# VCFA_v2.net
KiCad netlist of a schematic drawn in EAGLE
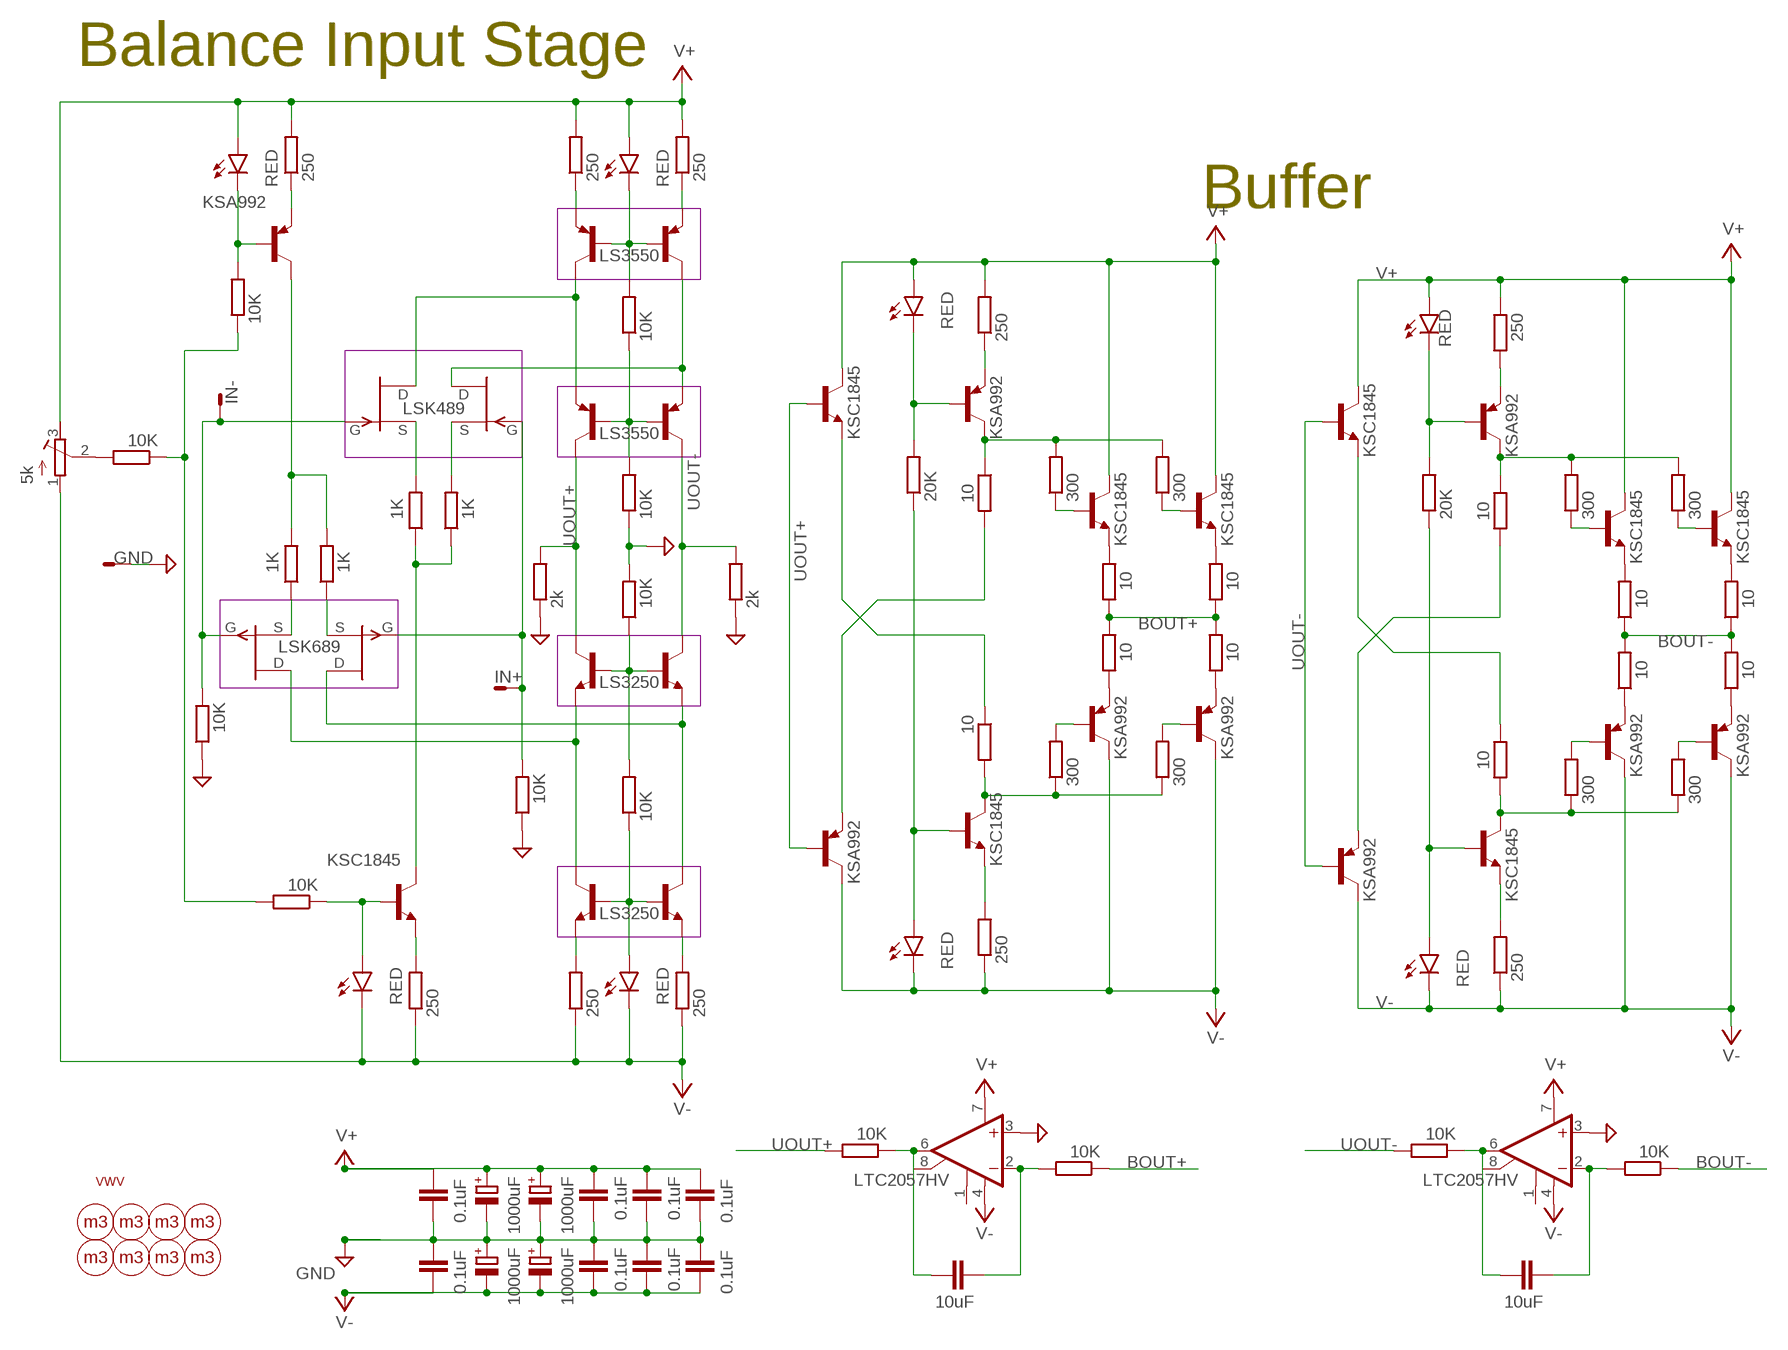
[diagram p0: schematic, sheet 1]
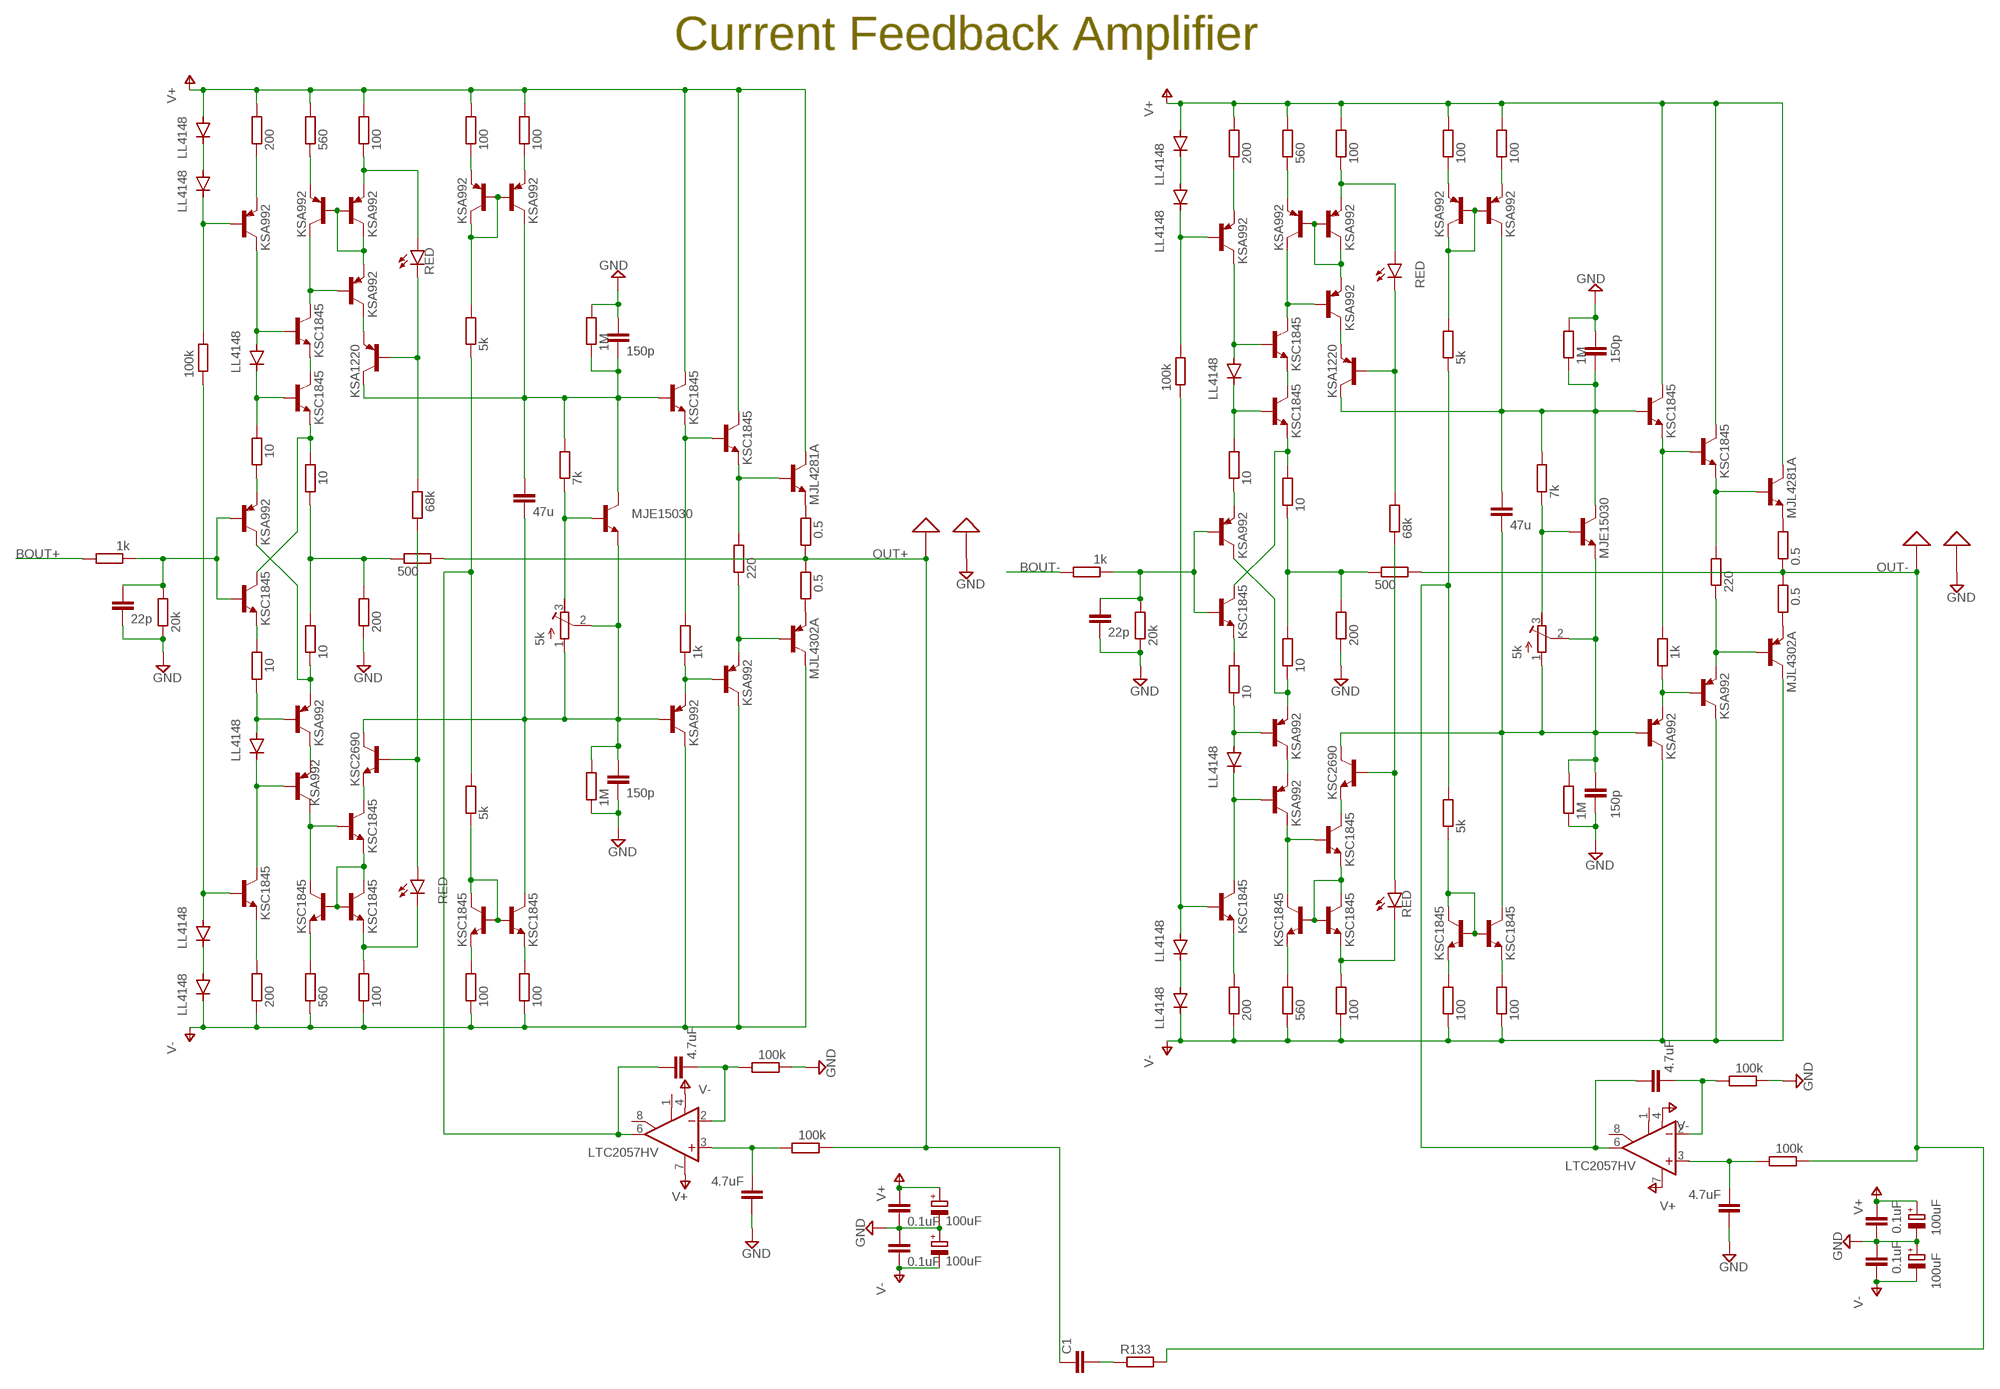
[diagram p1: schematic, sheet 2]
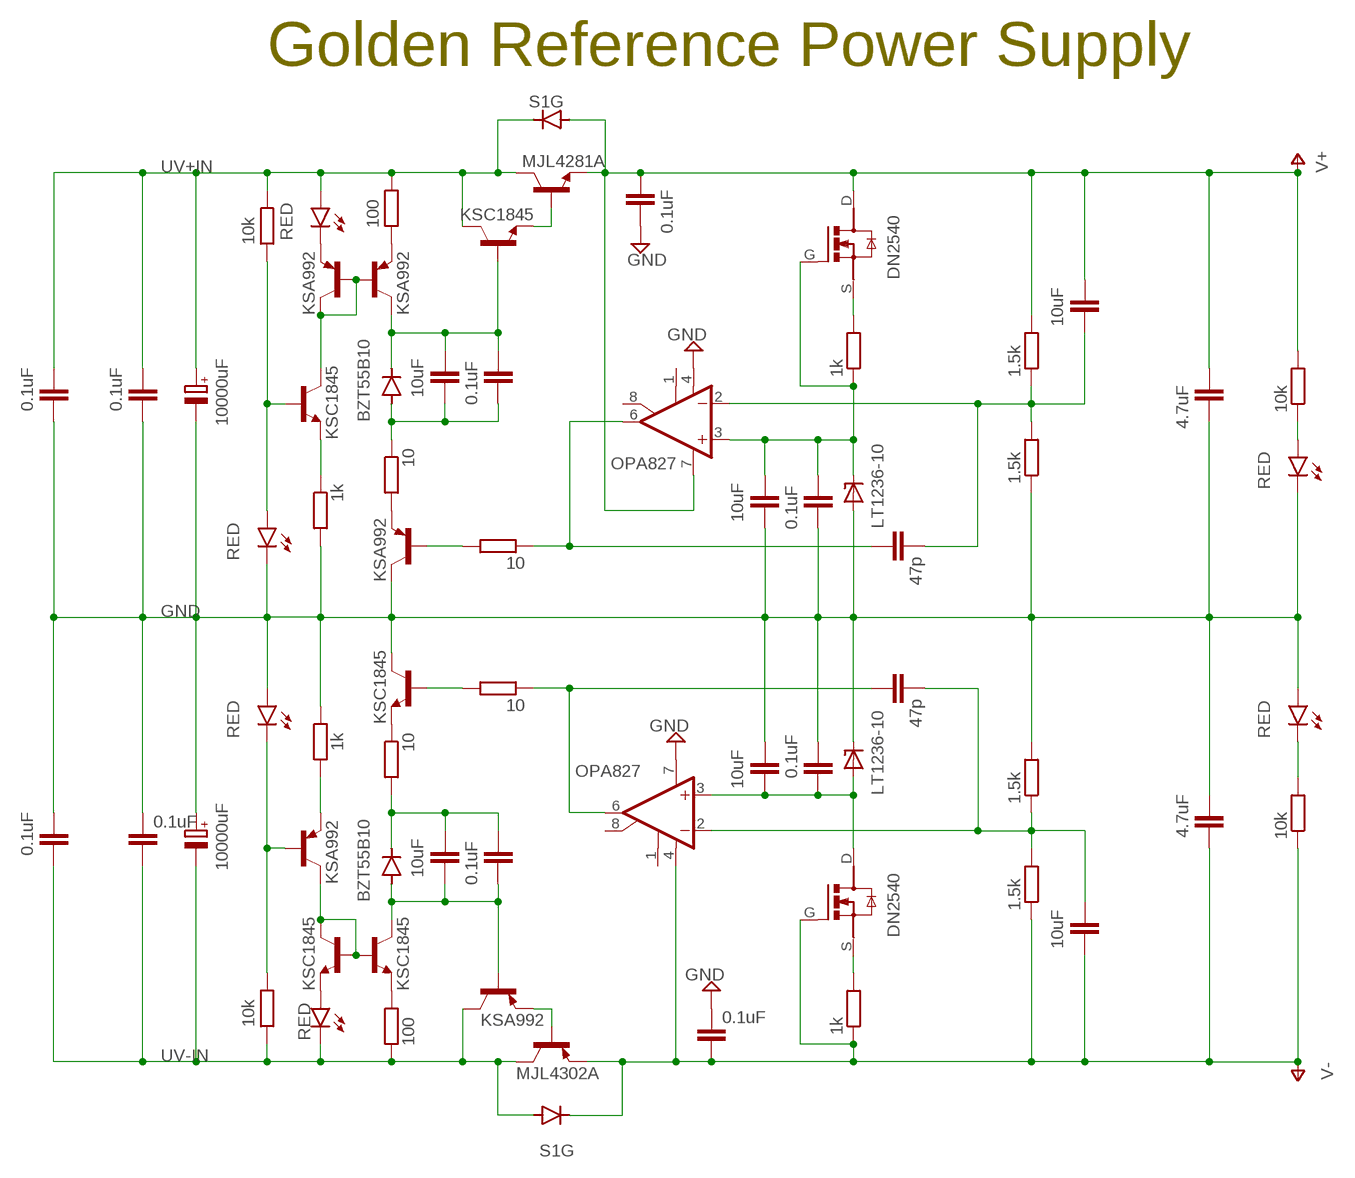
[diagram p2: schematic, sheet 3]
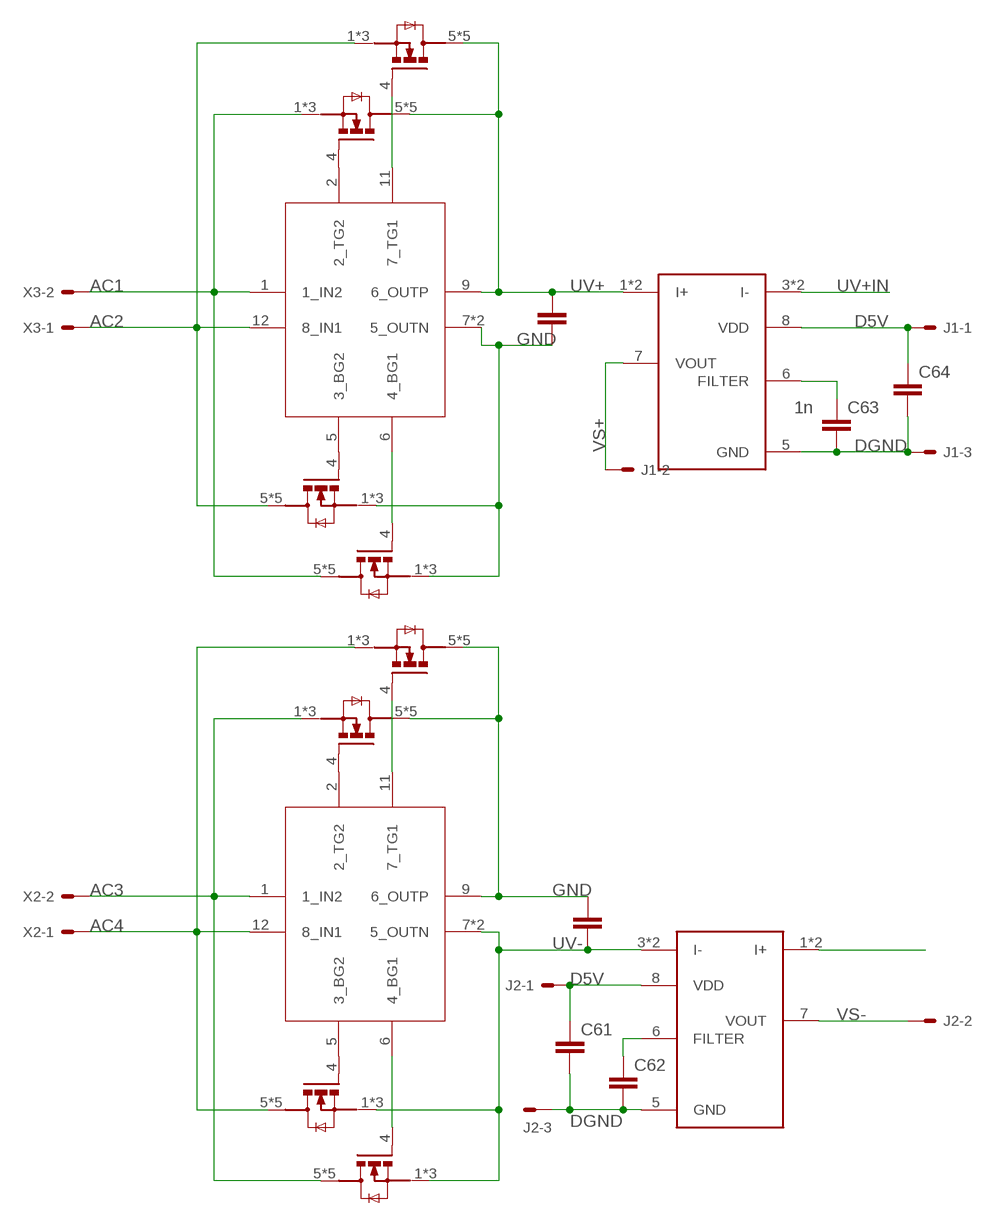
[diagram p3: schematic, sheet 4]

(export (version "E")
  (design (tool "Eeschema 10.0.6"))
  (components
    (comp (ref "C3")
      (value "0.1uF")
      (footprint "eagle-import:C0805")
      (libsource (lib "eagle-import") (part "C-EUC0805"))
    )
    (comp (ref "C4")
      (value "0.1uF")
      (footprint "eagle-import:C0805")
      (libsource (lib "eagle-import") (part "C-EUC0805"))
    )
    (comp (ref "C5")
      (value "1000uF")
      (footprint "eagle-import:E7,5-18")
      (libsource (lib "eagle-import") (part "CPOL-EUE7.5-18"))
    )
    (comp (ref "C6")
      (value "1000uF")
      (footprint "eagle-import:E7,5-18")
      (libsource (lib "eagle-import") (part "CPOL-EUE7.5-18"))
    )
    (comp (ref "C7")
      (value "1000uF")
      (footprint "eagle-import:E7,5-18")
      (libsource (lib "eagle-import") (part "CPOL-EUE7.5-18"))
    )
    (comp (ref "C8")
      (value "1000uF")
      (footprint "eagle-import:E7,5-18")
      (libsource (lib "eagle-import") (part "CPOL-EUE7.5-18"))
    )
    (comp (ref "C9")
      (value "0.1uF")
      (footprint "eagle-import:C050-045X075")
      (libsource (lib "eagle-import") (part "C-EU050-045X075"))
    )
    (comp (ref "C10")
      (value "0.1uF")
      (footprint "eagle-import:C050-045X075")
      (libsource (lib "eagle-import") (part "C-EU050-045X075"))
    )
    (comp (ref "C11")
      (value "0.1uF")
      (footprint "eagle-import:C050-045X075")
      (libsource (lib "eagle-import") (part "C-EU050-045X075"))
    )
    (comp (ref "C12")
      (value "0.1uF")
      (footprint "eagle-import:C050-045X075")
      (libsource (lib "eagle-import") (part "C-EU050-045X075"))
    )
    (comp (ref "C13")
      (value "10uF")
      (footprint "eagle-import:C1206")
      (libsource (lib "eagle-import") (part "C-EUC1206"))
    )
    (comp (ref "C14")
      (value "0.1uF")
      (footprint "eagle-import:C0805")
      (libsource (lib "eagle-import") (part "C-EUC0805"))
    )
    (comp (ref "C15")
      (value "0.1uF")
      (footprint "eagle-import:C0805")
      (libsource (lib "eagle-import") (part "C-EUC0805"))
    )
    (comp (ref "C16")
      (value "10uF")
      (footprint "eagle-import:C1206")
      (libsource (lib "eagle-import") (part "C-EUC1206"))
    )
    (comp (ref "H1")
      (value "HOLE")
      (footprint "eagle-import:M3_HOLE")
      (libsource (lib "eagle-import") (part "HOLE"))
    )
    (comp (ref "H2")
      (value "HOLE")
      (footprint "eagle-import:M3_HOLE")
      (libsource (lib "eagle-import") (part "HOLE"))
    )
    (comp (ref "H3")
      (value "HOLE")
      (footprint "eagle-import:M3_HOLE")
      (libsource (lib "eagle-import") (part "HOLE"))
    )
    (comp (ref "H4")
      (value "HOLE")
      (footprint "eagle-import:M3_HOLE")
      (libsource (lib "eagle-import") (part "HOLE"))
    )
    (comp (ref "H5")
      (value "HOLE")
      (footprint "eagle-import:M3_HOLE")
      (libsource (lib "eagle-import") (part "HOLE"))
    )
    (comp (ref "H6")
      (value "HOLE")
      (footprint "eagle-import:M3_HOLE")
      (libsource (lib "eagle-import") (part "HOLE"))
    )
    (comp (ref "H7")
      (value "HOLE")
      (footprint "eagle-import:M3_HOLE")
      (libsource (lib "eagle-import") (part "HOLE"))
    )
    (comp (ref "H8")
      (value "HOLE")
      (footprint "eagle-import:M3_HOLE")
      (libsource (lib "eagle-import") (part "HOLE"))
    )
    (comp (ref "IC1")
      (value "LTC2057HV")
      (footprint "eagle-import:SOIC8")
      (libsource (lib "eagle-import") (part "LT10S807C"))
    )
    (comp (ref "IC2")
      (value "LTC2057HV")
      (footprint "eagle-import:SOIC8")
      (libsource (lib "eagle-import") (part "LT10S807C"))
    )
    (comp (ref "LED1")
      (value "RED")
      (footprint "eagle-import:LED_SML1206")
      (libsource (lib "eagle-import") (part "LEDVWV1206"))
    )
    (comp (ref "LED2")
      (value "RED")
      (footprint "eagle-import:LED_SML1206")
      (fields (field (name "SPICEPREFIX") "D"))
      (libsource (lib "eagle-import") (part "LEDVWV1206"))
    )
    (comp (ref "LED3")
      (value "RED")
      (footprint "eagle-import:LED_SML1206")
      (libsource (lib "eagle-import") (part "LEDVWV1206"))
    )
    (comp (ref "LED4")
      (value "RED")
      (footprint "eagle-import:LED_SML1206")
      (libsource (lib "eagle-import") (part "LEDVWV1206"))
    )
    (comp (ref "LED5")
      (value "RED")
      (footprint "eagle-import:LED_SML1206")
      (libsource (lib "eagle-import") (part "LEDVWV1206"))
    )
    (comp (ref "LED6")
      (value "RED")
      (footprint "eagle-import:LED_SML1206")
      (libsource (lib "eagle-import") (part "LEDVWV1206"))
    )
    (comp (ref "LED7")
      (value "RED")
      (footprint "eagle-import:LED_SML1206")
      (libsource (lib "eagle-import") (part "LEDVWV1206"))
    )
    (comp (ref "LED8")
      (value "RED")
      (footprint "eagle-import:LED_SML1206")
      (libsource (lib "eagle-import") (part "LEDVWV1206"))
    )
    (comp (ref "Q1")
      (value "LSK689")
      (footprint "eagle-import:SOT-23-6")
      (libsource (lib "eagle-import") (part "LSK689"))
    )
    (comp (ref "Q2")
      (value "KSA992")
      (footprint "eagle-import:TRANSISTOR_TO92-ECB_P")
      (libsource (lib "eagle-import") (part "BJT_PNPKSA992"))
    )
    (comp (ref "Q3")
      (value "KSC1845")
      (footprint "eagle-import:TRANSISTOR_TO92-ECB_N")
      (libsource (lib "eagle-import") (part "BJT_NPNKSC1845"))
    )
    (comp (ref "Q4")
      (value "LSK489")
      (footprint "eagle-import:SOT-23-6")
      (libsource (lib "eagle-import") (part "LSK489SOP-6"))
    )
    (comp (ref "Q5")
      (value "LS3550")
      (footprint "eagle-import:SOT-23-6")
      (libsource (lib "eagle-import") (part "LS3550"))
    )
    (comp (ref "Q6")
      (value "LS3250")
      (footprint "eagle-import:SOT-23-6")
      (libsource (lib "eagle-import") (part "LS3250"))
    )
    (comp (ref "Q7")
      (value "LS3250")
      (footprint "eagle-import:SOT-23-6")
      (libsource (lib "eagle-import") (part "LS3250"))
    )
    (comp (ref "Q8")
      (value "LS3550")
      (footprint "eagle-import:SOT-23-6")
      (libsource (lib "eagle-import") (part "LS3550"))
    )
    (comp (ref "Q9")
      (value "KSC1845")
      (footprint "eagle-import:TRANSISTOR_TO92-ECB_N")
      (libsource (lib "eagle-import") (part "BJT_NPNKSC1845"))
    )
    (comp (ref "Q10")
      (value "KSA992")
      (footprint "eagle-import:TRANSISTOR_TO92-ECB_P")
      (libsource (lib "eagle-import") (part "BJT_PNPKSA992"))
    )
    (comp (ref "Q11")
      (value "KSA992")
      (footprint "eagle-import:TRANSISTOR_TO92-ECB_P")
      (libsource (lib "eagle-import") (part "BJT_PNPKSA992"))
    )
    (comp (ref "Q12")
      (value "KSC1845")
      (footprint "eagle-import:TRANSISTOR_TO92-ECB_N")
      (libsource (lib "eagle-import") (part "BJT_NPNKSC1845"))
    )
    (comp (ref "Q13")
      (value "KSC1845")
      (footprint "eagle-import:TRANSISTOR_TO92-ECB_N")
      (libsource (lib "eagle-import") (part "BJT_NPNKSC1845"))
    )
    (comp (ref "Q14")
      (value "KSA992")
      (footprint "eagle-import:TRANSISTOR_TO92-ECB_P")
      (libsource (lib "eagle-import") (part "BJT_PNPKSA992"))
    )
    (comp (ref "Q15")
      (value "KSC1845")
      (footprint "eagle-import:TRANSISTOR_TO92-ECB_N")
      (libsource (lib "eagle-import") (part "BJT_NPNKSC1845"))
    )
    (comp (ref "Q16")
      (value "KSA992")
      (footprint "eagle-import:TRANSISTOR_TO92-ECB_P")
      (libsource (lib "eagle-import") (part "BJT_PNPKSA992"))
    )
    (comp (ref "Q17")
      (value "KSC1845")
      (footprint "eagle-import:TRANSISTOR_TO92-ECB_N")
      (libsource (lib "eagle-import") (part "BJT_NPNKSC1845"))
    )
    (comp (ref "Q18")
      (value "KSA992")
      (footprint "eagle-import:TRANSISTOR_TO92-ECB_P")
      (libsource (lib "eagle-import") (part "BJT_PNPKSA992"))
    )
    (comp (ref "Q19")
      (value "KSA992")
      (footprint "eagle-import:TRANSISTOR_TO92-ECB_P")
      (libsource (lib "eagle-import") (part "BJT_PNPKSA992"))
    )
    (comp (ref "Q20")
      (value "KSC1845")
      (footprint "eagle-import:TRANSISTOR_TO92-ECB_N")
      (libsource (lib "eagle-import") (part "BJT_NPNKSC1845"))
    )
    (comp (ref "Q21")
      (value "KSC1845")
      (footprint "eagle-import:TRANSISTOR_TO92-ECB_N")
      (libsource (lib "eagle-import") (part "BJT_NPNKSC1845"))
    )
    (comp (ref "Q22")
      (value "KSA992")
      (footprint "eagle-import:TRANSISTOR_TO92-ECB_P")
      (libsource (lib "eagle-import") (part "BJT_PNPKSA992"))
    )
    (comp (ref "Q23")
      (value "KSC1845")
      (footprint "eagle-import:TRANSISTOR_TO92-ECB_N")
      (libsource (lib "eagle-import") (part "BJT_NPNKSC1845"))
    )
    (comp (ref "Q24")
      (value "KSA992")
      (footprint "eagle-import:TRANSISTOR_TO92-ECB_P")
      (libsource (lib "eagle-import") (part "BJT_PNPKSA992"))
    )
    (comp (ref "R1")
      (value "5k")
      (footprint "eagle-import:RTRIM3296W")
      (fields (field (name "SPICEPREFIX") "Z"))
      (libsource (lib "eagle-import") (part "R-TRIMM3296W"))
    )
    (comp (ref "R2")
      (value "10K")
      (footprint "eagle-import:MINI_MELF-0204W")
      (libsource (lib "eagle-import") (part "R-EU_MELF0204W"))
    )
    (comp (ref "R3")
      (value "10K")
      (footprint "eagle-import:MINI_MELF-0204W")
      (libsource (lib "eagle-import") (part "R-EU_MELF0204W"))
    )
    (comp (ref "R4")
      (value "10K")
      (footprint "eagle-import:MINI_MELF-0204W")
      (libsource (lib "eagle-import") (part "R-EU_MELF0204W"))
    )
    (comp (ref "R5")
      (value "250")
      (footprint "eagle-import:MINI_MELF-0204W")
      (libsource (lib "eagle-import") (part "R-EU_MELF0204W"))
    )
    (comp (ref "R6")
      (value "1K")
      (footprint "eagle-import:MINI_MELF-0204W")
      (libsource (lib "eagle-import") (part "R-EU_MELF0204W"))
    )
    (comp (ref "R7")
      (value "250")
      (footprint "eagle-import:MINI_MELF-0204W")
      (fields (field (name "SPICEPREFIX") "R"))
      (libsource (lib "eagle-import") (part "R-EU_MELF0204W"))
    )
    (comp (ref "R8")
      (value "1K")
      (footprint "eagle-import:MINI_MELF-0204W")
      (libsource (lib "eagle-import") (part "R-EU_MELF0204W"))
    )
    (comp (ref "R9")
      (value "1K")
      (footprint "eagle-import:MINI_MELF-0204W")
      (libsource (lib "eagle-import") (part "R-EU_MELF0204W"))
    )
    (comp (ref "R10")
      (value "1K")
      (footprint "eagle-import:MINI_MELF-0204W")
      (libsource (lib "eagle-import") (part "R-EU_MELF0204W"))
    )
    (comp (ref "R11")
      (value "2k")
      (footprint "eagle-import:MINI_MELF-0204W")
      (libsource (lib "eagle-import") (part "R-EU_MELF0204W"))
    )
    (comp (ref "R12")
      (value "250")
      (footprint "eagle-import:MINI_MELF-0204W")
      (libsource (lib "eagle-import") (part "R-EU_MELF0204W"))
    )
    (comp (ref "R13")
      (value "250")
      (footprint "eagle-import:MINI_MELF-0204W")
      (libsource (lib "eagle-import") (part "R-EU_MELF0204W"))
    )
    (comp (ref "R14")
      (value "10K")
      (footprint "eagle-import:MINI_MELF-0204W")
      (libsource (lib "eagle-import") (part "R-EU_MELF0204W"))
    )
    (comp (ref "R15")
      (value "10K")
      (footprint "eagle-import:MINI_MELF-0204W")
      (libsource (lib "eagle-import") (part "R-EU_MELF0204W"))
    )
    (comp (ref "R16")
      (value "10K")
      (footprint "eagle-import:MINI_MELF-0204W")
      (libsource (lib "eagle-import") (part "R-EU_MELF0204W"))
    )
    (comp (ref "R17")
      (value "10K")
      (footprint "eagle-import:MINI_MELF-0204W")
      (libsource (lib "eagle-import") (part "R-EU_MELF0204W"))
    )
    (comp (ref "R18")
      (value "250")
      (footprint "eagle-import:MINI_MELF-0204W")
      (libsource (lib "eagle-import") (part "R-EU_MELF0204W"))
    )
    (comp (ref "R19")
      (value "250")
      (footprint "eagle-import:MINI_MELF-0204W")
      (libsource (lib "eagle-import") (part "R-EU_MELF0204W"))
    )
    (comp (ref "R20")
      (value "2k")
      (footprint "eagle-import:MINI_MELF-0204W")
      (libsource (lib "eagle-import") (part "R-EU_MELF0204W"))
    )
    (comp (ref "R21")
      (value "10K")
      (footprint "eagle-import:MINI_MELF-0204W")
      (libsource (lib "eagle-import") (part "R-EU_MELF0204W"))
    )
    (comp (ref "R22")
      (value "20K")
      (footprint "eagle-import:MINI_MELF-0204W")
      (libsource (lib "eagle-import") (part "R-EU_MELF0204W"))
    )
    (comp (ref "R23")
      (value "250")
      (footprint "eagle-import:MINI_MELF-0204W")
      (libsource (lib "eagle-import") (part "R-EU_MELF0204W"))
    )
    (comp (ref "R24")
      (value "10")
      (footprint "eagle-import:MINI_MELF-0204W")
      (libsource (lib "eagle-import") (part "R-EU_MELF0204W"))
    )
    (comp (ref "R25")
      (value "10")
      (footprint "eagle-import:MINI_MELF-0204W")
      (libsource (lib "eagle-import") (part "R-EU_MELF0204W"))
    )
    (comp (ref "R26")
      (value "250")
      (footprint "eagle-import:MINI_MELF-0204W")
      (libsource (lib "eagle-import") (part "R-EU_MELF0204W"))
    )
    (comp (ref "R27")
      (value "300")
      (footprint "eagle-import:MINI_MELF-0204W")
      (libsource (lib "eagle-import") (part "R-EU_MELF0204W"))
    )
    (comp (ref "R28")
      (value "300")
      (footprint "eagle-import:MINI_MELF-0204W")
      (libsource (lib "eagle-import") (part "R-EU_MELF0204W"))
    )
    (comp (ref "R29")
      (value "10K")
      (footprint "eagle-import:MINI_MELF-0204W")
      (libsource (lib "eagle-import") (part "R-EU_MELF0204W"))
    )
    (comp (ref "R30")
      (value "10")
      (footprint "eagle-import:MINI_MELF-0204W")
      (libsource (lib "eagle-import") (part "R-EU_MELF0204W"))
    )
    (comp (ref "R31")
      (value "10")
      (footprint "eagle-import:MINI_MELF-0204W")
      (libsource (lib "eagle-import") (part "R-EU_MELF0204W"))
    )
    (comp (ref "R32")
      (value "300")
      (footprint "eagle-import:MINI_MELF-0204W")
      (libsource (lib "eagle-import") (part "R-EU_MELF0204W"))
    )
    (comp (ref "R33")
      (value "300")
      (footprint "eagle-import:MINI_MELF-0204W")
      (libsource (lib "eagle-import") (part "R-EU_MELF0204W"))
    )
    (comp (ref "R34")
      (value "10")
      (footprint "eagle-import:MINI_MELF-0204W")
      (libsource (lib "eagle-import") (part "R-EU_MELF0204W"))
    )
    (comp (ref "R35")
      (value "10")
      (footprint "eagle-import:MINI_MELF-0204W")
      (libsource (lib "eagle-import") (part "R-EU_MELF0204W"))
    )
    (comp (ref "R36")
      (value "10K")
      (footprint "eagle-import:MINI_MELF-0204W")
      (libsource (lib "eagle-import") (part "R-EU_MELF0204W"))
    )
    (comp (ref "R37")
      (value "20K")
      (footprint "eagle-import:MINI_MELF-0204W")
      (libsource (lib "eagle-import") (part "R-EU_MELF0204W"))
    )
    (comp (ref "R38")
      (value "250")
      (footprint "eagle-import:MINI_MELF-0204W")
      (libsource (lib "eagle-import") (part "R-EU_MELF0204W"))
    )
    (comp (ref "R39")
      (value "10")
      (footprint "eagle-import:MINI_MELF-0204W")
      (libsource (lib "eagle-import") (part "R-EU_MELF0204W"))
    )
    (comp (ref "R40")
      (value "10")
      (footprint "eagle-import:MINI_MELF-0204W")
      (libsource (lib "eagle-import") (part "R-EU_MELF0204W"))
    )
    (comp (ref "R41")
      (value "250")
      (footprint "eagle-import:MINI_MELF-0204W")
      (libsource (lib "eagle-import") (part "R-EU_MELF0204W"))
    )
    (comp (ref "R42")
      (value "300")
      (footprint "eagle-import:MINI_MELF-0204W")
      (libsource (lib "eagle-import") (part "R-EU_MELF0204W"))
    )
    (comp (ref "R43")
      (value "300")
      (footprint "eagle-import:MINI_MELF-0204W")
      (libsource (lib "eagle-import") (part "R-EU_MELF0204W"))
    )
    (comp (ref "R44")
      (value "10K")
      (footprint "eagle-import:MINI_MELF-0204W")
      (libsource (lib "eagle-import") (part "R-EU_MELF0204W"))
    )
    (comp (ref "R45")
      (value "10")
      (footprint "eagle-import:MINI_MELF-0204W")
      (libsource (lib "eagle-import") (part "R-EU_MELF0204W"))
    )
    (comp (ref "R46")
      (value "10")
      (footprint "eagle-import:MINI_MELF-0204W")
      (libsource (lib "eagle-import") (part "R-EU_MELF0204W"))
    )
    (comp (ref "R47")
      (value "300")
      (footprint "eagle-import:MINI_MELF-0204W")
      (libsource (lib "eagle-import") (part "R-EU_MELF0204W"))
    )
    (comp (ref "R48")
      (value "300")
      (footprint "eagle-import:MINI_MELF-0204W")
      (libsource (lib "eagle-import") (part "R-EU_MELF0204W"))
    )
    (comp (ref "R49")
      (value "10")
      (footprint "eagle-import:MINI_MELF-0204W")
      (libsource (lib "eagle-import") (part "R-EU_MELF0204W"))
    )
    (comp (ref "R50")
      (value "10")
      (footprint "eagle-import:MINI_MELF-0204W")
      (libsource (lib "eagle-import") (part "R-EU_MELF0204W"))
    )
    (comp (ref "R134")
      (value "10K")
      (footprint "eagle-import:MINI_MELF-0204W")
      (libsource (lib "eagle-import") (part "R-EU_MELF0204W"))
    )
    (comp (ref "R135")
      (value "10K")
      (footprint "eagle-import:MINI_MELF-0204W")
      (libsource (lib "eagle-import") (part "R-EU_MELF0204W"))
    )
    (comp (ref "S1")
      (value "VWV")
      (footprint "eagle-import:VWV")
      (libsource (lib "eagle-import") (part "VWV"))
    )
    (comp (ref "X1")
      (value "KK-156-3")
      (footprint "eagle-import:KK-156-3")
      (fields (field (name "MF") "MOLEX"))
      (libsource (lib "eagle-import") (part "KK-156-3"))
    )
    (comp (ref "C57")
      (value "47uF")
      (footprint "eagle-import:C1206")
      (libsource (lib "eagle-import") (part "C-EUC1206"))
    )
    (comp (ref "C59")
      (value "47uF")
      (footprint "eagle-import:C1206")
      (libsource (lib "eagle-import") (part "C-EUC1206"))
    )
    (comp (ref "C61")
      (value "C-EUC0805")
      (footprint "eagle-import:C0805")
      (libsource (lib "eagle-import") (part "C-EUC0805"))
    )
    (comp (ref "C62")
      (value "C-EUC0805")
      (footprint "eagle-import:C0805")
      (libsource (lib "eagle-import") (part "C-EUC0805"))
    )
    (comp (ref "C63")
      (value "1n")
      (footprint "eagle-import:C0805")
      (libsource (lib "eagle-import") (part "C-EUC0805"))
    )
    (comp (ref "C64")
      (value "C-EUC0805")
      (footprint "eagle-import:C0805")
      (libsource (lib "eagle-import") (part "C-EUC0805"))
    )
    (comp (ref "J1")
      (value "22-27-2031-03")
      (footprint "eagle-import:6410-03")
      (fields (field (name "MF") "MOLEX"))
      (libsource (lib "eagle-import") (part "22-?-0327-2031"))
    )
    (comp (ref "J2")
      (value "22-27-2031-03")
      (footprint "eagle-import:6410-03")
      (fields (field (name "MF") "MOLEX"))
      (libsource (lib "eagle-import") (part "22-?-0327-2031"))
    )
    (comp (ref "Q97")
      (value "MOS_SMDTDSON-8")
      (footprint "eagle-import:PG-TDSON-8")
      (libsource (lib "eagle-import") (part "MOS_SMDTDSON-8"))
    )
    (comp (ref "Q98")
      (value "MOS_SMDTDSON-8")
      (footprint "eagle-import:PG-TDSON-8")
      (libsource (lib "eagle-import") (part "MOS_SMDTDSON-8"))
    )
    (comp (ref "Q99")
      (value "MOS_SMDTDSON-8")
      (footprint "eagle-import:PG-TDSON-8")
      (libsource (lib "eagle-import") (part "MOS_SMDTDSON-8"))
    )
    (comp (ref "Q100")
      (value "MOS_SMDTDSON-8")
      (footprint "eagle-import:PG-TDSON-8")
      (libsource (lib "eagle-import") (part "MOS_SMDTDSON-8"))
    )
    (comp (ref "Q105")
      (value "MOS_SMDTDSON-8")
      (footprint "eagle-import:PG-TDSON-8")
      (libsource (lib "eagle-import") (part "MOS_SMDTDSON-8"))
    )
    (comp (ref "Q106")
      (value "MOS_SMDTDSON-8")
      (footprint "eagle-import:PG-TDSON-8")
      (libsource (lib "eagle-import") (part "MOS_SMDTDSON-8"))
    )
    (comp (ref "Q107")
      (value "MOS_SMDTDSON-8")
      (footprint "eagle-import:PG-TDSON-8")
      (libsource (lib "eagle-import") (part "MOS_SMDTDSON-8"))
    )
    (comp (ref "Q108")
      (value "MOS_SMDTDSON-8")
      (footprint "eagle-import:PG-TDSON-8")
      (libsource (lib "eagle-import") (part "MOS_SMDTDSON-8"))
    )
    (comp (ref "U$1")
      (value "ACHS-712X")
      (footprint "eagle-import:SO8")
      (libsource (lib "eagle-import") (part "ACHS-712X"))
    )
    (comp (ref "U$2")
      (value "LT4320MSOP")
      (footprint "eagle-import:LT4320_MSOP")
      (libsource (lib "eagle-import") (part "LT4320MSOP"))
    )
    (comp (ref "U$3")
      (value "ACHS-712X")
      (footprint "eagle-import:SO8")
      (libsource (lib "eagle-import") (part "ACHS-712X"))
    )
    (comp (ref "U$4")
      (value "LT4320MSOP")
      (footprint "eagle-import:LT4320_MSOP")
      (libsource (lib "eagle-import") (part "LT4320MSOP"))
    )
    (comp (ref "X2")
      (value "KK-156-2")
      (footprint "eagle-import:KK-156-2")
      (fields (field (name "MF") "MOLEX"))
      (libsource (lib "eagle-import") (part "KK-156-2"))
    )
    (comp (ref "X3")
      (value "KK-156-2")
      (footprint "eagle-import:KK-156-2")
      (fields (field (name "MF") "MOLEX"))
      (libsource (lib "eagle-import") (part "KK-156-2"))
    )
    (comp (ref "C1")
      (value "C-EUECWU-V")
      (footprint "eagle-import:ECHU-Y")
      (libsource (lib "eagle-import") (part "C-EUECWU-V"))
    )
    (comp (ref "C17")
      (value "22p")
      (footprint "eagle-import:C0805")
      (fields (field (name "SPICEPREFIX") "C"))
      (libsource (lib "eagle-import") (part "C-EUC0805"))
    )
    (comp (ref "C18")
      (value "47u")
      (footprint "eagle-import:C1210")
      (fields (field (name "SPICEPREFIX") "C"))
      (libsource (lib "eagle-import") (part "C-EUC1210"))
    )
    (comp (ref "C19")
      (value "150p")
      (footprint "eagle-import:C0805")
      (fields (field (name "SPICEPREFIX") "C"))
      (libsource (lib "eagle-import") (part "C-EUC0805"))
    )
    (comp (ref "C20")
      (value "150p")
      (footprint "eagle-import:C0805")
      (fields (field (name "SPICEPREFIX") "C"))
      (libsource (lib "eagle-import") (part "C-EUC0805"))
    )
    (comp (ref "C21")
      (value "4.7uF")
      (footprint "eagle-import:C1210")
      (fields (field (name "SPICEPREFIX") "C"))
      (libsource (lib "eagle-import") (part "C-EUC1210"))
    )
    (comp (ref "C22")
      (value "4.7uF")
      (footprint "eagle-import:C1210")
      (fields (field (name "SPICEPREFIX") "C"))
      (libsource (lib "eagle-import") (part "C-EUC1210"))
    )
    (comp (ref "C23")
      (value "0.1uF")
      (footprint "eagle-import:C0603K")
      (libsource (lib "eagle-import") (part "C-EUC0603K"))
    )
    (comp (ref "C24")
      (value "0.1uF")
      (footprint "eagle-import:C0603K")
      (libsource (lib "eagle-import") (part "C-EUC0603K"))
    )
    (comp (ref "C25")
      (value "100uF")
      (footprint "eagle-import:E3,5-8")
      (libsource (lib "eagle-import") (part "CPOL-EUE3.5-8"))
    )
    (comp (ref "C26")
      (value "100uF")
      (footprint "eagle-import:E3,5-8")
      (libsource (lib "eagle-import") (part "CPOL-EUE3.5-8"))
    )
    (comp (ref "C27")
      (value "22p")
      (footprint "eagle-import:C0805")
      (fields (field (name "SPICEPREFIX") "C"))
      (libsource (lib "eagle-import") (part "C-EUC0805"))
    )
    (comp (ref "C28")
      (value "47u")
      (footprint "eagle-import:C1210")
      (fields (field (name "SPICEPREFIX") "C"))
      (libsource (lib "eagle-import") (part "C-EUC1210"))
    )
    (comp (ref "C29")
      (value "150p")
      (footprint "eagle-import:C0805")
      (fields (field (name "SPICEPREFIX") "C"))
      (libsource (lib "eagle-import") (part "C-EUC0805"))
    )
    (comp (ref "C30")
      (value "150p")
      (footprint "eagle-import:C0805")
      (fields (field (name "SPICEPREFIX") "C"))
      (libsource (lib "eagle-import") (part "C-EUC0805"))
    )
    (comp (ref "C31")
      (value "4.7uF")
      (footprint "eagle-import:C1210")
      (fields (field (name "SPICEPREFIX") "C"))
      (libsource (lib "eagle-import") (part "C-EUC1210"))
    )
    (comp (ref "C32")
      (value "4.7uF")
      (footprint "eagle-import:C1210")
      (fields (field (name "SPICEPREFIX") "C"))
      (libsource (lib "eagle-import") (part "C-EUC1210"))
    )
    (comp (ref "C33")
      (value "0.1uF")
      (footprint "eagle-import:C0603K")
      (libsource (lib "eagle-import") (part "C-EUC0603K"))
    )
    (comp (ref "C34")
      (value "0.1uF")
      (footprint "eagle-import:C0603K")
      (libsource (lib "eagle-import") (part "C-EUC0603K"))
    )
    (comp (ref "C35")
      (value "100uF")
      (footprint "eagle-import:E3,5-8")
      (libsource (lib "eagle-import") (part "CPOL-EUE3.5-8"))
    )
    (comp (ref "C36")
      (value "100uF")
      (footprint "eagle-import:E3,5-8")
      (libsource (lib "eagle-import") (part "CPOL-EUE3.5-8"))
    )
    (comp (ref "D1")
      (value "LL4148")
      (footprint "eagle-import:SOD80C")
      (fields (field (name "SPICEPREFIX") "D"))
      (libsource (lib "eagle-import") (part "DIODE-SOD80C"))
    )
    (comp (ref "D2")
      (value "LL4148")
      (footprint "eagle-import:SOD80C")
      (fields (field (name "SPICEPREFIX") "D"))
      (libsource (lib "eagle-import") (part "DIODE-SOD80C"))
    )
    (comp (ref "D3")
      (value "LL4148")
      (footprint "eagle-import:SOD80C")
      (fields (field (name "SPICEPREFIX") "D"))
      (libsource (lib "eagle-import") (part "DIODE-SOD80C"))
    )
    (comp (ref "D4")
      (value "LL4148")
      (footprint "eagle-import:SOD80C")
      (fields (field (name "SPICEPREFIX") "D"))
      (libsource (lib "eagle-import") (part "DIODE-SOD80C"))
    )
    (comp (ref "D5")
      (value "LL4148")
      (footprint "eagle-import:SOD80C")
      (fields (field (name "SPICEPREFIX") "D"))
      (libsource (lib "eagle-import") (part "DIODE-SOD80C"))
    )
    (comp (ref "D6")
      (value "LL4148")
      (footprint "eagle-import:SOD80C")
      (fields (field (name "SPICEPREFIX") "D"))
      (libsource (lib "eagle-import") (part "DIODE-SOD80C"))
    )
    (comp (ref "D7")
      (value "LL4148")
      (footprint "eagle-import:SOD80C")
      (fields (field (name "SPICEPREFIX") "D"))
      (libsource (lib "eagle-import") (part "DIODE-SOD80C"))
    )
    (comp (ref "D8")
      (value "LL4148")
      (footprint "eagle-import:SOD80C")
      (fields (field (name "SPICEPREFIX") "D"))
      (libsource (lib "eagle-import") (part "DIODE-SOD80C"))
    )
    (comp (ref "D9")
      (value "LL4148")
      (footprint "eagle-import:SOD80C")
      (fields (field (name "SPICEPREFIX") "D"))
      (libsource (lib "eagle-import") (part "DIODE-SOD80C"))
    )
    (comp (ref "D10")
      (value "LL4148")
      (footprint "eagle-import:SOD80C")
      (fields (field (name "SPICEPREFIX") "D"))
      (libsource (lib "eagle-import") (part "DIODE-SOD80C"))
    )
    (comp (ref "D11")
      (value "LL4148")
      (footprint "eagle-import:SOD80C")
      (fields (field (name "SPICEPREFIX") "D"))
      (libsource (lib "eagle-import") (part "DIODE-SOD80C"))
    )
    (comp (ref "D12")
      (value "LL4148")
      (footprint "eagle-import:SOD80C")
      (fields (field (name "SPICEPREFIX") "D"))
      (libsource (lib "eagle-import") (part "DIODE-SOD80C"))
    )
    (comp (ref "IC3")
      (value "LTC2057HV")
      (footprint "eagle-import:SOIC8")
      (libsource (lib "eagle-import") (part "LT10S837I"))
    )
    (comp (ref "IC4")
      (value "LTC2057HV")
      (footprint "eagle-import:SOIC8")
      (libsource (lib "eagle-import") (part "LT10S837I"))
    )
    (comp (ref "LED9")
      (value "RED")
      (footprint "eagle-import:LED_SML1206")
      (fields (field (name "SPICEPREFIX") "D"))
      (libsource (lib "eagle-import") (part "LEDVWV1206"))
    )
    (comp (ref "LED10")
      (value "RED")
      (footprint "eagle-import:LED_SML1206")
      (fields (field (name "SPICEPREFIX") "D"))
      (libsource (lib "eagle-import") (part "LEDVWV1206"))
    )
    (comp (ref "LED11")
      (value "RED")
      (footprint "eagle-import:LED_SML1206")
      (fields (field (name "SPICEPREFIX") "D"))
      (libsource (lib "eagle-import") (part "LEDVWV1206"))
    )
    (comp (ref "LED12")
      (value "RED")
      (footprint "eagle-import:LED_SML1206")
      (fields (field (name "SPICEPREFIX") "D"))
      (libsource (lib "eagle-import") (part "LEDVWV1206"))
    )
    (comp (ref "PAD1")
      (value "PAD")
      (footprint "eagle-import:PAD-16")
      (libsource (lib "eagle-import") (part "PAD"))
    )
    (comp (ref "PAD2")
      (value "PAD")
      (footprint "eagle-import:PAD-16")
      (libsource (lib "eagle-import") (part "PAD"))
    )
    (comp (ref "PAD3")
      (value "PAD")
      (footprint "eagle-import:PAD-16")
      (libsource (lib "eagle-import") (part "PAD"))
    )
    (comp (ref "PAD4")
      (value "PAD")
      (footprint "eagle-import:PAD-16")
      (libsource (lib "eagle-import") (part "PAD"))
    )
    (comp (ref "Q25")
      (value "KSA992")
      (footprint "eagle-import:TRANSISTOR_TO92-ECB_P")
      (fields (field (name "SPICEPREFIX") "Q"))
      (libsource (lib "eagle-import") (part "BJT_PNPKSA992"))
    )
    (comp (ref "Q26")
      (value "KSA992")
      (footprint "eagle-import:TRANSISTOR_TO92-ECB_P")
      (fields (field (name "SPICEPREFIX") "Q"))
      (libsource (lib "eagle-import") (part "BJT_PNPKSA992"))
    )
    (comp (ref "Q27")
      (value "KSC1845")
      (footprint "eagle-import:TRANSISTOR_TO92-ECB_N")
      (fields (field (name "SPICEPREFIX") "Q"))
      (libsource (lib "eagle-import") (part "BJT_NPNKSC1845"))
    )
    (comp (ref "Q28")
      (value "KSC1845")
      (footprint "eagle-import:TRANSISTOR_TO92-ECB_N")
      (fields (field (name "SPICEPREFIX") "Q"))
      (libsource (lib "eagle-import") (part "BJT_NPNKSC1845"))
    )
    (comp (ref "Q29")
      (value "KSC1845")
      (footprint "eagle-import:TRANSISTOR_TO92-ECB_N")
      (fields (field (name "SPICEPREFIX") "Q"))
      (libsource (lib "eagle-import") (part "BJT_NPNKSC1845"))
    )
    (comp (ref "Q30")
      (value "KSC1845")
      (footprint "eagle-import:TRANSISTOR_TO92-ECB_N")
      (fields (field (name "SPICEPREFIX") "Q"))
      (libsource (lib "eagle-import") (part "BJT_NPNKSC1845"))
    )
    (comp (ref "Q31")
      (value "KSA992")
      (footprint "eagle-import:TRANSISTOR_TO92-ECB_P")
      (fields (field (name "SPICEPREFIX") "Q"))
      (libsource (lib "eagle-import") (part "BJT_PNPKSA992"))
    )
    (comp (ref "Q32")
      (value "KSA992")
      (footprint "eagle-import:TRANSISTOR_TO92-ECB_P")
      (fields (field (name "SPICEPREFIX") "Q"))
      (libsource (lib "eagle-import") (part "BJT_PNPKSA992"))
    )
    (comp (ref "Q33")
      (value "KSA992")
      (footprint "eagle-import:TRANSISTOR_TO92-ECB_P")
      (fields (field (name "SPICEPREFIX") "Q"))
      (libsource (lib "eagle-import") (part "BJT_PNPKSA992"))
    )
    (comp (ref "Q34")
      (value "KSC1845")
      (footprint "eagle-import:TRANSISTOR_TO92-ECB_N")
      (fields (field (name "SPICEPREFIX") "Q"))
      (libsource (lib "eagle-import") (part "BJT_NPNKSC1845"))
    )
    (comp (ref "Q35")
      (value "KSA992")
      (footprint "eagle-import:TRANSISTOR_TO92-ECB_P")
      (fields (field (name "SPICEPREFIX") "Q"))
      (libsource (lib "eagle-import") (part "BJT_PNPKSA992"))
    )
    (comp (ref "Q36")
      (value "KSA992")
      (footprint "eagle-import:TRANSISTOR_TO92-ECB_P")
      (fields (field (name "SPICEPREFIX") "Q"))
      (libsource (lib "eagle-import") (part "BJT_PNPKSA992"))
    )
    (comp (ref "Q37")
      (value "KSC1845")
      (footprint "eagle-import:TRANSISTOR_TO92-ECB_N")
      (fields (field (name "SPICEPREFIX") "Q"))
      (libsource (lib "eagle-import") (part "BJT_NPNKSC1845"))
    )
    (comp (ref "Q38")
      (value "KSC1845")
      (footprint "eagle-import:TRANSISTOR_TO92-ECB_N")
      (fields (field (name "SPICEPREFIX") "Q"))
      (libsource (lib "eagle-import") (part "BJT_NPNKSC1845"))
    )
    (comp (ref "Q39")
      (value "KSA1220")
      (footprint "eagle-import:TRANSISTOR_TO126_P")
      (fields (field (name "SPICEPREFIX") "Q"))
      (libsource (lib "eagle-import") (part "BJT_PNPKSA1220"))
    )
    (comp (ref "Q40")
      (value "KSC2690")
      (footprint "eagle-import:TRANSISTOR_TO126_N")
      (fields (field (name "SPICEPREFIX") "Q"))
      (libsource (lib "eagle-import") (part "BJT_NPNKSC2690"))
    )
    (comp (ref "Q41")
      (value "KSA992")
      (footprint "eagle-import:TRANSISTOR_TO92-ECB_P")
      (fields (field (name "SPICEPREFIX") "Q"))
      (libsource (lib "eagle-import") (part "BJT_PNPKSA992"))
    )
    (comp (ref "Q42")
      (value "KSC1845")
      (footprint "eagle-import:TRANSISTOR_TO92-ECB_N")
      (fields (field (name "SPICEPREFIX") "Q"))
      (libsource (lib "eagle-import") (part "BJT_NPNKSC1845"))
    )
    (comp (ref "Q43")
      (value "KSA992")
      (footprint "eagle-import:TRANSISTOR_TO92-ECB_P")
      (fields (field (name "SPICEPREFIX") "Q"))
      (libsource (lib "eagle-import") (part "BJT_PNPKSA992"))
    )
    (comp (ref "Q44")
      (value "KSC1845")
      (footprint "eagle-import:TRANSISTOR_TO92-ECB_N")
      (fields (field (name "SPICEPREFIX") "Q"))
      (libsource (lib "eagle-import") (part "BJT_NPNKSC1845"))
    )
    (comp (ref "Q45")
      (value "MJE15030")
      (footprint "eagle-import:TRANSISTOR_TO220_BCE_N")
      (fields (field (name "SPICEPREFIX") "Q"))
      (libsource (lib "eagle-import") (part "BJT_NPNMJE15030"))
    )
    (comp (ref "Q46")
      (value "KSC1845")
      (footprint "eagle-import:TRANSISTOR_TO92-ECB_N")
      (fields (field (name "SPICEPREFIX") "Q"))
      (libsource (lib "eagle-import") (part "BJT_NPNKSC1845"))
    )
    (comp (ref "Q47")
      (value "KSA992")
      (footprint "eagle-import:TRANSISTOR_TO92-ECB_P")
      (fields (field (name "SPICEPREFIX") "Q"))
      (libsource (lib "eagle-import") (part "BJT_PNPKSA992"))
    )
    (comp (ref "Q48")
      (value "KSC1845")
      (footprint "eagle-import:TRANSISTOR_TO92-ECB_N")
      (fields (field (name "SPICEPREFIX") "Q"))
      (libsource (lib "eagle-import") (part "BJT_NPNKSC1845"))
    )
    (comp (ref "Q49")
      (value "KSA992")
      (footprint "eagle-import:TRANSISTOR_TO92-ECB_P")
      (fields (field (name "SPICEPREFIX") "Q"))
      (libsource (lib "eagle-import") (part "BJT_PNPKSA992"))
    )
    (comp (ref "Q50")
      (value "MJL4281A")
      (footprint "eagle-import:TRANSISTOR_TO247_BCE_N")
      (fields (field (name "SPICEPREFIX") "Q"))
      (libsource (lib "eagle-import") (part "BJT_NPNMJL4281"))
    )
    (comp (ref "Q51")
      (value "MJL4302A")
      (footprint "eagle-import:TRANSISTOR_TO247_BCE_P")
      (fields (field (name "SPICEPREFIX") "Q"))
      (libsource (lib "eagle-import") (part "BJT_PNPMJL4302"))
    )
    (comp (ref "Q52")
      (value "KSA992")
      (footprint "eagle-import:TRANSISTOR_TO92-ECB_P")
      (fields (field (name "SPICEPREFIX") "Q"))
      (libsource (lib "eagle-import") (part "BJT_PNPKSA992"))
    )
    (comp (ref "Q53")
      (value "KSA992")
      (footprint "eagle-import:TRANSISTOR_TO92-ECB_P")
      (fields (field (name "SPICEPREFIX") "Q"))
      (libsource (lib "eagle-import") (part "BJT_PNPKSA992"))
    )
    (comp (ref "Q54")
      (value "KSC1845")
      (footprint "eagle-import:TRANSISTOR_TO92-ECB_N")
      (fields (field (name "SPICEPREFIX") "Q"))
      (libsource (lib "eagle-import") (part "BJT_NPNKSC1845"))
    )
    (comp (ref "Q55")
      (value "KSC1845")
      (footprint "eagle-import:TRANSISTOR_TO92-ECB_N")
      (fields (field (name "SPICEPREFIX") "Q"))
      (libsource (lib "eagle-import") (part "BJT_NPNKSC1845"))
    )
    (comp (ref "Q56")
      (value "KSC1845")
      (footprint "eagle-import:TRANSISTOR_TO92-ECB_N")
      (fields (field (name "SPICEPREFIX") "Q"))
      (libsource (lib "eagle-import") (part "BJT_NPNKSC1845"))
    )
    (comp (ref "Q57")
      (value "KSC1845")
      (footprint "eagle-import:TRANSISTOR_TO92-ECB_N")
      (fields (field (name "SPICEPREFIX") "Q"))
      (libsource (lib "eagle-import") (part "BJT_NPNKSC1845"))
    )
    (comp (ref "Q58")
      (value "KSA992")
      (footprint "eagle-import:TRANSISTOR_TO92-ECB_P")
      (fields (field (name "SPICEPREFIX") "Q"))
      (libsource (lib "eagle-import") (part "BJT_PNPKSA992"))
    )
    (comp (ref "Q59")
      (value "KSA992")
      (footprint "eagle-import:TRANSISTOR_TO92-ECB_P")
      (fields (field (name "SPICEPREFIX") "Q"))
      (libsource (lib "eagle-import") (part "BJT_PNPKSA992"))
    )
    (comp (ref "Q60")
      (value "KSA992")
      (footprint "eagle-import:TRANSISTOR_TO92-ECB_P")
      (fields (field (name "SPICEPREFIX") "Q"))
      (libsource (lib "eagle-import") (part "BJT_PNPKSA992"))
    )
    (comp (ref "Q61")
      (value "KSC1845")
      (footprint "eagle-import:TRANSISTOR_TO92-ECB_N")
      (fields (field (name "SPICEPREFIX") "Q"))
      (libsource (lib "eagle-import") (part "BJT_NPNKSC1845"))
    )
    (comp (ref "Q62")
      (value "KSA992")
      (footprint "eagle-import:TRANSISTOR_TO92-ECB_P")
      (fields (field (name "SPICEPREFIX") "Q"))
      (libsource (lib "eagle-import") (part "BJT_PNPKSA992"))
    )
    (comp (ref "Q63")
      (value "KSA992")
      (footprint "eagle-import:TRANSISTOR_TO92-ECB_P")
      (fields (field (name "SPICEPREFIX") "Q"))
      (libsource (lib "eagle-import") (part "BJT_PNPKSA992"))
    )
    (comp (ref "Q64")
      (value "KSC1845")
      (footprint "eagle-import:TRANSISTOR_TO92-ECB_N")
      (fields (field (name "SPICEPREFIX") "Q"))
      (libsource (lib "eagle-import") (part "BJT_NPNKSC1845"))
    )
    (comp (ref "Q65")
      (value "KSC1845")
      (footprint "eagle-import:TRANSISTOR_TO92-ECB_N")
      (fields (field (name "SPICEPREFIX") "Q"))
      (libsource (lib "eagle-import") (part "BJT_NPNKSC1845"))
    )
    (comp (ref "Q66")
      (value "KSA1220")
      (footprint "eagle-import:TRANSISTOR_TO126_P")
      (fields (field (name "SPICEPREFIX") "Q"))
      (libsource (lib "eagle-import") (part "BJT_PNPKSA1220"))
    )
    (comp (ref "Q67")
      (value "KSC2690")
      (footprint "eagle-import:TRANSISTOR_TO126_N")
      (fields (field (name "SPICEPREFIX") "Q"))
      (libsource (lib "eagle-import") (part "BJT_NPNKSC2690"))
    )
    (comp (ref "Q68")
      (value "KSA992")
      (footprint "eagle-import:TRANSISTOR_TO92-ECB_P")
      (fields (field (name "SPICEPREFIX") "Q"))
      (libsource (lib "eagle-import") (part "BJT_PNPKSA992"))
    )
    (comp (ref "Q69")
      (value "KSC1845")
      (footprint "eagle-import:TRANSISTOR_TO92-ECB_N")
      (fields (field (name "SPICEPREFIX") "Q"))
      (libsource (lib "eagle-import") (part "BJT_NPNKSC1845"))
    )
    (comp (ref "Q70")
      (value "KSA992")
      (footprint "eagle-import:TRANSISTOR_TO92-ECB_P")
      (fields (field (name "SPICEPREFIX") "Q"))
      (libsource (lib "eagle-import") (part "BJT_PNPKSA992"))
    )
    (comp (ref "Q71")
      (value "KSC1845")
      (footprint "eagle-import:TRANSISTOR_TO92-ECB_N")
      (fields (field (name "SPICEPREFIX") "Q"))
      (libsource (lib "eagle-import") (part "BJT_NPNKSC1845"))
    )
    (comp (ref "Q72")
      (value "MJE15030")
      (footprint "eagle-import:TRANSISTOR_TO220_BCE_N")
      (fields (field (name "SPICEPREFIX") "Q"))
      (libsource (lib "eagle-import") (part "BJT_NPNMJE15030"))
    )
    (comp (ref "Q73")
      (value "KSC1845")
      (footprint "eagle-import:TRANSISTOR_TO92-ECB_N")
      (fields (field (name "SPICEPREFIX") "Q"))
      (libsource (lib "eagle-import") (part "BJT_NPNKSC1845"))
    )
    (comp (ref "Q74")
      (value "KSA992")
      (footprint "eagle-import:TRANSISTOR_TO92-ECB_P")
      (fields (field (name "SPICEPREFIX") "Q"))
      (libsource (lib "eagle-import") (part "BJT_PNPKSA992"))
    )
    (comp (ref "Q75")
      (value "KSC1845")
      (footprint "eagle-import:TRANSISTOR_TO92-ECB_N")
      (fields (field (name "SPICEPREFIX") "Q"))
      (libsource (lib "eagle-import") (part "BJT_NPNKSC1845"))
    )
    (comp (ref "Q76")
      (value "KSA992")
      (footprint "eagle-import:TRANSISTOR_TO92-ECB_P")
      (fields (field (name "SPICEPREFIX") "Q"))
      (libsource (lib "eagle-import") (part "BJT_PNPKSA992"))
    )
    (comp (ref "Q77")
      (value "MJL4281A")
      (footprint "eagle-import:TRANSISTOR_TO247_BCE_N")
      (fields (field (name "SPICEPREFIX") "Q"))
      (libsource (lib "eagle-import") (part "BJT_NPNMJL4281"))
    )
    (comp (ref "Q78")
      (value "MJL4302A")
      (footprint "eagle-import:TRANSISTOR_TO247_BCE_P")
      (fields (field (name "SPICEPREFIX") "Q"))
      (libsource (lib "eagle-import") (part "BJT_PNPMJL4302"))
    )
    (comp (ref "R51")
      (value "1k")
      (footprint "eagle-import:MINI_MELF-0204W")
      (fields (field (name "SPICEPREFIX") "R"))
      (libsource (lib "eagle-import") (part "R-EU_MELF0204W"))
    )
    (comp (ref "R52")
      (value "20k")
      (footprint "eagle-import:MINI_MELF-0204W")
      (fields (field (name "SPICEPREFIX") "R"))
      (libsource (lib "eagle-import") (part "R-EU_MELF0204W"))
    )
    (comp (ref "R53")
      (value "100k")
      (footprint "eagle-import:MINI_MELF-0204W")
      (fields (field (name "SPICEPREFIX") "R"))
      (libsource (lib "eagle-import") (part "R-EU_MELF0204W"))
    )
    (comp (ref "R54")
      (value "200")
      (footprint "eagle-import:MINI_MELF-0204W")
      (fields (field (name "SPICEPREFIX") "R"))
      (libsource (lib "eagle-import") (part "R-EU_MELF0204W"))
    )
    (comp (ref "R55")
      (value "10")
      (footprint "eagle-import:MINI_MELF-0204W")
      (fields (field (name "SPICEPREFIX") "R"))
      (libsource (lib "eagle-import") (part "R-EU_MELF0204W"))
    )
    (comp (ref "R56")
      (value "10")
      (footprint "eagle-import:MINI_MELF-0204W")
      (fields (field (name "SPICEPREFIX") "R"))
      (libsource (lib "eagle-import") (part "R-EU_MELF0204W"))
    )
    (comp (ref "R57")
      (value "200")
      (footprint "eagle-import:MINI_MELF-0204W")
      (fields (field (name "SPICEPREFIX") "R"))
      (libsource (lib "eagle-import") (part "R-EU_MELF0204W"))
    )
    (comp (ref "R58")
      (value "560")
      (footprint "eagle-import:MINI_MELF-0204W")
      (fields (field (name "SPICEPREFIX") "R"))
      (libsource (lib "eagle-import") (part "R-EU_MELF0204W"))
    )
    (comp (ref "R59")
      (value "10")
      (footprint "eagle-import:MINI_MELF-0204W")
      (fields (field (name "SPICEPREFIX") "R"))
      (libsource (lib "eagle-import") (part "R-EU_MELF0204W"))
    )
    (comp (ref "R60")
      (value "10")
      (footprint "eagle-import:MINI_MELF-0204W")
      (fields (field (name "SPICEPREFIX") "R"))
      (libsource (lib "eagle-import") (part "R-EU_MELF0204W"))
    )
    (comp (ref "R61")
      (value "560")
      (footprint "eagle-import:MINI_MELF-0204W")
      (fields (field (name "SPICEPREFIX") "R"))
      (libsource (lib "eagle-import") (part "R-EU_MELF0204W"))
    )
    (comp (ref "R62")
      (value "100")
      (footprint "eagle-import:MINI_MELF-0204W")
      (fields (field (name "SPICEPREFIX") "R"))
      (libsource (lib "eagle-import") (part "R-EU_MELF0204W"))
    )
    (comp (ref "R63")
      (value "200")
      (footprint "eagle-import:MINI_MELF-0204W")
      (fields (field (name "SPICEPREFIX") "R"))
      (libsource (lib "eagle-import") (part "R-EU_MELF0204W"))
    )
    (comp (ref "R64")
      (value "100")
      (footprint "eagle-import:MINI_MELF-0204W")
      (fields (field (name "SPICEPREFIX") "R"))
      (libsource (lib "eagle-import") (part "R-EU_MELF0204W"))
    )
    (comp (ref "R65")
      (value "68k")
      (footprint "eagle-import:MINI_MELF-0204W")
      (fields (field (name "SPICEPREFIX") "R"))
      (libsource (lib "eagle-import") (part "R-EU_MELF0204W"))
    )
    (comp (ref "R66")
      (value "500")
      (footprint "eagle-import:MINI_MELF-0204W")
      (fields (field (name "SPICEPREFIX") "R"))
      (libsource (lib "eagle-import") (part "R-EU_MELF0204W"))
    )
    (comp (ref "R67")
      (value "100")
      (footprint "eagle-import:MINI_MELF-0204W")
      (fields (field (name "SPICEPREFIX") "R"))
      (libsource (lib "eagle-import") (part "R-EU_MELF0204W"))
    )
    (comp (ref "R68")
      (value "5k")
      (footprint "eagle-import:MINI_MELF-0204W")
      (fields (field (name "SPICEPREFIX") "R"))
      (libsource (lib "eagle-import") (part "R-EU_MELF0204W"))
    )
    (comp (ref "R69")
      (value "5k")
      (footprint "eagle-import:MINI_MELF-0204W")
      (fields (field (name "SPICEPREFIX") "R"))
      (libsource (lib "eagle-import") (part "R-EU_MELF0204W"))
    )
    (comp (ref "R70")
      (value "100")
      (footprint "eagle-import:MINI_MELF-0204W")
      (fields (field (name "SPICEPREFIX") "R"))
      (libsource (lib "eagle-import") (part "R-EU_MELF0204W"))
    )
    (comp (ref "R71")
      (value "100")
      (footprint "eagle-import:MINI_MELF-0204W")
      (fields (field (name "SPICEPREFIX") "R"))
      (libsource (lib "eagle-import") (part "R-EU_MELF0204W"))
    )
    (comp (ref "R72")
      (value "100")
      (footprint "eagle-import:MINI_MELF-0204W")
      (fields (field (name "SPICEPREFIX") "R"))
      (libsource (lib "eagle-import") (part "R-EU_MELF0204W"))
    )
    (comp (ref "R73")
      (value "7k")
      (footprint "eagle-import:MINI_MELF-0204W")
      (fields (field (name "SPICEPREFIX") "R"))
      (libsource (lib "eagle-import") (part "R-EU_MELF0204W"))
    )
    (comp (ref "R74")
      (value "5k")
      (footprint "eagle-import:RTRIM3296W")
      (fields (field (name "SPICEPREFIX") "Z"))
      (libsource (lib "eagle-import") (part "R-TRIMM3296W"))
    )
    (comp (ref "R75")
      (value "1M")
      (footprint "eagle-import:MINI_MELF-0204W")
      (fields (field (name "SPICEPREFIX") "R"))
      (libsource (lib "eagle-import") (part "R-EU_MELF0204W"))
    )
    (comp (ref "R76")
      (value "1M")
      (footprint "eagle-import:MINI_MELF-0204W")
      (fields (field (name "SPICEPREFIX") "R"))
      (libsource (lib "eagle-import") (part "R-EU_MELF0204W"))
    )
    (comp (ref "R77")
      (value "1k")
      (footprint "eagle-import:MINI_MELF-0204W")
      (fields (field (name "SPICEPREFIX") "R"))
      (libsource (lib "eagle-import") (part "R-EU_MELF0204W"))
    )
    (comp (ref "R78")
      (value "220")
      (footprint "eagle-import:MINI_MELF-0204W")
      (fields (field (name "SPICEPREFIX") "R"))
      (libsource (lib "eagle-import") (part "R-EU_MELF0204W"))
    )
    (comp (ref "R79")
      (value "100k")
      (footprint "eagle-import:MINI_MELF-0204W")
      (fields (field (name "SPICEPREFIX") "R"))
      (libsource (lib "eagle-import") (part "R-EU_MELF0204W"))
    )
    (comp (ref "R80")
      (value "0.5")
      (footprint "eagle-import:R2512")
      (fields (field (name "SPICEPREFIX") "R"))
      (libsource (lib "eagle-import") (part "R-EU_R2512"))
    )
    (comp (ref "R81")
      (value "0.5")
      (footprint "eagle-import:R2512")
      (fields (field (name "SPICEPREFIX") "R"))
      (libsource (lib "eagle-import") (part "R-EU_R2512"))
    )
    (comp (ref "R82")
      (value "100k")
      (footprint "eagle-import:MINI_MELF-0204W")
      (fields (field (name "SPICEPREFIX") "R"))
      (libsource (lib "eagle-import") (part "R-EU_MELF0204W"))
    )
    (comp (ref "R83")
      (value "1k")
      (footprint "eagle-import:MINI_MELF-0204W")
      (fields (field (name "SPICEPREFIX") "R"))
      (libsource (lib "eagle-import") (part "R-EU_MELF0204W"))
    )
    (comp (ref "R84")
      (value "20k")
      (footprint "eagle-import:MINI_MELF-0204W")
      (fields (field (name "SPICEPREFIX") "R"))
      (libsource (lib "eagle-import") (part "R-EU_MELF0204W"))
    )
    (comp (ref "R85")
      (value "100k")
      (footprint "eagle-import:MINI_MELF-0204W")
      (fields (field (name "SPICEPREFIX") "R"))
      (libsource (lib "eagle-import") (part "R-EU_MELF0204W"))
    )
    (comp (ref "R86")
      (value "200")
      (footprint "eagle-import:MINI_MELF-0204W")
      (fields (field (name "SPICEPREFIX") "R"))
      (libsource (lib "eagle-import") (part "R-EU_MELF0204W"))
    )
    (comp (ref "R87")
      (value "10")
      (footprint "eagle-import:MINI_MELF-0204W")
      (fields (field (name "SPICEPREFIX") "R"))
      (libsource (lib "eagle-import") (part "R-EU_MELF0204W"))
    )
    (comp (ref "R88")
      (value "10")
      (footprint "eagle-import:MINI_MELF-0204W")
      (fields (field (name "SPICEPREFIX") "R"))
      (libsource (lib "eagle-import") (part "R-EU_MELF0204W"))
    )
    (comp (ref "R89")
      (value "200")
      (footprint "eagle-import:MINI_MELF-0204W")
      (fields (field (name "SPICEPREFIX") "R"))
      (libsource (lib "eagle-import") (part "R-EU_MELF0204W"))
    )
    (comp (ref "R90")
      (value "560")
      (footprint "eagle-import:MINI_MELF-0204W")
      (fields (field (name "SPICEPREFIX") "R"))
      (libsource (lib "eagle-import") (part "R-EU_MELF0204W"))
    )
    (comp (ref "R91")
      (value "10")
      (footprint "eagle-import:MINI_MELF-0204W")
      (fields (field (name "SPICEPREFIX") "R"))
      (libsource (lib "eagle-import") (part "R-EU_MELF0204W"))
    )
    (comp (ref "R92")
      (value "10")
      (footprint "eagle-import:MINI_MELF-0204W")
      (fields (field (name "SPICEPREFIX") "R"))
      (libsource (lib "eagle-import") (part "R-EU_MELF0204W"))
    )
    (comp (ref "R93")
      (value "560")
      (footprint "eagle-import:MINI_MELF-0204W")
      (fields (field (name "SPICEPREFIX") "R"))
      (libsource (lib "eagle-import") (part "R-EU_MELF0204W"))
    )
    (comp (ref "R94")
      (value "100")
      (footprint "eagle-import:MINI_MELF-0204W")
      (fields (field (name "SPICEPREFIX") "R"))
      (libsource (lib "eagle-import") (part "R-EU_MELF0204W"))
    )
    (comp (ref "R95")
      (value "200")
      (footprint "eagle-import:MINI_MELF-0204W")
      (fields (field (name "SPICEPREFIX") "R"))
      (libsource (lib "eagle-import") (part "R-EU_MELF0204W"))
    )
    (comp (ref "R96")
      (value "100")
      (footprint "eagle-import:MINI_MELF-0204W")
      (fields (field (name "SPICEPREFIX") "R"))
      (libsource (lib "eagle-import") (part "R-EU_MELF0204W"))
    )
    (comp (ref "R97")
      (value "68k")
      (footprint "eagle-import:MINI_MELF-0204W")
      (fields (field (name "SPICEPREFIX") "R"))
      (libsource (lib "eagle-import") (part "R-EU_MELF0204W"))
    )
    (comp (ref "R98")
      (value "500")
      (footprint "eagle-import:MINI_MELF-0204W")
      (fields (field (name "SPICEPREFIX") "R"))
      (libsource (lib "eagle-import") (part "R-EU_MELF0204W"))
    )
    (comp (ref "R99")
      (value "100")
      (footprint "eagle-import:MINI_MELF-0204W")
      (fields (field (name "SPICEPREFIX") "R"))
      (libsource (lib "eagle-import") (part "R-EU_MELF0204W"))
    )
    (comp (ref "R100")
      (value "5k")
      (footprint "eagle-import:MINI_MELF-0204W")
      (fields (field (name "SPICEPREFIX") "R"))
      (libsource (lib "eagle-import") (part "R-EU_MELF0204W"))
    )
    (comp (ref "R101")
      (value "5k")
      (footprint "eagle-import:MINI_MELF-0204W")
      (fields (field (name "SPICEPREFIX") "R"))
      (libsource (lib "eagle-import") (part "R-EU_MELF0204W"))
    )
    (comp (ref "R102")
      (value "100")
      (footprint "eagle-import:MINI_MELF-0204W")
      (fields (field (name "SPICEPREFIX") "R"))
      (libsource (lib "eagle-import") (part "R-EU_MELF0204W"))
    )
    (comp (ref "R103")
      (value "100")
      (footprint "eagle-import:MINI_MELF-0204W")
      (fields (field (name "SPICEPREFIX") "R"))
      (libsource (lib "eagle-import") (part "R-EU_MELF0204W"))
    )
    (comp (ref "R104")
      (value "100")
      (footprint "eagle-import:MINI_MELF-0204W")
      (fields (field (name "SPICEPREFIX") "R"))
      (libsource (lib "eagle-import") (part "R-EU_MELF0204W"))
    )
    (comp (ref "R105")
      (value "7k")
      (footprint "eagle-import:MINI_MELF-0204W")
      (fields (field (name "SPICEPREFIX") "R"))
      (libsource (lib "eagle-import") (part "R-EU_MELF0204W"))
    )
    (comp (ref "R106")
      (value "5k")
      (footprint "eagle-import:RTRIM3296W")
      (fields (field (name "SPICEPREFIX") "Z"))
      (libsource (lib "eagle-import") (part "R-TRIMM3296W"))
    )
    (comp (ref "R107")
      (value "1M")
      (footprint "eagle-import:MINI_MELF-0204W")
      (fields (field (name "SPICEPREFIX") "R"))
      (libsource (lib "eagle-import") (part "R-EU_MELF0204W"))
    )
    (comp (ref "R108")
      (value "1M")
      (footprint "eagle-import:MINI_MELF-0204W")
      (fields (field (name "SPICEPREFIX") "R"))
      (libsource (lib "eagle-import") (part "R-EU_MELF0204W"))
    )
    (comp (ref "R109")
      (value "1k")
      (footprint "eagle-import:MINI_MELF-0204W")
      (fields (field (name "SPICEPREFIX") "R"))
      (libsource (lib "eagle-import") (part "R-EU_MELF0204W"))
    )
    (comp (ref "R110")
      (value "220")
      (footprint "eagle-import:MINI_MELF-0204W")
      (fields (field (name "SPICEPREFIX") "R"))
      (libsource (lib "eagle-import") (part "R-EU_MELF0204W"))
    )
    (comp (ref "R111")
      (value "100k")
      (footprint "eagle-import:MINI_MELF-0204W")
      (fields (field (name "SPICEPREFIX") "R"))
      (libsource (lib "eagle-import") (part "R-EU_MELF0204W"))
    )
    (comp (ref "R112")
      (value "0.5")
      (footprint "eagle-import:R2512")
      (fields (field (name "SPICEPREFIX") "R"))
      (libsource (lib "eagle-import") (part "R-EU_R2512"))
    )
    (comp (ref "R113")
      (value "0.5")
      (footprint "eagle-import:R2512")
      (fields (field (name "SPICEPREFIX") "R"))
      (libsource (lib "eagle-import") (part "R-EU_R2512"))
    )
    (comp (ref "R114")
      (value "100k")
      (footprint "eagle-import:MINI_MELF-0204W")
      (fields (field (name "SPICEPREFIX") "R"))
      (libsource (lib "eagle-import") (part "R-EU_MELF0204W"))
    )
    (comp (ref "R133")
      (value "R-EU_R2512")
      (footprint "eagle-import:R2512")
      (libsource (lib "eagle-import") (part "R-EU_R2512"))
    )
    (comp (ref "C37")
      (value "10000uF")
      (footprint "eagle-import:EB35D-8.5")
      (libsource (lib "eagle-import") (part "CPOL-EU"))
    )
    (comp (ref "C38")
      (value "10000uF")
      (footprint "eagle-import:EB35D-8.5")
      (libsource (lib "eagle-import") (part "CPOL-EU"))
    )
    (comp (ref "C39")
      (value "0.1uF")
      (footprint "eagle-import:C050-045X075")
      (libsource (lib "eagle-import") (part "C-EU050-045X075"))
    )
    (comp (ref "C40")
      (value "10uF")
      (footprint "eagle-import:C1206")
      (libsource (lib "eagle-import") (part "C-EUC1206"))
    )
    (comp (ref "C41")
      (value "10uF")
      (footprint "eagle-import:C1206")
      (libsource (lib "eagle-import") (part "C-EUC1206"))
    )
    (comp (ref "C42")
      (value "0.1uF")
      (footprint "eagle-import:C050-045X075")
      (libsource (lib "eagle-import") (part "C-EU050-045X075"))
    )
    (comp (ref "C43")
      (value "0.1uF")
      (footprint "eagle-import:C0805")
      (libsource (lib "eagle-import") (part "C-EUC0805"))
    )
    (comp (ref "C44")
      (value "0.1uF")
      (footprint "eagle-import:C0805")
      (libsource (lib "eagle-import") (part "C-EUC0805"))
    )
    (comp (ref "C45")
      (value "0.1uF")
      (footprint "eagle-import:C0805")
      (libsource (lib "eagle-import") (part "C-EUC0805"))
    )
    (comp (ref "C46")
      (value "0.1uF")
      (footprint "eagle-import:C0805")
      (libsource (lib "eagle-import") (part "C-EUC0805"))
    )
    (comp (ref "C47")
      (value "10uF")
      (footprint "eagle-import:C1206")
      (libsource (lib "eagle-import") (part "C-EUC1206"))
    )
    (comp (ref "C48")
      (value "10uF")
      (footprint "eagle-import:C1206")
      (libsource (lib "eagle-import") (part "C-EUC1206"))
    )
    (comp (ref "C49")
      (value "0.1uF")
      (footprint "eagle-import:C0805")
      (libsource (lib "eagle-import") (part "C-EUC0805"))
    )
    (comp (ref "C50")
      (value "0.1uF")
      (footprint "eagle-import:C0805")
      (libsource (lib "eagle-import") (part "C-EUC0805"))
    )
    (comp (ref "C51")
      (value "47p")
      (footprint "eagle-import:C0805")
      (libsource (lib "eagle-import") (part "C-EUC0805"))
    )
    (comp (ref "C52")
      (value "47p")
      (footprint "eagle-import:C0805")
      (libsource (lib "eagle-import") (part "C-EUC0805"))
    )
    (comp (ref "C53")
      (value "10uF")
      (footprint "eagle-import:C1206")
      (libsource (lib "eagle-import") (part "C-EUC1206"))
    )
    (comp (ref "C54")
      (value "10uF")
      (footprint "eagle-import:C1206")
      (libsource (lib "eagle-import") (part "C-EUC1206"))
    )
    (comp (ref "C55")
      (value "4.7uF")
      (footprint "eagle-import:C050-075X075")
      (libsource (lib "eagle-import") (part "C-EU050-075X075"))
    )
    (comp (ref "C56")
      (value "4.7uF")
      (footprint "eagle-import:C050-075X075")
      (libsource (lib "eagle-import") (part "C-EU050-075X075"))
    )
    (comp (ref "C58")
      (value "0.1uF")
      (footprint "eagle-import:C050-045X075")
      (libsource (lib "eagle-import") (part "C-EU050-045X075"))
    )
    (comp (ref "C60")
      (value "0.1uF")
      (footprint "eagle-import:C050-045X075")
      (libsource (lib "eagle-import") (part "C-EU050-045X075"))
    )
    (comp (ref "D13")
      (value "BZT55B10")
      (footprint "eagle-import:SOD80C")
      (libsource (lib "eagle-import") (part "DIODE-SOD80C"))
    )
    (comp (ref "D14")
      (value "BZT55B10")
      (footprint "eagle-import:SOD80C")
      (libsource (lib "eagle-import") (part "DIODE-SOD80C"))
    )
    (comp (ref "D15")
      (value "S1G")
      (footprint "eagle-import:DO214AA")
      (libsource (lib "eagle-import") (part "DIODE-DO214AA"))
    )
    (comp (ref "D16")
      (value "S1G")
      (footprint "eagle-import:DO214AA")
      (libsource (lib "eagle-import") (part "DIODE-DO214AA"))
    )
    (comp (ref "D17")
      (value "LT1236-10")
      (footprint "eagle-import:SO8")
      (libsource (lib "eagle-import") (part "LINEAR-TECHNOLOGY_LT1021-VSO-8"))
    )
    (comp (ref "D18")
      (value "LT1236-10")
      (footprint "eagle-import:SO8")
      (libsource (lib "eagle-import") (part "LINEAR-TECHNOLOGY_LT1021-VSO-8"))
    )
    (comp (ref "IC5")
      (value "OPA827")
      (footprint "eagle-import:SOIC8")
      (libsource (lib "eagle-import") (part "LT10S837C"))
    )
    (comp (ref "IC6")
      (value "OPA827")
      (footprint "eagle-import:SOIC8")
      (libsource (lib "eagle-import") (part "LT10S837C"))
    )
    (comp (ref "LED13")
      (value "RED")
      (footprint "eagle-import:LED_SML1206")
      (libsource (lib "eagle-import") (part "LEDVWV1206"))
    )
    (comp (ref "LED14")
      (value "RED")
      (footprint "eagle-import:LED_SML1206")
      (libsource (lib "eagle-import") (part "LEDVWV1206"))
    )
    (comp (ref "LED15")
      (value "RED")
      (footprint "eagle-import:LED_SML1206")
      (libsource (lib "eagle-import") (part "LEDVWV1206"))
    )
    (comp (ref "LED16")
      (value "RED")
      (footprint "eagle-import:LED_SML1206")
      (libsource (lib "eagle-import") (part "LEDVWV1206"))
    )
    (comp (ref "LED17")
      (value "RED")
      (footprint "eagle-import:LED_SML1206")
      (libsource (lib "eagle-import") (part "LEDVWV1206"))
    )
    (comp (ref "LED18")
      (value "RED")
      (footprint "eagle-import:LED_SML1206")
      (libsource (lib "eagle-import") (part "LEDVWV1206"))
    )
    (comp (ref "Q79")
      (value "KSC1845")
      (footprint "eagle-import:TRANSISTOR_TO92-ECB_N")
      (libsource (lib "eagle-import") (part "BJT_NPNKSC1845"))
    )
    (comp (ref "Q80")
      (value "KSA992")
      (footprint "eagle-import:TRANSISTOR_TO92-ECB_P")
      (libsource (lib "eagle-import") (part "BJT_PNPKSA992"))
    )
    (comp (ref "Q81")
      (value "KSA992")
      (footprint "eagle-import:TRANSISTOR_TO92-ECB_P")
      (libsource (lib "eagle-import") (part "BJT_PNPKSA992"))
    )
    (comp (ref "Q82")
      (value "KSC1845")
      (footprint "eagle-import:TRANSISTOR_TO92-ECB_N")
      (libsource (lib "eagle-import") (part "BJT_NPNKSC1845"))
    )
    (comp (ref "Q83")
      (value "KSA992")
      (footprint "eagle-import:TRANSISTOR_TO92-ECB_P")
      (libsource (lib "eagle-import") (part "BJT_PNPKSA992"))
    )
    (comp (ref "Q84")
      (value "KSC1845")
      (footprint "eagle-import:TRANSISTOR_TO92-ECB_N")
      (libsource (lib "eagle-import") (part "BJT_NPNKSC1845"))
    )
    (comp (ref "Q85")
      (value "KSA992")
      (footprint "eagle-import:TRANSISTOR_TO92-ECB_P")
      (libsource (lib "eagle-import") (part "BJT_PNPKSA992"))
    )
    (comp (ref "Q86")
      (value "KSC1845")
      (footprint "eagle-import:TRANSISTOR_TO92-ECB_N")
      (libsource (lib "eagle-import") (part "BJT_NPNKSC1845"))
    )
    (comp (ref "Q87")
      (value "KSC1845")
      (footprint "eagle-import:TRANSISTOR_TO92-ECB_N")
      (libsource (lib "eagle-import") (part "BJT_NPNKSC1845"))
    )
    (comp (ref "Q88")
      (value "KSA992")
      (footprint "eagle-import:TRANSISTOR_TO92-ECB_P")
      (libsource (lib "eagle-import") (part "BJT_PNPKSA992"))
    )
    (comp (ref "Q89")
      (value "MJL4281A")
      (footprint "eagle-import:TRANSISTOR_TO247_BCE_N")
      (libsource (lib "eagle-import") (part "BJT_NPNMJL4281"))
    )
    (comp (ref "Q90")
      (value "MJL4302A")
      (footprint "eagle-import:TRANSISTOR_TO247_BCE_P")
      (libsource (lib "eagle-import") (part "BJT_PNPMJL4302"))
    )
    (comp (ref "Q91")
      (value "DN2540")
      (footprint "eagle-import:TRANSISTOR_TO92-SGD_N")
      (libsource (lib "eagle-import") (part "DN2540"))
    )
    (comp (ref "Q92")
      (value "DN2540")
      (footprint "eagle-import:TRANSISTOR_TO92-SGD_N")
      (libsource (lib "eagle-import") (part "DN2540"))
    )
    (comp (ref "R115")
      (value "10k")
      (footprint "eagle-import:MINI_MELF-0204W")
      (libsource (lib "eagle-import") (part "R-EU_MELF0204W"))
    )
    (comp (ref "R116")
      (value "10k")
      (footprint "eagle-import:MINI_MELF-0204W")
      (libsource (lib "eagle-import") (part "R-EU_MELF0204W"))
    )
    (comp (ref "R117")
      (value "1k")
      (footprint "eagle-import:MINI_MELF-0204W")
      (libsource (lib "eagle-import") (part "R-EU_MELF0204W"))
    )
    (comp (ref "R118")
      (value "1k")
      (footprint "eagle-import:MINI_MELF-0204W")
      (libsource (lib "eagle-import") (part "R-EU_MELF0204W"))
    )
    (comp (ref "R119")
      (value "100")
      (footprint "eagle-import:MINI_MELF-0204W")
      (libsource (lib "eagle-import") (part "R-EU_MELF0204W"))
    )
    (comp (ref "R120")
      (value "10")
      (footprint "eagle-import:MINI_MELF-0204W")
      (libsource (lib "eagle-import") (part "R-EU_MELF0204W"))
    )
    (comp (ref "R121")
      (value "10")
      (footprint "eagle-import:MINI_MELF-0204W")
      (libsource (lib "eagle-import") (part "R-EU_MELF0204W"))
    )
    (comp (ref "R122")
      (value "100")
      (footprint "eagle-import:MINI_MELF-0204W")
      (libsource (lib "eagle-import") (part "R-EU_MELF0204W"))
    )
    (comp (ref "R123")
      (value "10")
      (footprint "eagle-import:MINI_MELF-0204W")
      (libsource (lib "eagle-import") (part "R-EU_MELF0204W"))
    )
    (comp (ref "R124")
      (value "10")
      (footprint "eagle-import:MINI_MELF-0204W")
      (libsource (lib "eagle-import") (part "R-EU_MELF0204W"))
    )
    (comp (ref "R125")
      (value "1k")
      (footprint "eagle-import:MINI_MELF-0204W")
      (libsource (lib "eagle-import") (part "R-EU_MELF0204W"))
    )
    (comp (ref "R126")
      (value "1k")
      (footprint "eagle-import:MINI_MELF-0204W")
      (libsource (lib "eagle-import") (part "R-EU_MELF0204W"))
    )
    (comp (ref "R127")
      (value "1.5k")
      (footprint "eagle-import:MINI_MELF-0204W")
      (libsource (lib "eagle-import") (part "R-EU_MELF0204W"))
    )
    (comp (ref "R128")
      (value "1.5k")
      (footprint "eagle-import:MINI_MELF-0204W")
      (libsource (lib "eagle-import") (part "R-EU_MELF0204W"))
    )
    (comp (ref "R129")
      (value "1.5k")
      (footprint "eagle-import:MINI_MELF-0204W")
      (libsource (lib "eagle-import") (part "R-EU_MELF0204W"))
    )
    (comp (ref "R130")
      (value "1.5k")
      (footprint "eagle-import:MINI_MELF-0204W")
      (libsource (lib "eagle-import") (part "R-EU_MELF0204W"))
    )
    (comp (ref "R131")
      (value "10k")
      (footprint "eagle-import:MINI_MELF-0204W")
      (libsource (lib "eagle-import") (part "R-EU_MELF0204W"))
    )
    (comp (ref "R132")
      (value "10k")
      (footprint "eagle-import:MINI_MELF-0204W")
      (libsource (lib "eagle-import") (part "R-EU_MELF0204W"))
    )
  )
  (nets
    (net (code "1") (name "AC1") (class "Default")
      (node (ref "Q100") (pin "5") (pinfunction "D_5") (pintype "passive"))
      (node (ref "Q100") (pin "6") (pinfunction "D_6") (pintype "passive"))
      (node (ref "Q100") (pin "7") (pinfunction "D_7") (pintype "passive"))
      (node (ref "Q100") (pin "8") (pinfunction "D_8") (pintype "passive"))
      (node (ref "Q100") (pin "TH") (pinfunction "D_TH") (pintype "passive"))
      (node (ref "Q97") (pin "1") (pinfunction "S_1") (pintype "passive"))
      (node (ref "Q97") (pin "2") (pinfunction "S_2") (pintype "passive"))
      (node (ref "Q97") (pin "3") (pinfunction "S_3") (pintype "passive"))
      (node (ref "U$2") (pin "1") (pinfunction "1_IN2_1") (pintype "bidirectional"))
      (node (ref "X3") (pin "2") (pinfunction "S_2") (pintype "passive"))
    )
    (net (code "2") (name "AC2") (class "Default")
      (node (ref "Q98") (pin "1") (pinfunction "S_1") (pintype "passive"))
      (node (ref "Q98") (pin "2") (pinfunction "S_2") (pintype "passive"))
      (node (ref "Q98") (pin "3") (pinfunction "S_3") (pintype "passive"))
      (node (ref "Q99") (pin "5") (pinfunction "D_5") (pintype "passive"))
      (node (ref "Q99") (pin "6") (pinfunction "D_6") (pintype "passive"))
      (node (ref "Q99") (pin "7") (pinfunction "D_7") (pintype "passive"))
      (node (ref "Q99") (pin "8") (pinfunction "D_8") (pintype "passive"))
      (node (ref "Q99") (pin "TH") (pinfunction "D_TH") (pintype "passive"))
      (node (ref "U$2") (pin "12") (pinfunction "8_IN1_12") (pintype "bidirectional"))
      (node (ref "X3") (pin "1") (pinfunction "S_1") (pintype "passive"))
    )
    (net (code "3") (name "AC3") (class "Default")
      (node (ref "Q105") (pin "1") (pinfunction "S_1") (pintype "passive"))
      (node (ref "Q105") (pin "2") (pinfunction "S_2") (pintype "passive"))
      (node (ref "Q105") (pin "3") (pinfunction "S_3") (pintype "passive"))
      (node (ref "Q108") (pin "5") (pinfunction "D_5") (pintype "passive"))
      (node (ref "Q108") (pin "6") (pinfunction "D_6") (pintype "passive"))
      (node (ref "Q108") (pin "7") (pinfunction "D_7") (pintype "passive"))
      (node (ref "Q108") (pin "8") (pinfunction "D_8") (pintype "passive"))
      (node (ref "Q108") (pin "TH") (pinfunction "D_TH") (pintype "passive"))
      (node (ref "U$4") (pin "1") (pinfunction "1_IN2_1") (pintype "bidirectional"))
      (node (ref "X2") (pin "2") (pinfunction "S_2") (pintype "passive"))
    )
    (net (code "4") (name "AC4") (class "Default")
      (node (ref "Q106") (pin "1") (pinfunction "S_1") (pintype "passive"))
      (node (ref "Q106") (pin "2") (pinfunction "S_2") (pintype "passive"))
      (node (ref "Q106") (pin "3") (pinfunction "S_3") (pintype "passive"))
      (node (ref "Q107") (pin "5") (pinfunction "D_5") (pintype "passive"))
      (node (ref "Q107") (pin "6") (pinfunction "D_6") (pintype "passive"))
      (node (ref "Q107") (pin "7") (pinfunction "D_7") (pintype "passive"))
      (node (ref "Q107") (pin "8") (pinfunction "D_8") (pintype "passive"))
      (node (ref "Q107") (pin "TH") (pinfunction "D_TH") (pintype "passive"))
      (node (ref "U$4") (pin "12") (pinfunction "8_IN1_12") (pintype "bidirectional"))
      (node (ref "X2") (pin "1") (pinfunction "S_1") (pintype "passive"))
    )
    (net (code "5") (name "BOUT+") (class "Default")
      (node (ref "R29") (pin "1") (pinfunction "1_1") (pintype "passive"))
      (node (ref "R30") (pin "1") (pinfunction "1_1") (pintype "passive"))
      (node (ref "R31") (pin "2") (pinfunction "2_2") (pintype "passive"))
      (node (ref "R34") (pin "1") (pinfunction "1_1") (pintype "passive"))
      (node (ref "R35") (pin "2") (pinfunction "2_2") (pintype "passive"))
      (node (ref "R51") (pin "2") (pinfunction "2_2") (pintype "passive"))
    )
    (net (code "6") (name "BOUT-") (class "Default")
      (node (ref "R44") (pin "1") (pinfunction "1_1") (pintype "passive"))
      (node (ref "R45") (pin "1") (pinfunction "1_1") (pintype "passive"))
      (node (ref "R46") (pin "2") (pinfunction "2_2") (pintype "passive"))
      (node (ref "R49") (pin "1") (pinfunction "1_1") (pintype "passive"))
      (node (ref "R50") (pin "2") (pinfunction "2_2") (pintype "passive"))
      (node (ref "R83") (pin "2") (pinfunction "2_2") (pintype "passive"))
    )
    (net (code "7") (name "D5V") (class "Default")
      (node (ref "C61") (pin "1") (pinfunction "1_1") (pintype "passive"))
      (node (ref "C64") (pin "1") (pinfunction "1_1") (pintype "passive"))
      (node (ref "J1") (pin "1") (pinfunction "S_1") (pintype "passive"))
      (node (ref "J2") (pin "1") (pinfunction "S_1") (pintype "passive"))
      (node (ref "U$1") (pin "8") (pinfunction "VDD_8") (pintype "bidirectional"))
      (node (ref "U$3") (pin "8") (pinfunction "VDD_8") (pintype "bidirectional"))
    )
    (net (code "8") (name "DGND") (class "Default")
      (node (ref "C61") (pin "2") (pinfunction "2_2") (pintype "passive"))
      (node (ref "C62") (pin "2") (pinfunction "2_2") (pintype "passive"))
      (node (ref "C63") (pin "2") (pinfunction "2_2") (pintype "passive"))
      (node (ref "C64") (pin "2") (pinfunction "2_2") (pintype "passive"))
      (node (ref "J1") (pin "3") (pinfunction "S_3") (pintype "passive"))
      (node (ref "J2") (pin "3") (pinfunction "S_3") (pintype "passive"))
      (node (ref "U$1") (pin "5") (pinfunction "GND_5") (pintype "bidirectional"))
      (node (ref "U$3") (pin "5") (pinfunction "GND_5") (pintype "bidirectional"))
    )
    (net (code "9") (name "GND") (class "Default")
      (node (ref "C10") (pin "1") (pinfunction "1_1") (pintype "passive"))
      (node (ref "C11") (pin "2") (pinfunction "2_2") (pintype "passive"))
      (node (ref "C12") (pin "1") (pinfunction "1_1") (pintype "passive"))
      (node (ref "C14") (pin "1") (pinfunction "1_1") (pintype "passive"))
      (node (ref "C15") (pin "2") (pinfunction "2_2") (pintype "passive"))
      (node (ref "C17") (pin "2") (pinfunction "2_2") (pintype "passive"))
      (node (ref "C19") (pin "1") (pinfunction "1_1") (pintype "passive"))
      (node (ref "C20") (pin "2") (pinfunction "2_2") (pintype "passive"))
      (node (ref "C22") (pin "1") (pinfunction "1_1") (pintype "passive"))
      (node (ref "C23") (pin "2") (pinfunction "2_2") (pintype "passive"))
      (node (ref "C24") (pin "1") (pinfunction "1_1") (pintype "passive"))
      (node (ref "C25") (pin "-") (pinfunction "-_-") (pintype "passive"))
      (node (ref "C26") (pin "+") (pinfunction "+_+") (pintype "passive"))
      (node (ref "C27") (pin "2") (pinfunction "2_2") (pintype "passive"))
      (node (ref "C29") (pin "1") (pinfunction "1_1") (pintype "passive"))
      (node (ref "C3") (pin "1") (pinfunction "1_1") (pintype "passive"))
      (node (ref "C30") (pin "2") (pinfunction "2_2") (pintype "passive"))
      (node (ref "C32") (pin "1") (pinfunction "1_1") (pintype "passive"))
      (node (ref "C33") (pin "2") (pinfunction "2_2") (pintype "passive"))
      (node (ref "C34") (pin "1") (pinfunction "1_1") (pintype "passive"))
      (node (ref "C35") (pin "-") (pinfunction "-_-") (pintype "passive"))
      (node (ref "C36") (pin "+") (pinfunction "+_+") (pintype "passive"))
      (node (ref "C37") (pin "-") (pinfunction "-_-") (pintype "passive"))
      (node (ref "C38") (pin "+") (pinfunction "+_+") (pintype "passive"))
      (node (ref "C39") (pin "2") (pinfunction "2_2") (pintype "passive"))
      (node (ref "C4") (pin "2") (pinfunction "2_2") (pintype "passive"))
      (node (ref "C42") (pin "1") (pinfunction "1_1") (pintype "passive"))
      (node (ref "C45") (pin "1") (pinfunction "1_1") (pintype "passive"))
      (node (ref "C46") (pin "2") (pinfunction "2_2") (pintype "passive"))
      (node (ref "C47") (pin "2") (pinfunction "2_2") (pintype "passive"))
      (node (ref "C48") (pin "1") (pinfunction "1_1") (pintype "passive"))
      (node (ref "C49") (pin "2") (pinfunction "2_2") (pintype "passive"))
      (node (ref "C5") (pin "-") (pinfunction "-_-") (pintype "passive"))
      (node (ref "C50") (pin "1") (pinfunction "1_1") (pintype "passive"))
      (node (ref "C55") (pin "1") (pinfunction "1_1") (pintype "passive"))
      (node (ref "C56") (pin "2") (pinfunction "2_2") (pintype "passive"))
      (node (ref "C57") (pin "2") (pinfunction "2_2") (pintype "passive"))
      (node (ref "C58") (pin "1") (pinfunction "1_1") (pintype "passive"))
      (node (ref "C59") (pin "1") (pinfunction "1_1") (pintype "passive"))
      (node (ref "C6") (pin "+") (pinfunction "+_+") (pintype "passive"))
      (node (ref "C60") (pin "2") (pinfunction "2_2") (pintype "passive"))
      (node (ref "C7") (pin "-") (pinfunction "-_-") (pintype "passive"))
      (node (ref "C8") (pin "+") (pinfunction "+_+") (pintype "passive"))
      (node (ref "C9") (pin "2") (pinfunction "2_2") (pintype "passive"))
      (node (ref "D17") (pin "4") (pinfunction "GND_4") (pintype "passive"))
      (node (ref "D18") (pin "6") (pinfunction "OUT_6") (pintype "passive"))
      (node (ref "IC1") (pin "3") (pinfunction "+IN_3") (pintype "input"))
      (node (ref "IC2") (pin "3") (pinfunction "+IN_3") (pintype "input"))
      (node (ref "IC5") (pin "7") (pinfunction "V+_7") (pintype "power_in"))
      (node (ref "IC6") (pin "4") (pinfunction "V-_4") (pintype "power_in"))
      (node (ref "LED13") (pin "C") (pinfunction "C_C") (pintype "passive"))
      (node (ref "LED14") (pin "A") (pinfunction "A_A") (pintype "passive"))
      (node (ref "LED17") (pin "C") (pinfunction "C_C") (pintype "passive"))
      (node (ref "LED18") (pin "A") (pinfunction "A_A") (pintype "passive"))
      (node (ref "PAD3") (pin "P$1") (pinfunction "P$1_P$1") (pintype "bidirectional"))
      (node (ref "PAD4") (pin "P$1") (pinfunction "P$1_P$1") (pintype "bidirectional"))
      (node (ref "Q100") (pin "1") (pinfunction "S_1") (pintype "passive"))
      (node (ref "Q100") (pin "2") (pinfunction "S_2") (pintype "passive"))
      (node (ref "Q100") (pin "3") (pinfunction "S_3") (pintype "passive"))
      (node (ref "Q105") (pin "5") (pinfunction "D_5") (pintype "passive"))
      (node (ref "Q105") (pin "6") (pinfunction "D_6") (pintype "passive"))
      (node (ref "Q105") (pin "7") (pinfunction "D_7") (pintype "passive"))
      (node (ref "Q105") (pin "8") (pinfunction "D_8") (pintype "passive"))
      (node (ref "Q105") (pin "TH") (pinfunction "D_TH") (pintype "passive"))
      (node (ref "Q106") (pin "5") (pinfunction "D_5") (pintype "passive"))
      (node (ref "Q106") (pin "6") (pinfunction "D_6") (pintype "passive"))
      (node (ref "Q106") (pin "7") (pinfunction "D_7") (pintype "passive"))
      (node (ref "Q106") (pin "8") (pinfunction "D_8") (pintype "passive"))
      (node (ref "Q106") (pin "TH") (pinfunction "D_TH") (pintype "passive"))
      (node (ref "Q85") (pin "C") (pinfunction "C_C") (pintype "passive"))
      (node (ref "Q86") (pin "C") (pinfunction "C_C") (pintype "passive"))
      (node (ref "Q99") (pin "1") (pinfunction "S_1") (pintype "passive"))
      (node (ref "Q99") (pin "2") (pinfunction "S_2") (pintype "passive"))
      (node (ref "Q99") (pin "3") (pinfunction "S_3") (pintype "passive"))
      (node (ref "R107") (pin "2") (pinfunction "2_2") (pintype "passive"))
      (node (ref "R108") (pin "1") (pinfunction "1_1") (pintype "passive"))
      (node (ref "R11") (pin "1") (pinfunction "1_1") (pintype "passive"))
      (node (ref "R111") (pin "1") (pinfunction "1_1") (pintype "passive"))
      (node (ref "R117") (pin "2") (pinfunction "2_2") (pintype "passive"))
      (node (ref "R118") (pin "1") (pinfunction "1_1") (pintype "passive"))
      (node (ref "R128") (pin "1") (pinfunction "1_1") (pintype "passive"))
      (node (ref "R129") (pin "2") (pinfunction "2_2") (pintype "passive"))
      (node (ref "R134") (pin "1") (pinfunction "1_1") (pintype "passive"))
      (node (ref "R135") (pin "1") (pinfunction "1_1") (pintype "passive"))
      (node (ref "R15") (pin "1") (pinfunction "1_1") (pintype "passive"))
      (node (ref "R16") (pin "2") (pinfunction "2_2") (pintype "passive"))
      (node (ref "R20") (pin "1") (pinfunction "1_1") (pintype "passive"))
      (node (ref "R52") (pin "1") (pinfunction "1_1") (pintype "passive"))
      (node (ref "R63") (pin "1") (pinfunction "1_1") (pintype "passive"))
      (node (ref "R75") (pin "2") (pinfunction "2_2") (pintype "passive"))
      (node (ref "R76") (pin "1") (pinfunction "1_1") (pintype "passive"))
      (node (ref "R79") (pin "1") (pinfunction "1_1") (pintype "passive"))
      (node (ref "R84") (pin "1") (pinfunction "1_1") (pintype "passive"))
      (node (ref "R95") (pin "1") (pinfunction "1_1") (pintype "passive"))
      (node (ref "U$2") (pin "7") (pinfunction "5_OUTN_7") (pintype "bidirectional"))
      (node (ref "U$2") (pin "EXP") (pinfunction "5_OUTN_EXP") (pintype "bidirectional"))
      (node (ref "U$4") (pin "9") (pinfunction "6_OUTP_9") (pintype "bidirectional"))
      (node (ref "X1") (pin "2") (pinfunction "S_2") (pintype "passive"))
    )
    (net (code "10") (name "IN+") (class "Default")
      (node (ref "Q1") (pin "4") (pinfunction "G_4") (pintype "passive"))
      (node (ref "Q4") (pin "4") (pinfunction "G_4") (pintype "passive"))
      (node (ref "R134") (pin "2") (pinfunction "2_2") (pintype "passive"))
      (node (ref "X1") (pin "3") (pinfunction "S_3") (pintype "passive"))
    )
    (net (code "11") (name "IN-") (class "Default")
      (node (ref "Q1") (pin "1") (pinfunction "G_1") (pintype "passive"))
      (node (ref "Q4") (pin "1") (pinfunction "G_1") (pintype "passive"))
      (node (ref "R135") (pin "2") (pinfunction "2_2") (pintype "passive"))
      (node (ref "X1") (pin "1") (pinfunction "S_1") (pintype "passive"))
    )
    (net (code "12") (name "Net-(C1-Pad2)") (class "Default")
      (node (ref "C1") (pin "2") (pinfunction "2_2") (pintype "passive"))
      (node (ref "R133") (pin "1") (pinfunction "1_1") (pintype "passive"))
    )
    (net (code "13") (name "Net-(C17-Pad1)") (class "Default")
      (node (ref "C17") (pin "1") (pinfunction "1_1") (pintype "passive"))
      (node (ref "Q26") (pin "B") (pinfunction "B_B") (pintype "passive"))
      (node (ref "Q27") (pin "B") (pinfunction "B_B") (pintype "passive"))
      (node (ref "R51") (pin "1") (pinfunction "1_1") (pintype "passive"))
      (node (ref "R52") (pin "2") (pinfunction "2_2") (pintype "passive"))
    )
    (net (code "14") (name "Net-(C18-Pad1)") (class "Default")
      (node (ref "C18") (pin "1") (pinfunction "1_1") (pintype "passive"))
      (node (ref "C19") (pin "2") (pinfunction "2_2") (pintype "passive"))
      (node (ref "Q39") (pin "C") (pinfunction "C_C") (pintype "passive"))
      (node (ref "Q43") (pin "C") (pinfunction "C_C") (pintype "passive"))
      (node (ref "Q45") (pin "C") (pinfunction "C_C") (pintype "passive"))
      (node (ref "Q46") (pin "B") (pinfunction "B_B") (pintype "passive"))
      (node (ref "R73") (pin "2") (pinfunction "2_2") (pintype "passive"))
      (node (ref "R75") (pin "1") (pinfunction "1_1") (pintype "passive"))
    )
    (net (code "15") (name "Net-(C27-Pad1)") (class "Default")
      (node (ref "C27") (pin "1") (pinfunction "1_1") (pintype "passive"))
      (node (ref "Q53") (pin "B") (pinfunction "B_B") (pintype "passive"))
      (node (ref "Q54") (pin "B") (pinfunction "B_B") (pintype "passive"))
      (node (ref "R83") (pin "1") (pinfunction "1_1") (pintype "passive"))
      (node (ref "R84") (pin "2") (pinfunction "2_2") (pintype "passive"))
    )
    (net (code "16") (name "Net-(C28-Pad1)") (class "Default")
      (node (ref "C28") (pin "1") (pinfunction "1_1") (pintype "passive"))
      (node (ref "C29") (pin "2") (pinfunction "2_2") (pintype "passive"))
      (node (ref "Q66") (pin "C") (pinfunction "C_C") (pintype "passive"))
      (node (ref "Q70") (pin "C") (pinfunction "C_C") (pintype "passive"))
      (node (ref "Q72") (pin "C") (pinfunction "C_C") (pintype "passive"))
      (node (ref "Q73") (pin "B") (pinfunction "B_B") (pintype "passive"))
      (node (ref "R105") (pin "2") (pinfunction "2_2") (pintype "passive"))
      (node (ref "R107") (pin "1") (pinfunction "1_1") (pintype "passive"))
    )
    (net (code "17") (name "Net-(C40-Pad1)") (class "Default")
      (node (ref "C40") (pin "1") (pinfunction "1_1") (pintype "passive"))
      (node (ref "C43") (pin "1") (pinfunction "1_1") (pintype "passive"))
      (node (ref "D13") (pin "C") (pinfunction "C_C") (pintype "passive"))
      (node (ref "Q83") (pin "C") (pinfunction "C_C") (pintype "passive"))
      (node (ref "Q87") (pin "B") (pinfunction "B_B") (pintype "passive"))
    )
    (net (code "18") (name "Net-(C40-Pad2)") (class "Default")
      (node (ref "C40") (pin "2") (pinfunction "2_2") (pintype "passive"))
      (node (ref "C43") (pin "2") (pinfunction "2_2") (pintype "passive"))
      (node (ref "D13") (pin "A") (pinfunction "A_A") (pintype "passive"))
      (node (ref "R120") (pin "1") (pinfunction "1_1") (pintype "passive"))
    )
    (net (code "19") (name "Net-(C41-Pad1)") (class "Default")
      (node (ref "C41") (pin "1") (pinfunction "1_1") (pintype "passive"))
      (node (ref "C44") (pin "1") (pinfunction "1_1") (pintype "passive"))
      (node (ref "D14") (pin "C") (pinfunction "C_C") (pintype "passive"))
      (node (ref "R121") (pin "2") (pinfunction "2_2") (pintype "passive"))
    )
    (net (code "20") (name "Net-(C41-Pad2)") (class "Default")
      (node (ref "C41") (pin "2") (pinfunction "2_2") (pintype "passive"))
      (node (ref "C44") (pin "2") (pinfunction "2_2") (pintype "passive"))
      (node (ref "D14") (pin "A") (pinfunction "A_A") (pintype "passive"))
      (node (ref "Q84") (pin "C") (pinfunction "C_C") (pintype "passive"))
      (node (ref "Q88") (pin "B") (pinfunction "B_B") (pintype "passive"))
    )
    (net (code "21") (name "Net-(D1-PadC)") (class "Default")
      (node (ref "D1") (pin "C") (pinfunction "C_C") (pintype "passive"))
      (node (ref "D2") (pin "A") (pinfunction "A_A") (pintype "passive"))
    )
    (net (code "22") (name "Net-(D2-PadC)") (class "Default")
      (node (ref "D2") (pin "C") (pinfunction "C_C") (pintype "passive"))
      (node (ref "Q25") (pin "B") (pinfunction "B_B") (pintype "passive"))
      (node (ref "R53") (pin "2") (pinfunction "2_2") (pintype "passive"))
    )
    (net (code "23") (name "Net-(D3-PadA)") (class "Default")
      (node (ref "D3") (pin "A") (pinfunction "A_A") (pintype "passive"))
      (node (ref "Q28") (pin "B") (pinfunction "B_B") (pintype "passive"))
      (node (ref "R53") (pin "1") (pinfunction "1_1") (pintype "passive"))
    )
    (net (code "24") (name "Net-(D3-PadC)") (class "Default")
      (node (ref "D3") (pin "C") (pinfunction "C_C") (pintype "passive"))
      (node (ref "D4") (pin "A") (pinfunction "A_A") (pintype "passive"))
    )
    (net (code "25") (name "Net-(D5-PadA)") (class "Default")
      (node (ref "D5") (pin "A") (pinfunction "A_A") (pintype "passive"))
      (node (ref "Q25") (pin "C") (pinfunction "C_C") (pintype "passive"))
      (node (ref "Q29") (pin "B") (pinfunction "B_B") (pintype "passive"))
    )
    (net (code "26") (name "Net-(D5-PadC)") (class "Default")
      (node (ref "D5") (pin "C") (pinfunction "C_C") (pintype "passive"))
      (node (ref "Q30") (pin "B") (pinfunction "B_B") (pintype "passive"))
      (node (ref "R55") (pin "2") (pinfunction "2_2") (pintype "passive"))
    )
    (net (code "27") (name "Net-(D6-PadA)") (class "Default")
      (node (ref "D6") (pin "A") (pinfunction "A_A") (pintype "passive"))
      (node (ref "Q31") (pin "B") (pinfunction "B_B") (pintype "passive"))
      (node (ref "R56") (pin "1") (pinfunction "1_1") (pintype "passive"))
    )
    (net (code "28") (name "Net-(D6-PadC)") (class "Default")
      (node (ref "D6") (pin "C") (pinfunction "C_C") (pintype "passive"))
      (node (ref "Q28") (pin "C") (pinfunction "C_C") (pintype "passive"))
      (node (ref "Q32") (pin "B") (pinfunction "B_B") (pintype "passive"))
    )
    (net (code "29") (name "Net-(D7-PadC)") (class "Default")
      (node (ref "D7") (pin "C") (pinfunction "C_C") (pintype "passive"))
      (node (ref "D8") (pin "A") (pinfunction "A_A") (pintype "passive"))
    )
    (net (code "30") (name "Net-(D8-PadC)") (class "Default")
      (node (ref "D8") (pin "C") (pinfunction "C_C") (pintype "passive"))
      (node (ref "Q52") (pin "B") (pinfunction "B_B") (pintype "passive"))
      (node (ref "R85") (pin "2") (pinfunction "2_2") (pintype "passive"))
    )
    (net (code "31") (name "Net-(D9-PadA)") (class "Default")
      (node (ref "D9") (pin "A") (pinfunction "A_A") (pintype "passive"))
      (node (ref "Q55") (pin "B") (pinfunction "B_B") (pintype "passive"))
      (node (ref "R85") (pin "1") (pinfunction "1_1") (pintype "passive"))
    )
    (net (code "32") (name "Net-(D10-PadA)") (class "Default")
      (node (ref "D10") (pin "A") (pinfunction "A_A") (pintype "passive"))
      (node (ref "D9") (pin "C") (pinfunction "C_C") (pintype "passive"))
    )
    (net (code "33") (name "Net-(D11-PadA)") (class "Default")
      (node (ref "D11") (pin "A") (pinfunction "A_A") (pintype "passive"))
      (node (ref "Q52") (pin "C") (pinfunction "C_C") (pintype "passive"))
      (node (ref "Q56") (pin "B") (pinfunction "B_B") (pintype "passive"))
    )
    (net (code "34") (name "Net-(D11-PadC)") (class "Default")
      (node (ref "D11") (pin "C") (pinfunction "C_C") (pintype "passive"))
      (node (ref "Q57") (pin "B") (pinfunction "B_B") (pintype "passive"))
      (node (ref "R87") (pin "2") (pinfunction "2_2") (pintype "passive"))
    )
    (net (code "35") (name "Net-(D12-PadA)") (class "Default")
      (node (ref "D12") (pin "A") (pinfunction "A_A") (pintype "passive"))
      (node (ref "Q58") (pin "B") (pinfunction "B_B") (pintype "passive"))
      (node (ref "R88") (pin "1") (pinfunction "1_1") (pintype "passive"))
    )
    (net (code "36") (name "Net-(D12-PadC)") (class "Default")
      (node (ref "D12") (pin "C") (pinfunction "C_C") (pintype "passive"))
      (node (ref "Q55") (pin "C") (pinfunction "C_C") (pintype "passive"))
      (node (ref "Q59") (pin "B") (pinfunction "B_B") (pintype "passive"))
    )
    (net (code "37") (name "Net-(D17-OUT)") (class "Default")
      (node (ref "C47") (pin "1") (pinfunction "1_1") (pintype "passive"))
      (node (ref "C49") (pin "1") (pinfunction "1_1") (pintype "passive"))
      (node (ref "D17") (pin "6") (pinfunction "OUT_6") (pintype "passive"))
      (node (ref "IC6") (pin "3") (pinfunction "+IN_3") (pintype "input"))
      (node (ref "Q91") (pin "G") (pinfunction "G_G") (pintype "passive"))
      (node (ref "R125") (pin "1") (pinfunction "1_1") (pintype "passive"))
    )
    (net (code "38") (name "Net-(D18-GND)") (class "Default")
      (node (ref "C48") (pin "2") (pinfunction "2_2") (pintype "passive"))
      (node (ref "C50") (pin "2") (pinfunction "2_2") (pintype "passive"))
      (node (ref "D18") (pin "4") (pinfunction "GND_4") (pintype "passive"))
      (node (ref "IC5") (pin "3") (pinfunction "+IN_3") (pintype "input"))
      (node (ref "Q92") (pin "D") (pinfunction "D_D") (pintype "passive"))
    )
    (net (code "39") (name "Net-(IC1--IN)") (class "Default")
      (node (ref "C13") (pin "2") (pinfunction "2_2") (pintype "passive"))
      (node (ref "IC1") (pin "2") (pinfunction "-IN_2") (pintype "input"))
      (node (ref "R29") (pin "2") (pinfunction "2_2") (pintype "passive"))
    )
    (net (code "40") (name "Net-(IC1-OUT)") (class "Default")
      (node (ref "C13") (pin "1") (pinfunction "1_1") (pintype "passive"))
      (node (ref "IC1") (pin "6") (pinfunction "OUT_6") (pintype "output"))
      (node (ref "R21") (pin "1") (pinfunction "1_1") (pintype "passive"))
    )
    (net (code "41") (name "Net-(IC2--IN)") (class "Default")
      (node (ref "C16") (pin "2") (pinfunction "2_2") (pintype "passive"))
      (node (ref "IC2") (pin "2") (pinfunction "-IN_2") (pintype "input"))
      (node (ref "R44") (pin "2") (pinfunction "2_2") (pintype "passive"))
    )
    (net (code "42") (name "Net-(IC2-OUT)") (class "Default")
      (node (ref "C16") (pin "1") (pinfunction "1_1") (pintype "passive"))
      (node (ref "IC2") (pin "6") (pinfunction "OUT_6") (pintype "output"))
      (node (ref "R36") (pin "1") (pinfunction "1_1") (pintype "passive"))
    )
    (net (code "43") (name "Net-(IC3-+IN)") (class "Default")
      (node (ref "C22") (pin "2") (pinfunction "2_2") (pintype "passive"))
      (node (ref "IC3") (pin "3") (pinfunction "+IN_3") (pintype "input"))
      (node (ref "R82") (pin "2") (pinfunction "2_2") (pintype "passive"))
    )
    (net (code "44") (name "Net-(IC3--IN)") (class "Default")
      (node (ref "C21") (pin "2") (pinfunction "2_2") (pintype "passive"))
      (node (ref "IC3") (pin "2") (pinfunction "-IN_2") (pintype "input"))
      (node (ref "R79") (pin "2") (pinfunction "2_2") (pintype "passive"))
    )
    (net (code "45") (name "Net-(IC3-OUT)") (class "Default")
      (node (ref "C21") (pin "1") (pinfunction "1_1") (pintype "passive"))
      (node (ref "IC3") (pin "6") (pinfunction "OUT_6") (pintype "output"))
      (node (ref "R68") (pin "1") (pinfunction "1_1") (pintype "passive"))
      (node (ref "R69") (pin "2") (pinfunction "2_2") (pintype "passive"))
    )
    (net (code "46") (name "Net-(IC4-+IN)") (class "Default")
      (node (ref "C32") (pin "2") (pinfunction "2_2") (pintype "passive"))
      (node (ref "IC4") (pin "3") (pinfunction "+IN_3") (pintype "input"))
      (node (ref "R114") (pin "2") (pinfunction "2_2") (pintype "passive"))
    )
    (net (code "47") (name "Net-(IC4--IN)") (class "Default")
      (node (ref "C31") (pin "2") (pinfunction "2_2") (pintype "passive"))
      (node (ref "IC4") (pin "2") (pinfunction "-IN_2") (pintype "input"))
      (node (ref "R111") (pin "2") (pinfunction "2_2") (pintype "passive"))
    )
    (net (code "48") (name "Net-(IC4-OUT)") (class "Default")
      (node (ref "C31") (pin "1") (pinfunction "1_1") (pintype "passive"))
      (node (ref "IC4") (pin "6") (pinfunction "OUT_6") (pintype "output"))
      (node (ref "R100") (pin "1") (pinfunction "1_1") (pintype "passive"))
      (node (ref "R101") (pin "2") (pinfunction "2_2") (pintype "passive"))
    )
    (net (code "49") (name "Net-(IC5--IN)") (class "Default")
      (node (ref "C52") (pin "2") (pinfunction "2_2") (pintype "passive"))
      (node (ref "C54") (pin "1") (pinfunction "1_1") (pintype "passive"))
      (node (ref "IC5") (pin "2") (pinfunction "-IN_2") (pintype "input"))
      (node (ref "R129") (pin "1") (pinfunction "1_1") (pintype "passive"))
      (node (ref "R130") (pin "2") (pinfunction "2_2") (pintype "passive"))
    )
    (net (code "50") (name "Net-(IC5-OUT)") (class "Default")
      (node (ref "C52") (pin "1") (pinfunction "1_1") (pintype "passive"))
      (node (ref "IC5") (pin "6") (pinfunction "OUT_6") (pintype "output"))
      (node (ref "R124") (pin "1") (pinfunction "1_1") (pintype "passive"))
    )
    (net (code "51") (name "Net-(IC6--IN)") (class "Default")
      (node (ref "C51") (pin "2") (pinfunction "2_2") (pintype "passive"))
      (node (ref "C53") (pin "2") (pinfunction "2_2") (pintype "passive"))
      (node (ref "IC6") (pin "2") (pinfunction "-IN_2") (pintype "input"))
      (node (ref "R127") (pin "1") (pinfunction "1_1") (pintype "passive"))
      (node (ref "R128") (pin "2") (pinfunction "2_2") (pintype "passive"))
    )
    (net (code "52") (name "Net-(IC6-OUT)") (class "Default")
      (node (ref "C51") (pin "1") (pinfunction "1_1") (pintype "passive"))
      (node (ref "IC6") (pin "6") (pinfunction "OUT_6") (pintype "output"))
      (node (ref "R123") (pin "1") (pinfunction "1_1") (pintype "passive"))
    )
    (net (code "53") (name "Net-(LED1-PadC)") (class "Default")
      (node (ref "LED1") (pin "C") (pinfunction "C_C") (pintype "passive"))
      (node (ref "Q2") (pin "B") (pinfunction "B_B") (pintype "passive"))
      (node (ref "R3") (pin "2") (pinfunction "2_2") (pintype "passive"))
    )
    (net (code "54") (name "Net-(LED2-PadA)") (class "Default")
      (node (ref "LED2") (pin "A") (pinfunction "A_A") (pintype "passive"))
      (node (ref "Q3") (pin "B") (pinfunction "B_B") (pintype "passive"))
      (node (ref "R4") (pin "1") (pinfunction "1_1") (pintype "passive"))
    )
    (net (code "55") (name "Net-(LED5-PadC)") (class "Default")
      (node (ref "LED5") (pin "C") (pinfunction "C_C") (pintype "passive"))
      (node (ref "Q11") (pin "B") (pinfunction "B_B") (pintype "passive"))
      (node (ref "R22") (pin "2") (pinfunction "2_2") (pintype "passive"))
    )
    (net (code "56") (name "Net-(LED6-PadA)") (class "Default")
      (node (ref "LED6") (pin "A") (pinfunction "A_A") (pintype "passive"))
      (node (ref "Q12") (pin "B") (pinfunction "B_B") (pintype "passive"))
      (node (ref "R22") (pin "1") (pinfunction "1_1") (pintype "passive"))
    )
    (net (code "57") (name "Net-(LED7-PadC)") (class "Default")
      (node (ref "LED7") (pin "C") (pinfunction "C_C") (pintype "passive"))
      (node (ref "Q19") (pin "B") (pinfunction "B_B") (pintype "passive"))
      (node (ref "R37") (pin "2") (pinfunction "2_2") (pintype "passive"))
    )
    (net (code "58") (name "Net-(LED8-PadA)") (class "Default")
      (node (ref "LED8") (pin "A") (pinfunction "A_A") (pintype "passive"))
      (node (ref "Q20") (pin "B") (pinfunction "B_B") (pintype "passive"))
      (node (ref "R37") (pin "1") (pinfunction "1_1") (pintype "passive"))
    )
    (net (code "59") (name "Net-(LED9-PadA)") (class "Default")
      (node (ref "LED9") (pin "A") (pinfunction "A_A") (pintype "passive"))
      (node (ref "Q35") (pin "E") (pinfunction "E_E") (pintype "passive"))
      (node (ref "R62") (pin "1") (pinfunction "1_1") (pintype "passive"))
    )
    (net (code "60") (name "Net-(LED9-PadC)") (class "Default")
      (node (ref "LED9") (pin "C") (pinfunction "C_C") (pintype "passive"))
      (node (ref "Q39") (pin "B") (pinfunction "B_B") (pintype "passive"))
      (node (ref "R65") (pin "2") (pinfunction "2_2") (pintype "passive"))
    )
    (net (code "61") (name "Net-(LED10-PadA)") (class "Default")
      (node (ref "LED10") (pin "A") (pinfunction "A_A") (pintype "passive"))
      (node (ref "Q40") (pin "B") (pinfunction "B_B") (pintype "passive"))
      (node (ref "R65") (pin "1") (pinfunction "1_1") (pintype "passive"))
    )
    (net (code "62") (name "Net-(LED10-PadC)") (class "Default")
      (node (ref "LED10") (pin "C") (pinfunction "C_C") (pintype "passive"))
      (node (ref "Q38") (pin "E") (pinfunction "E_E") (pintype "passive"))
      (node (ref "R64") (pin "2") (pinfunction "2_2") (pintype "passive"))
    )
    (net (code "63") (name "Net-(LED11-PadA)") (class "Default")
      (node (ref "LED11") (pin "A") (pinfunction "A_A") (pintype "passive"))
      (node (ref "Q62") (pin "E") (pinfunction "E_E") (pintype "passive"))
      (node (ref "R94") (pin "1") (pinfunction "1_1") (pintype "passive"))
    )
    (net (code "64") (name "Net-(LED11-PadC)") (class "Default")
      (node (ref "LED11") (pin "C") (pinfunction "C_C") (pintype "passive"))
      (node (ref "Q66") (pin "B") (pinfunction "B_B") (pintype "passive"))
      (node (ref "R97") (pin "2") (pinfunction "2_2") (pintype "passive"))
    )
    (net (code "65") (name "Net-(LED12-PadA)") (class "Default")
      (node (ref "LED12") (pin "A") (pinfunction "A_A") (pintype "passive"))
      (node (ref "Q67") (pin "B") (pinfunction "B_B") (pintype "passive"))
      (node (ref "R97") (pin "1") (pinfunction "1_1") (pintype "passive"))
    )
    (net (code "66") (name "Net-(LED12-PadC)") (class "Default")
      (node (ref "LED12") (pin "C") (pinfunction "C_C") (pintype "passive"))
      (node (ref "Q65") (pin "E") (pinfunction "E_E") (pintype "passive"))
      (node (ref "R96") (pin "2") (pinfunction "2_2") (pintype "passive"))
    )
    (net (code "67") (name "Net-(LED13-PadA)") (class "Default")
      (node (ref "LED13") (pin "A") (pinfunction "A_A") (pintype "passive"))
      (node (ref "Q79") (pin "B") (pinfunction "B_B") (pintype "passive"))
      (node (ref "R115") (pin "2") (pinfunction "2_2") (pintype "passive"))
    )
    (net (code "68") (name "Net-(LED14-PadC)") (class "Default")
      (node (ref "LED14") (pin "C") (pinfunction "C_C") (pintype "passive"))
      (node (ref "Q80") (pin "B") (pinfunction "B_B") (pintype "passive"))
      (node (ref "R116") (pin "1") (pinfunction "1_1") (pintype "passive"))
    )
    (net (code "69") (name "Net-(LED15-PadC)") (class "Default")
      (node (ref "LED15") (pin "C") (pinfunction "C_C") (pintype "passive"))
      (node (ref "Q81") (pin "E") (pinfunction "E_E") (pintype "passive"))
    )
    (net (code "70") (name "Net-(LED16-PadA)") (class "Default")
      (node (ref "LED16") (pin "A") (pinfunction "A_A") (pintype "passive"))
      (node (ref "Q82") (pin "E") (pinfunction "E_E") (pintype "passive"))
    )
    (net (code "71") (name "Net-(LED17-PadA)") (class "Default")
      (node (ref "LED17") (pin "A") (pinfunction "A_A") (pintype "passive"))
      (node (ref "R131") (pin "1") (pinfunction "1_1") (pintype "passive"))
    )
    (net (code "72") (name "Net-(LED18-PadC)") (class "Default")
      (node (ref "LED18") (pin "C") (pinfunction "C_C") (pintype "passive"))
      (node (ref "R132") (pin "2") (pinfunction "2_2") (pintype "passive"))
    )
    (net (code "73") (name "Net-(Q1A-D)") (class "Default")
      (node (ref "Q1") (pin "2") (pinfunction "D_2") (pintype "passive"))
      (node (ref "Q6") (pin "5") (pinfunction "E_5") (pintype "passive"))
      (node (ref "Q7") (pin "6") (pinfunction "C_6") (pintype "passive"))
    )
    (net (code "74") (name "Net-(Q1A-S)") (class "Default")
      (node (ref "Q1") (pin "3") (pinfunction "S_3") (pintype "passive"))
      (node (ref "R6") (pin "1") (pinfunction "1_1") (pintype "passive"))
    )
    (net (code "75") (name "Net-(Q1B-D)") (class "Default")
      (node (ref "Q1") (pin "5") (pinfunction "D_5") (pintype "passive"))
      (node (ref "Q6") (pin "2") (pinfunction "E_2") (pintype "passive"))
      (node (ref "Q7") (pin "4") (pinfunction "C_4") (pintype "passive"))
    )
    (net (code "76") (name "Net-(Q1B-S)") (class "Default")
      (node (ref "Q1") (pin "6") (pinfunction "S_6") (pintype "passive"))
      (node (ref "R8") (pin "1") (pinfunction "1_1") (pintype "passive"))
    )
    (net (code "77") (name "Net-(Q2-PadC)") (class "Default")
      (node (ref "Q2") (pin "C") (pinfunction "C_C") (pintype "passive"))
      (node (ref "R6") (pin "2") (pinfunction "2_2") (pintype "passive"))
      (node (ref "R8") (pin "2") (pinfunction "2_2") (pintype "passive"))
    )
    (net (code "78") (name "Net-(Q2-PadE)") (class "Default")
      (node (ref "Q2") (pin "E") (pinfunction "E_E") (pintype "passive"))
      (node (ref "R5") (pin "1") (pinfunction "1_1") (pintype "passive"))
    )
    (net (code "79") (name "Net-(Q3-PadC)") (class "Default")
      (node (ref "Q3") (pin "C") (pinfunction "C_C") (pintype "passive"))
      (node (ref "R10") (pin "1") (pinfunction "1_1") (pintype "passive"))
      (node (ref "R9") (pin "1") (pinfunction "1_1") (pintype "passive"))
    )
    (net (code "80") (name "Net-(Q3-PadE)") (class "Default")
      (node (ref "Q3") (pin "E") (pinfunction "E_E") (pintype "passive"))
      (node (ref "R7") (pin "2") (pinfunction "2_2") (pintype "passive"))
    )
    (net (code "81") (name "Net-(Q4A-D)") (class "Default")
      (node (ref "Q4") (pin "2") (pinfunction "D_2") (pintype "passive"))
      (node (ref "Q5") (pin "5") (pinfunction "E_5") (pintype "passive"))
      (node (ref "Q8") (pin "4") (pinfunction "C_4") (pintype "passive"))
    )
    (net (code "82") (name "Net-(Q4A-S)") (class "Default")
      (node (ref "Q4") (pin "3") (pinfunction "S_3") (pintype "passive"))
      (node (ref "R9") (pin "2") (pinfunction "2_2") (pintype "passive"))
    )
    (net (code "83") (name "Net-(Q4B-D)") (class "Default")
      (node (ref "Q4") (pin "5") (pinfunction "D_5") (pintype "passive"))
      (node (ref "Q5") (pin "2") (pinfunction "E_2") (pintype "passive"))
      (node (ref "Q8") (pin "6") (pinfunction "C_6") (pintype "passive"))
    )
    (net (code "84") (name "Net-(Q4B-S)") (class "Default")
      (node (ref "Q4") (pin "6") (pinfunction "S_6") (pintype "passive"))
      (node (ref "R10") (pin "2") (pinfunction "2_2") (pintype "passive"))
    )
    (net (code "85") (name "Net-(Q5A-B)") (class "Default")
      (node (ref "Q5") (pin "1") (pinfunction "B_1") (pintype "passive"))
      (node (ref "Q5") (pin "3") (pinfunction "B_3") (pintype "passive"))
      (node (ref "R14") (pin "1") (pinfunction "1_1") (pintype "passive"))
      (node (ref "R15") (pin "2") (pinfunction "2_2") (pintype "passive"))
    )
    (net (code "86") (name "Net-(Q6A-B)") (class "Default")
      (node (ref "Q6") (pin "1") (pinfunction "B_1") (pintype "passive"))
      (node (ref "Q6") (pin "3") (pinfunction "B_3") (pintype "passive"))
      (node (ref "R16") (pin "1") (pinfunction "1_1") (pintype "passive"))
      (node (ref "R17") (pin "2") (pinfunction "2_2") (pintype "passive"))
    )
    (net (code "87") (name "Net-(Q7A-B)") (class "Default")
      (node (ref "LED4") (pin "A") (pinfunction "A_A") (pintype "passive"))
      (node (ref "Q7") (pin "1") (pinfunction "B_1") (pintype "passive"))
      (node (ref "Q7") (pin "3") (pinfunction "B_3") (pintype "passive"))
      (node (ref "R17") (pin "1") (pinfunction "1_1") (pintype "passive"))
    )
    (net (code "88") (name "Net-(Q7A-E)") (class "Default")
      (node (ref "Q7") (pin "5") (pinfunction "E_5") (pintype "passive"))
      (node (ref "R13") (pin "2") (pinfunction "2_2") (pintype "passive"))
    )
    (net (code "89") (name "Net-(Q7B-E)") (class "Default")
      (node (ref "Q7") (pin "2") (pinfunction "E_2") (pintype "passive"))
      (node (ref "R19") (pin "2") (pinfunction "2_2") (pintype "passive"))
    )
    (net (code "90") (name "Net-(Q8A-B)") (class "Default")
      (node (ref "LED3") (pin "C") (pinfunction "C_C") (pintype "passive"))
      (node (ref "Q8") (pin "1") (pinfunction "B_1") (pintype "passive"))
      (node (ref "Q8") (pin "3") (pinfunction "B_3") (pintype "passive"))
      (node (ref "R14") (pin "2") (pinfunction "2_2") (pintype "passive"))
    )
    (net (code "91") (name "Net-(Q8A-E)") (class "Default")
      (node (ref "Q8") (pin "5") (pinfunction "E_5") (pintype "passive"))
      (node (ref "R18") (pin "1") (pinfunction "1_1") (pintype "passive"))
    )
    (net (code "92") (name "Net-(Q8B-E)") (class "Default")
      (node (ref "Q8") (pin "2") (pinfunction "E_2") (pintype "passive"))
      (node (ref "R12") (pin "1") (pinfunction "1_1") (pintype "passive"))
    )
    (net (code "93") (name "Net-(Q9-PadE)") (class "Default")
      (node (ref "Q9") (pin "E") (pinfunction "E_E") (pintype "passive"))
      (node (ref "R25") (pin "1") (pinfunction "1_1") (pintype "passive"))
    )
    (net (code "94") (name "Net-(Q10-PadE)") (class "Default")
      (node (ref "Q10") (pin "E") (pinfunction "E_E") (pintype "passive"))
      (node (ref "R24") (pin "2") (pinfunction "2_2") (pintype "passive"))
    )
    (net (code "95") (name "Net-(Q11-PadC)") (class "Default")
      (node (ref "Q11") (pin "C") (pinfunction "C_C") (pintype "passive"))
      (node (ref "R24") (pin "1") (pinfunction "1_1") (pintype "passive"))
      (node (ref "R27") (pin "2") (pinfunction "2_2") (pintype "passive"))
      (node (ref "R32") (pin "2") (pinfunction "2_2") (pintype "passive"))
    )
    (net (code "96") (name "Net-(Q11-PadE)") (class "Default")
      (node (ref "Q11") (pin "E") (pinfunction "E_E") (pintype "passive"))
      (node (ref "R23") (pin "1") (pinfunction "1_1") (pintype "passive"))
    )
    (net (code "97") (name "Net-(Q12-PadC)") (class "Default")
      (node (ref "Q12") (pin "C") (pinfunction "C_C") (pintype "passive"))
      (node (ref "R25") (pin "2") (pinfunction "2_2") (pintype "passive"))
      (node (ref "R28") (pin "1") (pinfunction "1_1") (pintype "passive"))
      (node (ref "R33") (pin "1") (pinfunction "1_1") (pintype "passive"))
    )
    (net (code "98") (name "Net-(Q12-PadE)") (class "Default")
      (node (ref "Q12") (pin "E") (pinfunction "E_E") (pintype "passive"))
      (node (ref "R26") (pin "2") (pinfunction "2_2") (pintype "passive"))
    )
    (net (code "99") (name "Net-(Q13-PadB)") (class "Default")
      (node (ref "Q13") (pin "B") (pinfunction "B_B") (pintype "passive"))
      (node (ref "R27") (pin "1") (pinfunction "1_1") (pintype "passive"))
    )
    (net (code "100") (name "Net-(Q13-PadE)") (class "Default")
      (node (ref "Q13") (pin "E") (pinfunction "E_E") (pintype "passive"))
      (node (ref "R30") (pin "2") (pinfunction "2_2") (pintype "passive"))
    )
    (net (code "101") (name "Net-(Q14-PadB)") (class "Default")
      (node (ref "Q14") (pin "B") (pinfunction "B_B") (pintype "passive"))
      (node (ref "R28") (pin "2") (pinfunction "2_2") (pintype "passive"))
    )
    (net (code "102") (name "Net-(Q14-PadE)") (class "Default")
      (node (ref "Q14") (pin "E") (pinfunction "E_E") (pintype "passive"))
      (node (ref "R31") (pin "1") (pinfunction "1_1") (pintype "passive"))
    )
    (net (code "103") (name "Net-(Q15-PadB)") (class "Default")
      (node (ref "Q15") (pin "B") (pinfunction "B_B") (pintype "passive"))
      (node (ref "R32") (pin "1") (pinfunction "1_1") (pintype "passive"))
    )
    (net (code "104") (name "Net-(Q15-PadE)") (class "Default")
      (node (ref "Q15") (pin "E") (pinfunction "E_E") (pintype "passive"))
      (node (ref "R34") (pin "2") (pinfunction "2_2") (pintype "passive"))
    )
    (net (code "105") (name "Net-(Q16-PadB)") (class "Default")
      (node (ref "Q16") (pin "B") (pinfunction "B_B") (pintype "passive"))
      (node (ref "R33") (pin "2") (pinfunction "2_2") (pintype "passive"))
    )
    (net (code "106") (name "Net-(Q16-PadE)") (class "Default")
      (node (ref "Q16") (pin "E") (pinfunction "E_E") (pintype "passive"))
      (node (ref "R35") (pin "1") (pinfunction "1_1") (pintype "passive"))
    )
    (net (code "107") (name "Net-(Q17-PadE)") (class "Default")
      (node (ref "Q17") (pin "E") (pinfunction "E_E") (pintype "passive"))
      (node (ref "R40") (pin "1") (pinfunction "1_1") (pintype "passive"))
    )
    (net (code "108") (name "Net-(Q18-PadE)") (class "Default")
      (node (ref "Q18") (pin "E") (pinfunction "E_E") (pintype "passive"))
      (node (ref "R39") (pin "2") (pinfunction "2_2") (pintype "passive"))
    )
    (net (code "109") (name "Net-(Q19-PadC)") (class "Default")
      (node (ref "Q19") (pin "C") (pinfunction "C_C") (pintype "passive"))
      (node (ref "R39") (pin "1") (pinfunction "1_1") (pintype "passive"))
      (node (ref "R42") (pin "2") (pinfunction "2_2") (pintype "passive"))
      (node (ref "R47") (pin "2") (pinfunction "2_2") (pintype "passive"))
    )
    (net (code "110") (name "Net-(Q19-PadE)") (class "Default")
      (node (ref "Q19") (pin "E") (pinfunction "E_E") (pintype "passive"))
      (node (ref "R38") (pin "1") (pinfunction "1_1") (pintype "passive"))
    )
    (net (code "111") (name "Net-(Q20-PadC)") (class "Default")
      (node (ref "Q20") (pin "C") (pinfunction "C_C") (pintype "passive"))
      (node (ref "R40") (pin "2") (pinfunction "2_2") (pintype "passive"))
      (node (ref "R43") (pin "1") (pinfunction "1_1") (pintype "passive"))
      (node (ref "R48") (pin "1") (pinfunction "1_1") (pintype "passive"))
    )
    (net (code "112") (name "Net-(Q20-PadE)") (class "Default")
      (node (ref "Q20") (pin "E") (pinfunction "E_E") (pintype "passive"))
      (node (ref "R41") (pin "2") (pinfunction "2_2") (pintype "passive"))
    )
    (net (code "113") (name "Net-(Q21-PadB)") (class "Default")
      (node (ref "Q21") (pin "B") (pinfunction "B_B") (pintype "passive"))
      (node (ref "R42") (pin "1") (pinfunction "1_1") (pintype "passive"))
    )
    (net (code "114") (name "Net-(Q21-PadE)") (class "Default")
      (node (ref "Q21") (pin "E") (pinfunction "E_E") (pintype "passive"))
      (node (ref "R45") (pin "2") (pinfunction "2_2") (pintype "passive"))
    )
    (net (code "115") (name "Net-(Q22-PadB)") (class "Default")
      (node (ref "Q22") (pin "B") (pinfunction "B_B") (pintype "passive"))
      (node (ref "R43") (pin "2") (pinfunction "2_2") (pintype "passive"))
    )
    (net (code "116") (name "Net-(Q22-PadE)") (class "Default")
      (node (ref "Q22") (pin "E") (pinfunction "E_E") (pintype "passive"))
      (node (ref "R46") (pin "1") (pinfunction "1_1") (pintype "passive"))
    )
    (net (code "117") (name "Net-(Q23-PadB)") (class "Default")
      (node (ref "Q23") (pin "B") (pinfunction "B_B") (pintype "passive"))
      (node (ref "R47") (pin "1") (pinfunction "1_1") (pintype "passive"))
    )
    (net (code "118") (name "Net-(Q23-PadE)") (class "Default")
      (node (ref "Q23") (pin "E") (pinfunction "E_E") (pintype "passive"))
      (node (ref "R49") (pin "2") (pinfunction "2_2") (pintype "passive"))
    )
    (net (code "119") (name "Net-(Q24-PadB)") (class "Default")
      (node (ref "Q24") (pin "B") (pinfunction "B_B") (pintype "passive"))
      (node (ref "R48") (pin "2") (pinfunction "2_2") (pintype "passive"))
    )
    (net (code "120") (name "Net-(Q24-PadE)") (class "Default")
      (node (ref "Q24") (pin "E") (pinfunction "E_E") (pintype "passive"))
      (node (ref "R50") (pin "1") (pinfunction "1_1") (pintype "passive"))
    )
    (net (code "121") (name "Net-(Q25-PadE)") (class "Default")
      (node (ref "Q25") (pin "E") (pinfunction "E_E") (pintype "passive"))
      (node (ref "R54") (pin "1") (pinfunction "1_1") (pintype "passive"))
    )
    (net (code "122") (name "Net-(Q26-PadC)") (class "Default")
      (node (ref "Q26") (pin "C") (pinfunction "C_C") (pintype "passive"))
      (node (ref "Q31") (pin "E") (pinfunction "E_E") (pintype "passive"))
      (node (ref "R60") (pin "1") (pinfunction "1_1") (pintype "passive"))
    )
    (net (code "123") (name "Net-(Q26-PadE)") (class "Default")
      (node (ref "Q26") (pin "E") (pinfunction "E_E") (pintype "passive"))
      (node (ref "R55") (pin "1") (pinfunction "1_1") (pintype "passive"))
    )
    (net (code "124") (name "Net-(Q27-PadC)") (class "Default")
      (node (ref "Q27") (pin "C") (pinfunction "C_C") (pintype "passive"))
      (node (ref "Q30") (pin "E") (pinfunction "E_E") (pintype "passive"))
      (node (ref "R59") (pin "2") (pinfunction "2_2") (pintype "passive"))
    )
    (net (code "125") (name "Net-(Q27-PadE)") (class "Default")
      (node (ref "Q27") (pin "E") (pinfunction "E_E") (pintype "passive"))
      (node (ref "R56") (pin "2") (pinfunction "2_2") (pintype "passive"))
    )
    (net (code "126") (name "Net-(Q28-PadE)") (class "Default")
      (node (ref "Q28") (pin "E") (pinfunction "E_E") (pintype "passive"))
      (node (ref "R57") (pin "2") (pinfunction "2_2") (pintype "passive"))
    )
    (net (code "127") (name "Net-(Q29-PadC)") (class "Default")
      (node (ref "Q29") (pin "C") (pinfunction "C_C") (pintype "passive"))
      (node (ref "Q33") (pin "C") (pinfunction "C_C") (pintype "passive"))
      (node (ref "Q36") (pin "B") (pinfunction "B_B") (pintype "passive"))
    )
    (net (code "128") (name "Net-(Q29-PadE)") (class "Default")
      (node (ref "Q29") (pin "E") (pinfunction "E_E") (pintype "passive"))
      (node (ref "Q30") (pin "C") (pinfunction "C_C") (pintype "passive"))
    )
    (net (code "129") (name "Net-(Q31-PadC)") (class "Default")
      (node (ref "Q31") (pin "C") (pinfunction "C_C") (pintype "passive"))
      (node (ref "Q32") (pin "E") (pinfunction "E_E") (pintype "passive"))
    )
    (net (code "130") (name "Net-(Q32-PadC)") (class "Default")
      (node (ref "Q32") (pin "C") (pinfunction "C_C") (pintype "passive"))
      (node (ref "Q34") (pin "C") (pinfunction "C_C") (pintype "passive"))
      (node (ref "Q37") (pin "B") (pinfunction "B_B") (pintype "passive"))
    )
    (net (code "131") (name "Net-(Q33-PadB)") (class "Default")
      (node (ref "Q33") (pin "B") (pinfunction "B_B") (pintype "passive"))
      (node (ref "Q35") (pin "B") (pinfunction "B_B") (pintype "passive"))
      (node (ref "Q35") (pin "C") (pinfunction "C_C") (pintype "passive"))
      (node (ref "Q36") (pin "E") (pinfunction "E_E") (pintype "passive"))
    )
    (net (code "132") (name "Net-(Q33-PadE)") (class "Default")
      (node (ref "Q33") (pin "E") (pinfunction "E_E") (pintype "passive"))
      (node (ref "R58") (pin "1") (pinfunction "1_1") (pintype "passive"))
    )
    (net (code "133") (name "Net-(Q34-PadB)") (class "Default")
      (node (ref "Q34") (pin "B") (pinfunction "B_B") (pintype "passive"))
      (node (ref "Q37") (pin "E") (pinfunction "E_E") (pintype "passive"))
      (node (ref "Q38") (pin "B") (pinfunction "B_B") (pintype "passive"))
      (node (ref "Q38") (pin "C") (pinfunction "C_C") (pintype "passive"))
    )
    (net (code "134") (name "Net-(Q34-PadE)") (class "Default")
      (node (ref "Q34") (pin "E") (pinfunction "E_E") (pintype "passive"))
      (node (ref "R61") (pin "2") (pinfunction "2_2") (pintype "passive"))
    )
    (net (code "135") (name "Net-(Q36-PadC)") (class "Default")
      (node (ref "Q36") (pin "C") (pinfunction "C_C") (pintype "passive"))
      (node (ref "Q39") (pin "E") (pinfunction "E_E") (pintype "passive"))
    )
    (net (code "136") (name "Net-(Q37-PadC)") (class "Default")
      (node (ref "Q37") (pin "C") (pinfunction "C_C") (pintype "passive"))
      (node (ref "Q40") (pin "E") (pinfunction "E_E") (pintype "passive"))
    )
    (net (code "137") (name "Net-(Q41-PadB)") (class "Default")
      (node (ref "Q41") (pin "B") (pinfunction "B_B") (pintype "passive"))
      (node (ref "Q41") (pin "C") (pinfunction "C_C") (pintype "passive"))
      (node (ref "Q43") (pin "B") (pinfunction "B_B") (pintype "passive"))
      (node (ref "R68") (pin "2") (pinfunction "2_2") (pintype "passive"))
    )
    (net (code "138") (name "Net-(Q41-PadE)") (class "Default")
      (node (ref "Q41") (pin "E") (pinfunction "E_E") (pintype "passive"))
      (node (ref "R67") (pin "1") (pinfunction "1_1") (pintype "passive"))
    )
    (net (code "139") (name "Net-(Q42-PadB)") (class "Default")
      (node (ref "Q42") (pin "B") (pinfunction "B_B") (pintype "passive"))
      (node (ref "Q42") (pin "C") (pinfunction "C_C") (pintype "passive"))
      (node (ref "Q44") (pin "B") (pinfunction "B_B") (pintype "passive"))
      (node (ref "R69") (pin "1") (pinfunction "1_1") (pintype "passive"))
    )
    (net (code "140") (name "Net-(Q42-PadE)") (class "Default")
      (node (ref "Q42") (pin "E") (pinfunction "E_E") (pintype "passive"))
      (node (ref "R70") (pin "2") (pinfunction "2_2") (pintype "passive"))
    )
    (net (code "141") (name "Net-(Q43-PadE)") (class "Default")
      (node (ref "Q43") (pin "E") (pinfunction "E_E") (pintype "passive"))
      (node (ref "R71") (pin "1") (pinfunction "1_1") (pintype "passive"))
    )
    (net (code "142") (name "Net-(Q44-PadE)") (class "Default")
      (node (ref "Q44") (pin "E") (pinfunction "E_E") (pintype "passive"))
      (node (ref "R72") (pin "2") (pinfunction "2_2") (pintype "passive"))
    )
    (net (code "143") (name "Net-(Q46-PadE)") (class "Default")
      (node (ref "Q46") (pin "E") (pinfunction "E_E") (pintype "passive"))
      (node (ref "Q48") (pin "B") (pinfunction "B_B") (pintype "passive"))
      (node (ref "R77") (pin "2") (pinfunction "2_2") (pintype "passive"))
    )
    (net (code "144") (name "Net-(Q47-PadE)") (class "Default")
      (node (ref "Q47") (pin "E") (pinfunction "E_E") (pintype "passive"))
      (node (ref "Q49") (pin "B") (pinfunction "B_B") (pintype "passive"))
      (node (ref "R77") (pin "1") (pinfunction "1_1") (pintype "passive"))
    )
    (net (code "145") (name "Net-(Q48-PadE)") (class "Default")
      (node (ref "Q48") (pin "E") (pinfunction "E_E") (pintype "passive"))
      (node (ref "Q50") (pin "B") (pinfunction "B_B") (pintype "passive"))
      (node (ref "R78") (pin "2") (pinfunction "2_2") (pintype "passive"))
    )
    (net (code "146") (name "Net-(Q49-PadE)") (class "Default")
      (node (ref "Q49") (pin "E") (pinfunction "E_E") (pintype "passive"))
      (node (ref "Q51") (pin "B") (pinfunction "B_B") (pintype "passive"))
      (node (ref "R78") (pin "1") (pinfunction "1_1") (pintype "passive"))
    )
    (net (code "147") (name "Net-(Q50-PadE)") (class "Default")
      (node (ref "Q50") (pin "E") (pinfunction "E_E") (pintype "passive"))
      (node (ref "R80") (pin "2") (pinfunction "2_2") (pintype "passive"))
    )
    (net (code "148") (name "Net-(Q51-PadE)") (class "Default")
      (node (ref "Q51") (pin "E") (pinfunction "E_E") (pintype "passive"))
      (node (ref "R81") (pin "1") (pinfunction "1_1") (pintype "passive"))
    )
    (net (code "149") (name "Net-(Q52-PadE)") (class "Default")
      (node (ref "Q52") (pin "E") (pinfunction "E_E") (pintype "passive"))
      (node (ref "R86") (pin "1") (pinfunction "1_1") (pintype "passive"))
    )
    (net (code "150") (name "Net-(Q53-PadC)") (class "Default")
      (node (ref "Q53") (pin "C") (pinfunction "C_C") (pintype "passive"))
      (node (ref "Q58") (pin "E") (pinfunction "E_E") (pintype "passive"))
      (node (ref "R92") (pin "1") (pinfunction "1_1") (pintype "passive"))
    )
    (net (code "151") (name "Net-(Q53-PadE)") (class "Default")
      (node (ref "Q53") (pin "E") (pinfunction "E_E") (pintype "passive"))
      (node (ref "R87") (pin "1") (pinfunction "1_1") (pintype "passive"))
    )
    (net (code "152") (name "Net-(Q54-PadC)") (class "Default")
      (node (ref "Q54") (pin "C") (pinfunction "C_C") (pintype "passive"))
      (node (ref "Q57") (pin "E") (pinfunction "E_E") (pintype "passive"))
      (node (ref "R91") (pin "2") (pinfunction "2_2") (pintype "passive"))
    )
    (net (code "153") (name "Net-(Q54-PadE)") (class "Default")
      (node (ref "Q54") (pin "E") (pinfunction "E_E") (pintype "passive"))
      (node (ref "R88") (pin "2") (pinfunction "2_2") (pintype "passive"))
    )
    (net (code "154") (name "Net-(Q55-PadE)") (class "Default")
      (node (ref "Q55") (pin "E") (pinfunction "E_E") (pintype "passive"))
      (node (ref "R89") (pin "2") (pinfunction "2_2") (pintype "passive"))
    )
    (net (code "155") (name "Net-(Q56-PadC)") (class "Default")
      (node (ref "Q56") (pin "C") (pinfunction "C_C") (pintype "passive"))
      (node (ref "Q60") (pin "C") (pinfunction "C_C") (pintype "passive"))
      (node (ref "Q63") (pin "B") (pinfunction "B_B") (pintype "passive"))
    )
    (net (code "156") (name "Net-(Q56-PadE)") (class "Default")
      (node (ref "Q56") (pin "E") (pinfunction "E_E") (pintype "passive"))
      (node (ref "Q57") (pin "C") (pinfunction "C_C") (pintype "passive"))
    )
    (net (code "157") (name "Net-(Q58-PadC)") (class "Default")
      (node (ref "Q58") (pin "C") (pinfunction "C_C") (pintype "passive"))
      (node (ref "Q59") (pin "E") (pinfunction "E_E") (pintype "passive"))
    )
    (net (code "158") (name "Net-(Q59-PadC)") (class "Default")
      (node (ref "Q59") (pin "C") (pinfunction "C_C") (pintype "passive"))
      (node (ref "Q61") (pin "C") (pinfunction "C_C") (pintype "passive"))
      (node (ref "Q64") (pin "B") (pinfunction "B_B") (pintype "passive"))
    )
    (net (code "159") (name "Net-(Q60-PadB)") (class "Default")
      (node (ref "Q60") (pin "B") (pinfunction "B_B") (pintype "passive"))
      (node (ref "Q62") (pin "B") (pinfunction "B_B") (pintype "passive"))
      (node (ref "Q62") (pin "C") (pinfunction "C_C") (pintype "passive"))
      (node (ref "Q63") (pin "E") (pinfunction "E_E") (pintype "passive"))
    )
    (net (code "160") (name "Net-(Q60-PadE)") (class "Default")
      (node (ref "Q60") (pin "E") (pinfunction "E_E") (pintype "passive"))
      (node (ref "R90") (pin "1") (pinfunction "1_1") (pintype "passive"))
    )
    (net (code "161") (name "Net-(Q61-PadB)") (class "Default")
      (node (ref "Q61") (pin "B") (pinfunction "B_B") (pintype "passive"))
      (node (ref "Q64") (pin "E") (pinfunction "E_E") (pintype "passive"))
      (node (ref "Q65") (pin "B") (pinfunction "B_B") (pintype "passive"))
      (node (ref "Q65") (pin "C") (pinfunction "C_C") (pintype "passive"))
    )
    (net (code "162") (name "Net-(Q61-PadE)") (class "Default")
      (node (ref "Q61") (pin "E") (pinfunction "E_E") (pintype "passive"))
      (node (ref "R93") (pin "2") (pinfunction "2_2") (pintype "passive"))
    )
    (net (code "163") (name "Net-(Q63-PadC)") (class "Default")
      (node (ref "Q63") (pin "C") (pinfunction "C_C") (pintype "passive"))
      (node (ref "Q66") (pin "E") (pinfunction "E_E") (pintype "passive"))
    )
    (net (code "164") (name "Net-(Q64-PadC)") (class "Default")
      (node (ref "Q64") (pin "C") (pinfunction "C_C") (pintype "passive"))
      (node (ref "Q67") (pin "E") (pinfunction "E_E") (pintype "passive"))
    )
    (net (code "165") (name "Net-(Q68-PadB)") (class "Default")
      (node (ref "Q68") (pin "B") (pinfunction "B_B") (pintype "passive"))
      (node (ref "Q68") (pin "C") (pinfunction "C_C") (pintype "passive"))
      (node (ref "Q70") (pin "B") (pinfunction "B_B") (pintype "passive"))
      (node (ref "R100") (pin "2") (pinfunction "2_2") (pintype "passive"))
    )
    (net (code "166") (name "Net-(Q68-PadE)") (class "Default")
      (node (ref "Q68") (pin "E") (pinfunction "E_E") (pintype "passive"))
      (node (ref "R99") (pin "1") (pinfunction "1_1") (pintype "passive"))
    )
    (net (code "167") (name "Net-(Q69-PadB)") (class "Default")
      (node (ref "Q69") (pin "B") (pinfunction "B_B") (pintype "passive"))
      (node (ref "Q69") (pin "C") (pinfunction "C_C") (pintype "passive"))
      (node (ref "Q71") (pin "B") (pinfunction "B_B") (pintype "passive"))
      (node (ref "R101") (pin "1") (pinfunction "1_1") (pintype "passive"))
    )
    (net (code "168") (name "Net-(Q69-PadE)") (class "Default")
      (node (ref "Q69") (pin "E") (pinfunction "E_E") (pintype "passive"))
      (node (ref "R102") (pin "2") (pinfunction "2_2") (pintype "passive"))
    )
    (net (code "169") (name "Net-(Q70-PadE)") (class "Default")
      (node (ref "Q70") (pin "E") (pinfunction "E_E") (pintype "passive"))
      (node (ref "R103") (pin "1") (pinfunction "1_1") (pintype "passive"))
    )
    (net (code "170") (name "Net-(Q71-PadE)") (class "Default")
      (node (ref "Q71") (pin "E") (pinfunction "E_E") (pintype "passive"))
      (node (ref "R104") (pin "2") (pinfunction "2_2") (pintype "passive"))
    )
    (net (code "171") (name "Net-(Q73-PadE)") (class "Default")
      (node (ref "Q73") (pin "E") (pinfunction "E_E") (pintype "passive"))
      (node (ref "Q75") (pin "B") (pinfunction "B_B") (pintype "passive"))
      (node (ref "R109") (pin "2") (pinfunction "2_2") (pintype "passive"))
    )
    (net (code "172") (name "Net-(Q74-PadE)") (class "Default")
      (node (ref "Q74") (pin "E") (pinfunction "E_E") (pintype "passive"))
      (node (ref "Q76") (pin "B") (pinfunction "B_B") (pintype "passive"))
      (node (ref "R109") (pin "1") (pinfunction "1_1") (pintype "passive"))
    )
    (net (code "173") (name "Net-(Q75-PadE)") (class "Default")
      (node (ref "Q75") (pin "E") (pinfunction "E_E") (pintype "passive"))
      (node (ref "Q77") (pin "B") (pinfunction "B_B") (pintype "passive"))
      (node (ref "R110") (pin "2") (pinfunction "2_2") (pintype "passive"))
    )
    (net (code "174") (name "Net-(Q76-PadE)") (class "Default")
      (node (ref "Q76") (pin "E") (pinfunction "E_E") (pintype "passive"))
      (node (ref "Q78") (pin "B") (pinfunction "B_B") (pintype "passive"))
      (node (ref "R110") (pin "1") (pinfunction "1_1") (pintype "passive"))
    )
    (net (code "175") (name "Net-(Q77-PadE)") (class "Default")
      (node (ref "Q77") (pin "E") (pinfunction "E_E") (pintype "passive"))
      (node (ref "R112") (pin "2") (pinfunction "2_2") (pintype "passive"))
    )
    (net (code "176") (name "Net-(Q78-PadE)") (class "Default")
      (node (ref "Q78") (pin "E") (pinfunction "E_E") (pintype "passive"))
      (node (ref "R113") (pin "1") (pinfunction "1_1") (pintype "passive"))
    )
    (net (code "177") (name "Net-(Q79-PadC)") (class "Default")
      (node (ref "Q79") (pin "C") (pinfunction "C_C") (pintype "passive"))
      (node (ref "Q81") (pin "B") (pinfunction "B_B") (pintype "passive"))
      (node (ref "Q81") (pin "C") (pinfunction "C_C") (pintype "passive"))
      (node (ref "Q83") (pin "B") (pinfunction "B_B") (pintype "passive"))
    )
    (net (code "178") (name "Net-(Q79-PadE)") (class "Default")
      (node (ref "Q79") (pin "E") (pinfunction "E_E") (pintype "passive"))
      (node (ref "R117") (pin "1") (pinfunction "1_1") (pintype "passive"))
    )
    (net (code "179") (name "Net-(Q80-PadC)") (class "Default")
      (node (ref "Q80") (pin "C") (pinfunction "C_C") (pintype "passive"))
      (node (ref "Q82") (pin "B") (pinfunction "B_B") (pintype "passive"))
      (node (ref "Q82") (pin "C") (pinfunction "C_C") (pintype "passive"))
      (node (ref "Q84") (pin "B") (pinfunction "B_B") (pintype "passive"))
    )
    (net (code "180") (name "Net-(Q80-PadE)") (class "Default")
      (node (ref "Q80") (pin "E") (pinfunction "E_E") (pintype "passive"))
      (node (ref "R118") (pin "2") (pinfunction "2_2") (pintype "passive"))
    )
    (net (code "181") (name "Net-(Q83-PadE)") (class "Default")
      (node (ref "Q83") (pin "E") (pinfunction "E_E") (pintype "passive"))
      (node (ref "R119") (pin "2") (pinfunction "2_2") (pintype "passive"))
    )
    (net (code "182") (name "Net-(Q84-PadE)") (class "Default")
      (node (ref "Q84") (pin "E") (pinfunction "E_E") (pintype "passive"))
      (node (ref "R122") (pin "1") (pinfunction "1_1") (pintype "passive"))
    )
    (net (code "183") (name "Net-(Q85-PadB)") (class "Default")
      (node (ref "Q85") (pin "B") (pinfunction "B_B") (pintype "passive"))
      (node (ref "R123") (pin "2") (pinfunction "2_2") (pintype "passive"))
    )
    (net (code "184") (name "Net-(Q85-PadE)") (class "Default")
      (node (ref "Q85") (pin "E") (pinfunction "E_E") (pintype "passive"))
      (node (ref "R120") (pin "2") (pinfunction "2_2") (pintype "passive"))
    )
    (net (code "185") (name "Net-(Q86-PadB)") (class "Default")
      (node (ref "Q86") (pin "B") (pinfunction "B_B") (pintype "passive"))
      (node (ref "R124") (pin "2") (pinfunction "2_2") (pintype "passive"))
    )
    (net (code "186") (name "Net-(Q86-PadE)") (class "Default")
      (node (ref "Q86") (pin "E") (pinfunction "E_E") (pintype "passive"))
      (node (ref "R121") (pin "1") (pinfunction "1_1") (pintype "passive"))
    )
    (net (code "187") (name "Net-(Q87-PadE)") (class "Default")
      (node (ref "Q87") (pin "E") (pinfunction "E_E") (pintype "passive"))
      (node (ref "Q89") (pin "B") (pinfunction "B_B") (pintype "passive"))
    )
    (net (code "188") (name "Net-(Q88-PadE)") (class "Default")
      (node (ref "Q88") (pin "E") (pinfunction "E_E") (pintype "passive"))
      (node (ref "Q90") (pin "B") (pinfunction "B_B") (pintype "passive"))
    )
    (net (code "189") (name "Net-(Q91-PadS)") (class "Default")
      (node (ref "Q91") (pin "S") (pinfunction "S_S") (pintype "passive"))
      (node (ref "R125") (pin "2") (pinfunction "2_2") (pintype "passive"))
    )
    (net (code "190") (name "Net-(Q92-PadS)") (class "Default")
      (node (ref "Q92") (pin "S") (pinfunction "S_S") (pintype "passive"))
      (node (ref "R126") (pin "2") (pinfunction "2_2") (pintype "passive"))
    )
    (net (code "191") (name "Net-(Q97-G)") (class "Default")
      (node (ref "Q97") (pin "4") (pinfunction "G_4") (pintype "passive"))
      (node (ref "U$2") (pin "2") (pinfunction "2_TG2_2") (pintype "bidirectional"))
    )
    (net (code "192") (name "Net-(Q98-G)") (class "Default")
      (node (ref "Q98") (pin "4") (pinfunction "G_4") (pintype "passive"))
      (node (ref "U$2") (pin "11") (pinfunction "7_TG1_11") (pintype "bidirectional"))
    )
    (net (code "193") (name "Net-(Q99-G)") (class "Default")
      (node (ref "Q99") (pin "4") (pinfunction "G_4") (pintype "passive"))
      (node (ref "U$2") (pin "5") (pinfunction "3_BG2_5") (pintype "bidirectional"))
    )
    (net (code "194") (name "Net-(Q100-G)") (class "Default")
      (node (ref "Q100") (pin "4") (pinfunction "G_4") (pintype "passive"))
      (node (ref "U$2") (pin "6") (pinfunction "4_BG1_6") (pintype "bidirectional"))
    )
    (net (code "195") (name "Net-(Q105-G)") (class "Default")
      (node (ref "Q105") (pin "4") (pinfunction "G_4") (pintype "passive"))
      (node (ref "U$4") (pin "2") (pinfunction "2_TG2_2") (pintype "bidirectional"))
    )
    (net (code "196") (name "Net-(Q106-G)") (class "Default")
      (node (ref "Q106") (pin "4") (pinfunction "G_4") (pintype "passive"))
      (node (ref "U$4") (pin "11") (pinfunction "7_TG1_11") (pintype "bidirectional"))
    )
    (net (code "197") (name "Net-(Q107-G)") (class "Default")
      (node (ref "Q107") (pin "4") (pinfunction "G_4") (pintype "passive"))
      (node (ref "U$4") (pin "5") (pinfunction "3_BG2_5") (pintype "bidirectional"))
    )
    (net (code "198") (name "Net-(Q108-G)") (class "Default")
      (node (ref "Q108") (pin "4") (pinfunction "G_4") (pintype "passive"))
      (node (ref "U$4") (pin "6") (pinfunction "4_BG1_6") (pintype "bidirectional"))
    )
    (net (code "199") (name "Net-(R1-S)") (class "Default")
      (node (ref "R1") (pin "2") (pinfunction "S_2") (pintype "passive"))
      (node (ref "R2") (pin "2") (pinfunction "2_2") (pintype "passive"))
    )
    (net (code "200") (name "Net-(R2-Pad1)") (class "Default")
      (node (ref "R2") (pin "1") (pinfunction "1_1") (pintype "passive"))
      (node (ref "R3") (pin "1") (pinfunction "1_1") (pintype "passive"))
      (node (ref "R4") (pin "2") (pinfunction "2_2") (pintype "passive"))
    )
    (net (code "201") (name "Net-(R59-Pad1)") (class "Default")
      (node (ref "R59") (pin "1") (pinfunction "1_1") (pintype "passive"))
      (node (ref "R60") (pin "2") (pinfunction "2_2") (pintype "passive"))
      (node (ref "R63") (pin "2") (pinfunction "2_2") (pintype "passive"))
      (node (ref "R66") (pin "1") (pinfunction "1_1") (pintype "passive"))
    )
    (net (code "202") (name "Net-(R74-A)") (class "Default")
      (node (ref "C18") (pin "2") (pinfunction "2_2") (pintype "passive"))
      (node (ref "C20") (pin "1") (pinfunction "1_1") (pintype "passive"))
      (node (ref "Q40") (pin "C") (pinfunction "C_C") (pintype "passive"))
      (node (ref "Q44") (pin "C") (pinfunction "C_C") (pintype "passive"))
      (node (ref "Q45") (pin "E") (pinfunction "E_E") (pintype "passive"))
      (node (ref "Q47") (pin "B") (pinfunction "B_B") (pintype "passive"))
      (node (ref "R74") (pin "1") (pinfunction "A_1") (pintype "passive"))
      (node (ref "R74") (pin "2") (pinfunction "S_2") (pintype "passive"))
      (node (ref "R76") (pin "2") (pinfunction "2_2") (pintype "passive"))
    )
    (net (code "203") (name "Net-(R74-E)") (class "Default")
      (node (ref "Q45") (pin "B") (pinfunction "B_B") (pintype "passive"))
      (node (ref "R73") (pin "1") (pinfunction "1_1") (pintype "passive"))
      (node (ref "R74") (pin "3") (pinfunction "E_3") (pintype "passive"))
    )
    (net (code "204") (name "Net-(R91-Pad1)") (class "Default")
      (node (ref "R91") (pin "1") (pinfunction "1_1") (pintype "passive"))
      (node (ref "R92") (pin "2") (pinfunction "2_2") (pintype "passive"))
      (node (ref "R95") (pin "2") (pinfunction "2_2") (pintype "passive"))
      (node (ref "R98") (pin "1") (pinfunction "1_1") (pintype "passive"))
    )
    (net (code "205") (name "Net-(R106-A)") (class "Default")
      (node (ref "C28") (pin "2") (pinfunction "2_2") (pintype "passive"))
      (node (ref "C30") (pin "1") (pinfunction "1_1") (pintype "passive"))
      (node (ref "Q67") (pin "C") (pinfunction "C_C") (pintype "passive"))
      (node (ref "Q71") (pin "C") (pinfunction "C_C") (pintype "passive"))
      (node (ref "Q72") (pin "E") (pinfunction "E_E") (pintype "passive"))
      (node (ref "Q74") (pin "B") (pinfunction "B_B") (pintype "passive"))
      (node (ref "R106") (pin "1") (pinfunction "A_1") (pintype "passive"))
      (node (ref "R106") (pin "2") (pinfunction "S_2") (pintype "passive"))
      (node (ref "R108") (pin "2") (pinfunction "2_2") (pintype "passive"))
    )
    (net (code "206") (name "Net-(R106-E)") (class "Default")
      (node (ref "Q72") (pin "B") (pinfunction "B_B") (pintype "passive"))
      (node (ref "R105") (pin "1") (pinfunction "1_1") (pintype "passive"))
      (node (ref "R106") (pin "3") (pinfunction "E_3") (pintype "passive"))
    )
    (net (code "207") (name "Net-(U$1-FILTER)") (class "Default")
      (node (ref "C63") (pin "1") (pinfunction "1_1") (pintype "passive"))
      (node (ref "U$1") (pin "6") (pinfunction "FILTER_6") (pintype "bidirectional"))
    )
    (net (code "208") (name "Net-(U$3-FILTER)") (class "Default")
      (node (ref "C62") (pin "1") (pinfunction "1_1") (pintype "passive"))
      (node (ref "U$3") (pin "6") (pinfunction "FILTER_6") (pintype "bidirectional"))
    )
    (net (code "209") (name "OUT+") (class "Default")
      (node (ref "C1") (pin "1") (pinfunction "1_1") (pintype "passive"))
      (node (ref "PAD1") (pin "P$1") (pinfunction "P$1_P$1") (pintype "bidirectional"))
      (node (ref "R66") (pin "2") (pinfunction "2_2") (pintype "passive"))
      (node (ref "R80") (pin "1") (pinfunction "1_1") (pintype "passive"))
      (node (ref "R81") (pin "2") (pinfunction "2_2") (pintype "passive"))
      (node (ref "R82") (pin "1") (pinfunction "1_1") (pintype "passive"))
    )
    (net (code "210") (name "OUT-") (class "Default")
      (node (ref "PAD2") (pin "P$1") (pinfunction "P$1_P$1") (pintype "bidirectional"))
      (node (ref "R112") (pin "1") (pinfunction "1_1") (pintype "passive"))
      (node (ref "R113") (pin "2") (pinfunction "2_2") (pintype "passive"))
      (node (ref "R114") (pin "1") (pinfunction "1_1") (pintype "passive"))
      (node (ref "R133") (pin "2") (pinfunction "2_2") (pintype "passive"))
      (node (ref "R98") (pin "2") (pinfunction "2_2") (pintype "passive"))
    )
    (net (code "211") (name "UOUT+") (class "Default")
      (node (ref "Q10") (pin "B") (pinfunction "B_B") (pintype "passive"))
      (node (ref "Q5") (pin "6") (pinfunction "C_6") (pintype "passive"))
      (node (ref "Q6") (pin "6") (pinfunction "C_6") (pintype "passive"))
      (node (ref "Q9") (pin "B") (pinfunction "B_B") (pintype "passive"))
      (node (ref "R11") (pin "2") (pinfunction "2_2") (pintype "passive"))
      (node (ref "R21") (pin "2") (pinfunction "2_2") (pintype "passive"))
    )
    (net (code "212") (name "UOUT-") (class "Default")
      (node (ref "Q17") (pin "B") (pinfunction "B_B") (pintype "passive"))
      (node (ref "Q18") (pin "B") (pinfunction "B_B") (pintype "passive"))
      (node (ref "Q5") (pin "4") (pinfunction "C_4") (pintype "passive"))
      (node (ref "Q6") (pin "4") (pinfunction "C_4") (pintype "passive"))
      (node (ref "R20") (pin "2") (pinfunction "2_2") (pintype "passive"))
      (node (ref "R36") (pin "2") (pinfunction "2_2") (pintype "passive"))
    )
    (net (code "213") (name "UV+") (class "Default")
      (node (ref "C57") (pin "1") (pinfunction "1_1") (pintype "passive"))
      (node (ref "Q97") (pin "5") (pinfunction "D_5") (pintype "passive"))
      (node (ref "Q97") (pin "6") (pinfunction "D_6") (pintype "passive"))
      (node (ref "Q97") (pin "7") (pinfunction "D_7") (pintype "passive"))
      (node (ref "Q97") (pin "8") (pinfunction "D_8") (pintype "passive"))
      (node (ref "Q97") (pin "TH") (pinfunction "D_TH") (pintype "passive"))
      (node (ref "Q98") (pin "5") (pinfunction "D_5") (pintype "passive"))
      (node (ref "Q98") (pin "6") (pinfunction "D_6") (pintype "passive"))
      (node (ref "Q98") (pin "7") (pinfunction "D_7") (pintype "passive"))
      (node (ref "Q98") (pin "8") (pinfunction "D_8") (pintype "passive"))
      (node (ref "Q98") (pin "TH") (pinfunction "D_TH") (pintype "passive"))
      (node (ref "U$1") (pin "1") (pinfunction "I+_1") (pintype "bidirectional"))
      (node (ref "U$1") (pin "2") (pinfunction "I+_2") (pintype "bidirectional"))
      (node (ref "U$2") (pin "9") (pinfunction "6_OUTP_9") (pintype "bidirectional"))
    )
    (net (code "214") (name "UV+IN") (class "Default")
      (node (ref "C37") (pin "+") (pinfunction "+_+") (pintype "passive"))
      (node (ref "C42") (pin "2") (pinfunction "2_2") (pintype "passive"))
      (node (ref "C58") (pin "2") (pinfunction "2_2") (pintype "passive"))
      (node (ref "D15") (pin "C") (pinfunction "C_C") (pintype "passive"))
      (node (ref "LED15") (pin "A") (pinfunction "A_A") (pintype "passive"))
      (node (ref "Q87") (pin "C") (pinfunction "C_C") (pintype "passive"))
      (node (ref "Q89") (pin "C") (pinfunction "C_C") (pintype "passive"))
      (node (ref "R115") (pin "1") (pinfunction "1_1") (pintype "passive"))
      (node (ref "R119") (pin "1") (pinfunction "1_1") (pintype "passive"))
      (node (ref "U$1") (pin "3") (pinfunction "I-_3") (pintype "bidirectional"))
      (node (ref "U$1") (pin "4") (pinfunction "I-_4") (pintype "bidirectional"))
    )
    (net (code "215") (name "UV-") (class "Default")
      (node (ref "C59") (pin "2") (pinfunction "2_2") (pintype "passive"))
      (node (ref "Q107") (pin "1") (pinfunction "S_1") (pintype "passive"))
      (node (ref "Q107") (pin "2") (pinfunction "S_2") (pintype "passive"))
      (node (ref "Q107") (pin "3") (pinfunction "S_3") (pintype "passive"))
      (node (ref "Q108") (pin "1") (pinfunction "S_1") (pintype "passive"))
      (node (ref "Q108") (pin "2") (pinfunction "S_2") (pintype "passive"))
      (node (ref "Q108") (pin "3") (pinfunction "S_3") (pintype "passive"))
      (node (ref "U$3") (pin "3") (pinfunction "I-_3") (pintype "bidirectional"))
      (node (ref "U$3") (pin "4") (pinfunction "I-_4") (pintype "bidirectional"))
      (node (ref "U$4") (pin "7") (pinfunction "5_OUTN_7") (pintype "bidirectional"))
      (node (ref "U$4") (pin "EXP") (pinfunction "5_OUTN_EXP") (pintype "bidirectional"))
    )
    (net (code "216") (name "UV-IN") (class "Default")
      (node (ref "C38") (pin "-") (pinfunction "-_-") (pintype "passive"))
      (node (ref "C39") (pin "1") (pinfunction "1_1") (pintype "passive"))
      (node (ref "C60") (pin "1") (pinfunction "1_1") (pintype "passive"))
      (node (ref "D16") (pin "A") (pinfunction "A_A") (pintype "passive"))
      (node (ref "LED16") (pin "C") (pinfunction "C_C") (pintype "passive"))
      (node (ref "Q88") (pin "C") (pinfunction "C_C") (pintype "passive"))
      (node (ref "Q90") (pin "C") (pinfunction "C_C") (pintype "passive"))
      (node (ref "R116") (pin "2") (pinfunction "2_2") (pintype "passive"))
      (node (ref "R122") (pin "2") (pinfunction "2_2") (pintype "passive"))
      (node (ref "U$3") (pin "1") (pinfunction "I+_1") (pintype "bidirectional"))
      (node (ref "U$3") (pin "2") (pinfunction "I+_2") (pintype "bidirectional"))
    )
    (net (code "217") (name "V+") (class "Default")
      (node (ref "C11") (pin "1") (pinfunction "1_1") (pintype "passive"))
      (node (ref "C14") (pin "2") (pinfunction "2_2") (pintype "passive"))
      (node (ref "C23") (pin "1") (pinfunction "1_1") (pintype "passive"))
      (node (ref "C25") (pin "+") (pinfunction "+_+") (pintype "passive"))
      (node (ref "C3") (pin "2") (pinfunction "2_2") (pintype "passive"))
      (node (ref "C33") (pin "1") (pinfunction "1_1") (pintype "passive"))
      (node (ref "C35") (pin "+") (pinfunction "+_+") (pintype "passive"))
      (node (ref "C45") (pin "2") (pinfunction "2_2") (pintype "passive"))
      (node (ref "C5") (pin "+") (pinfunction "+_+") (pintype "passive"))
      (node (ref "C53") (pin "1") (pinfunction "1_1") (pintype "passive"))
      (node (ref "C55") (pin "2") (pinfunction "2_2") (pintype "passive"))
      (node (ref "C7") (pin "+") (pinfunction "+_+") (pintype "passive"))
      (node (ref "C9") (pin "1") (pinfunction "1_1") (pintype "passive"))
      (node (ref "D1") (pin "A") (pinfunction "A_A") (pintype "passive"))
      (node (ref "D15") (pin "A") (pinfunction "A_A") (pintype "passive"))
      (node (ref "D7") (pin "A") (pinfunction "A_A") (pintype "passive"))
      (node (ref "IC1") (pin "7") (pinfunction "V+_7") (pintype "power_in"))
      (node (ref "IC2") (pin "7") (pinfunction "V+_7") (pintype "power_in"))
      (node (ref "IC3") (pin "7") (pinfunction "V+_7") (pintype "power_in"))
      (node (ref "IC4") (pin "7") (pinfunction "V+_7") (pintype "power_in"))
      (node (ref "IC6") (pin "7") (pinfunction "V+_7") (pintype "power_in"))
      (node (ref "LED1") (pin "A") (pinfunction "A_A") (pintype "passive"))
      (node (ref "LED3") (pin "A") (pinfunction "A_A") (pintype "passive"))
      (node (ref "LED5") (pin "A") (pinfunction "A_A") (pintype "passive"))
      (node (ref "LED7") (pin "A") (pinfunction "A_A") (pintype "passive"))
      (node (ref "Q13") (pin "C") (pinfunction "C_C") (pintype "passive"))
      (node (ref "Q15") (pin "C") (pinfunction "C_C") (pintype "passive"))
      (node (ref "Q17") (pin "C") (pinfunction "C_C") (pintype "passive"))
      (node (ref "Q21") (pin "C") (pinfunction "C_C") (pintype "passive"))
      (node (ref "Q23") (pin "C") (pinfunction "C_C") (pintype "passive"))
      (node (ref "Q46") (pin "C") (pinfunction "C_C") (pintype "passive"))
      (node (ref "Q48") (pin "C") (pinfunction "C_C") (pintype "passive"))
      (node (ref "Q50") (pin "C") (pinfunction "C_C") (pintype "passive"))
      (node (ref "Q73") (pin "C") (pinfunction "C_C") (pintype "passive"))
      (node (ref "Q75") (pin "C") (pinfunction "C_C") (pintype "passive"))
      (node (ref "Q77") (pin "C") (pinfunction "C_C") (pintype "passive"))
      (node (ref "Q89") (pin "E") (pinfunction "E_E") (pintype "passive"))
      (node (ref "Q9") (pin "C") (pinfunction "C_C") (pintype "passive"))
      (node (ref "Q91") (pin "D") (pinfunction "D_D") (pintype "passive"))
      (node (ref "R1") (pin "3") (pinfunction "E_3") (pintype "passive"))
      (node (ref "R103") (pin "2") (pinfunction "2_2") (pintype "passive"))
      (node (ref "R12") (pin "2") (pinfunction "2_2") (pintype "passive"))
      (node (ref "R127") (pin "2") (pinfunction "2_2") (pintype "passive"))
      (node (ref "R131") (pin "2") (pinfunction "2_2") (pintype "passive"))
      (node (ref "R18") (pin "2") (pinfunction "2_2") (pintype "passive"))
      (node (ref "R23") (pin "2") (pinfunction "2_2") (pintype "passive"))
      (node (ref "R38") (pin "2") (pinfunction "2_2") (pintype "passive"))
      (node (ref "R5") (pin "2") (pinfunction "2_2") (pintype "passive"))
      (node (ref "R54") (pin "2") (pinfunction "2_2") (pintype "passive"))
      (node (ref "R58") (pin "2") (pinfunction "2_2") (pintype "passive"))
      (node (ref "R62") (pin "2") (pinfunction "2_2") (pintype "passive"))
      (node (ref "R67") (pin "2") (pinfunction "2_2") (pintype "passive"))
      (node (ref "R71") (pin "2") (pinfunction "2_2") (pintype "passive"))
      (node (ref "R86") (pin "2") (pinfunction "2_2") (pintype "passive"))
      (node (ref "R90") (pin "2") (pinfunction "2_2") (pintype "passive"))
      (node (ref "R94") (pin "2") (pinfunction "2_2") (pintype "passive"))
      (node (ref "R99") (pin "2") (pinfunction "2_2") (pintype "passive"))
    )
    (net (code "218") (name "V-") (class "Default")
      (node (ref "C10") (pin "2") (pinfunction "2_2") (pintype "passive"))
      (node (ref "C12") (pin "2") (pinfunction "2_2") (pintype "passive"))
      (node (ref "C15") (pin "1") (pinfunction "1_1") (pintype "passive"))
      (node (ref "C24") (pin "2") (pinfunction "2_2") (pintype "passive"))
      (node (ref "C26") (pin "-") (pinfunction "-_-") (pintype "passive"))
      (node (ref "C34") (pin "2") (pinfunction "2_2") (pintype "passive"))
      (node (ref "C36") (pin "-") (pinfunction "-_-") (pintype "passive"))
      (node (ref "C4") (pin "1") (pinfunction "1_1") (pintype "passive"))
      (node (ref "C46") (pin "1") (pinfunction "1_1") (pintype "passive"))
      (node (ref "C54") (pin "2") (pinfunction "2_2") (pintype "passive"))
      (node (ref "C56") (pin "1") (pinfunction "1_1") (pintype "passive"))
      (node (ref "C6") (pin "-") (pinfunction "-_-") (pintype "passive"))
      (node (ref "C8") (pin "-") (pinfunction "-_-") (pintype "passive"))
      (node (ref "D10") (pin "C") (pinfunction "C_C") (pintype "passive"))
      (node (ref "D16") (pin "C") (pinfunction "C_C") (pintype "passive"))
      (node (ref "D4") (pin "C") (pinfunction "C_C") (pintype "passive"))
      (node (ref "IC1") (pin "4") (pinfunction "V-_4") (pintype "power_in"))
      (node (ref "IC2") (pin "4") (pinfunction "V-_4") (pintype "power_in"))
      (node (ref "IC3") (pin "4") (pinfunction "V-_4") (pintype "power_in"))
      (node (ref "IC4") (pin "4") (pinfunction "V-_4") (pintype "power_in"))
      (node (ref "IC5") (pin "4") (pinfunction "V-_4") (pintype "power_in"))
      (node (ref "LED2") (pin "C") (pinfunction "C_C") (pintype "passive"))
      (node (ref "LED4") (pin "C") (pinfunction "C_C") (pintype "passive"))
      (node (ref "LED6") (pin "C") (pinfunction "C_C") (pintype "passive"))
      (node (ref "LED8") (pin "C") (pinfunction "C_C") (pintype "passive"))
      (node (ref "Q10") (pin "C") (pinfunction "C_C") (pintype "passive"))
      (node (ref "Q14") (pin "C") (pinfunction "C_C") (pintype "passive"))
      (node (ref "Q16") (pin "C") (pinfunction "C_C") (pintype "passive"))
      (node (ref "Q18") (pin "C") (pinfunction "C_C") (pintype "passive"))
      (node (ref "Q22") (pin "C") (pinfunction "C_C") (pintype "passive"))
      (node (ref "Q24") (pin "C") (pinfunction "C_C") (pintype "passive"))
      (node (ref "Q47") (pin "C") (pinfunction "C_C") (pintype "passive"))
      (node (ref "Q49") (pin "C") (pinfunction "C_C") (pintype "passive"))
      (node (ref "Q51") (pin "C") (pinfunction "C_C") (pintype "passive"))
      (node (ref "Q74") (pin "C") (pinfunction "C_C") (pintype "passive"))
      (node (ref "Q76") (pin "C") (pinfunction "C_C") (pintype "passive"))
      (node (ref "Q78") (pin "C") (pinfunction "C_C") (pintype "passive"))
      (node (ref "Q90") (pin "E") (pinfunction "E_E") (pintype "passive"))
      (node (ref "Q92") (pin "G") (pinfunction "G_G") (pintype "passive"))
      (node (ref "R1") (pin "1") (pinfunction "A_1") (pintype "passive"))
      (node (ref "R102") (pin "1") (pinfunction "1_1") (pintype "passive"))
      (node (ref "R104") (pin "1") (pinfunction "1_1") (pintype "passive"))
      (node (ref "R126") (pin "1") (pinfunction "1_1") (pintype "passive"))
      (node (ref "R13") (pin "1") (pinfunction "1_1") (pintype "passive"))
      (node (ref "R130") (pin "1") (pinfunction "1_1") (pintype "passive"))
      (node (ref "R132") (pin "1") (pinfunction "1_1") (pintype "passive"))
      (node (ref "R19") (pin "1") (pinfunction "1_1") (pintype "passive"))
      (node (ref "R26") (pin "1") (pinfunction "1_1") (pintype "passive"))
      (node (ref "R41") (pin "1") (pinfunction "1_1") (pintype "passive"))
      (node (ref "R57") (pin "1") (pinfunction "1_1") (pintype "passive"))
      (node (ref "R61") (pin "1") (pinfunction "1_1") (pintype "passive"))
      (node (ref "R64") (pin "1") (pinfunction "1_1") (pintype "passive"))
      (node (ref "R7") (pin "1") (pinfunction "1_1") (pintype "passive"))
      (node (ref "R70") (pin "1") (pinfunction "1_1") (pintype "passive"))
      (node (ref "R72") (pin "1") (pinfunction "1_1") (pintype "passive"))
      (node (ref "R89") (pin "1") (pinfunction "1_1") (pintype "passive"))
      (node (ref "R93") (pin "1") (pinfunction "1_1") (pintype "passive"))
      (node (ref "R96") (pin "1") (pinfunction "1_1") (pintype "passive"))
    )
    (net (code "219") (name "VS+") (class "Default")
      (node (ref "J1") (pin "2") (pinfunction "S_2") (pintype "passive"))
      (node (ref "U$1") (pin "7") (pinfunction "VOUT_7") (pintype "bidirectional"))
    )
    (net (code "220") (name "VS-") (class "Default")
      (node (ref "J2") (pin "2") (pinfunction "S_2") (pintype "passive"))
      (node (ref "U$3") (pin "7") (pinfunction "VOUT_7") (pintype "bidirectional"))
    )
    (net (code "221") (name "unconnected-(IC1-CMP1-Pad1)") (class "Default")
      (node (ref "IC1") (pin "1") (pinfunction "CMP1_1") (pintype "passive"))
    )
    (net (code "222") (name "unconnected-(IC1-CMP2-Pad8)") (class "Default")
      (node (ref "IC1") (pin "8") (pinfunction "CMP2_8") (pintype "passive"))
    )
    (net (code "223") (name "unconnected-(IC2-CMP1-Pad1)") (class "Default")
      (node (ref "IC2") (pin "1") (pinfunction "CMP1_1") (pintype "passive"))
    )
    (net (code "224") (name "unconnected-(IC2-CMP2-Pad8)") (class "Default")
      (node (ref "IC2") (pin "8") (pinfunction "CMP2_8") (pintype "passive"))
    )
    (net (code "225") (name "unconnected-(IC3-CMP1-Pad1)") (class "Default")
      (node (ref "IC3") (pin "1") (pinfunction "CMP1_1") (pintype "passive"))
    )
    (net (code "226") (name "unconnected-(IC3-CMP2-Pad8)") (class "Default")
      (node (ref "IC3") (pin "8") (pinfunction "CMP2_8") (pintype "passive"))
    )
    (net (code "227") (name "unconnected-(IC4-CMP1-Pad1)") (class "Default")
      (node (ref "IC4") (pin "1") (pinfunction "CMP1_1") (pintype "passive"))
    )
    (net (code "228") (name "unconnected-(IC4-CMP2-Pad8)") (class "Default")
      (node (ref "IC4") (pin "8") (pinfunction "CMP2_8") (pintype "passive"))
    )
    (net (code "229") (name "unconnected-(IC5-CMP1-Pad1)") (class "Default")
      (node (ref "IC5") (pin "1") (pinfunction "CMP1_1") (pintype "passive"))
    )
    (net (code "230") (name "unconnected-(IC5-CMP2-Pad8)") (class "Default")
      (node (ref "IC5") (pin "8") (pinfunction "CMP2_8") (pintype "passive"))
    )
    (net (code "231") (name "unconnected-(IC6-CMP1-Pad1)") (class "Default")
      (node (ref "IC6") (pin "1") (pinfunction "CMP1_1") (pintype "passive"))
    )
    (net (code "232") (name "unconnected-(IC6-CMP2-Pad8)") (class "Default")
      (node (ref "IC6") (pin "8") (pinfunction "CMP2_8") (pintype "passive"))
    )
  )
)
